# 1203_054.net
KiCad netlist of a schematic drawn in EAGLE
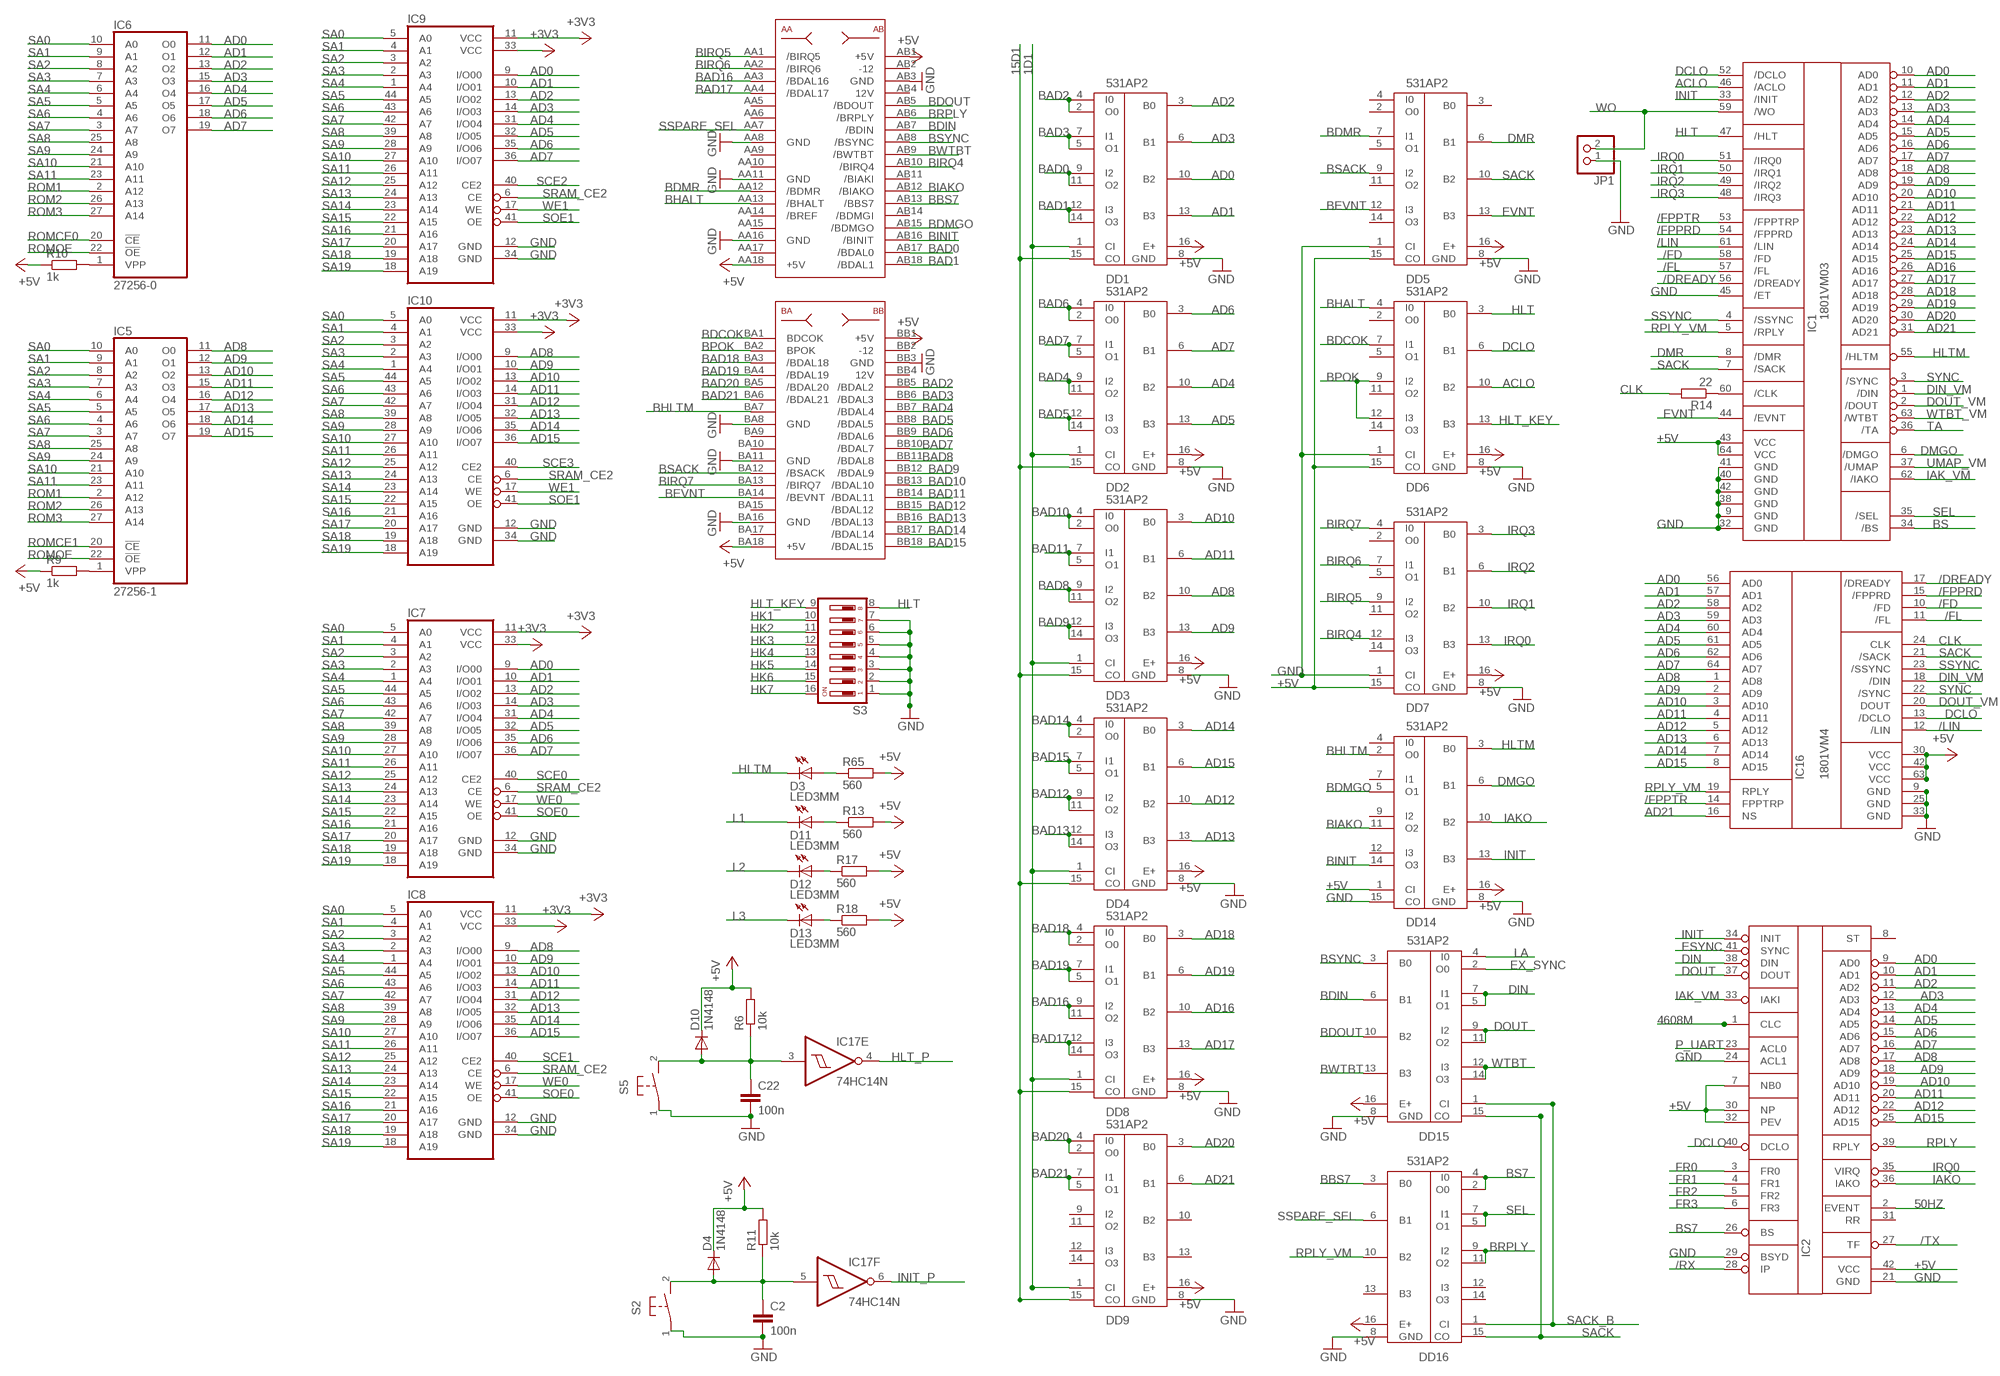
[diagram p0: schematic, sheet 1, part 1 of 2]
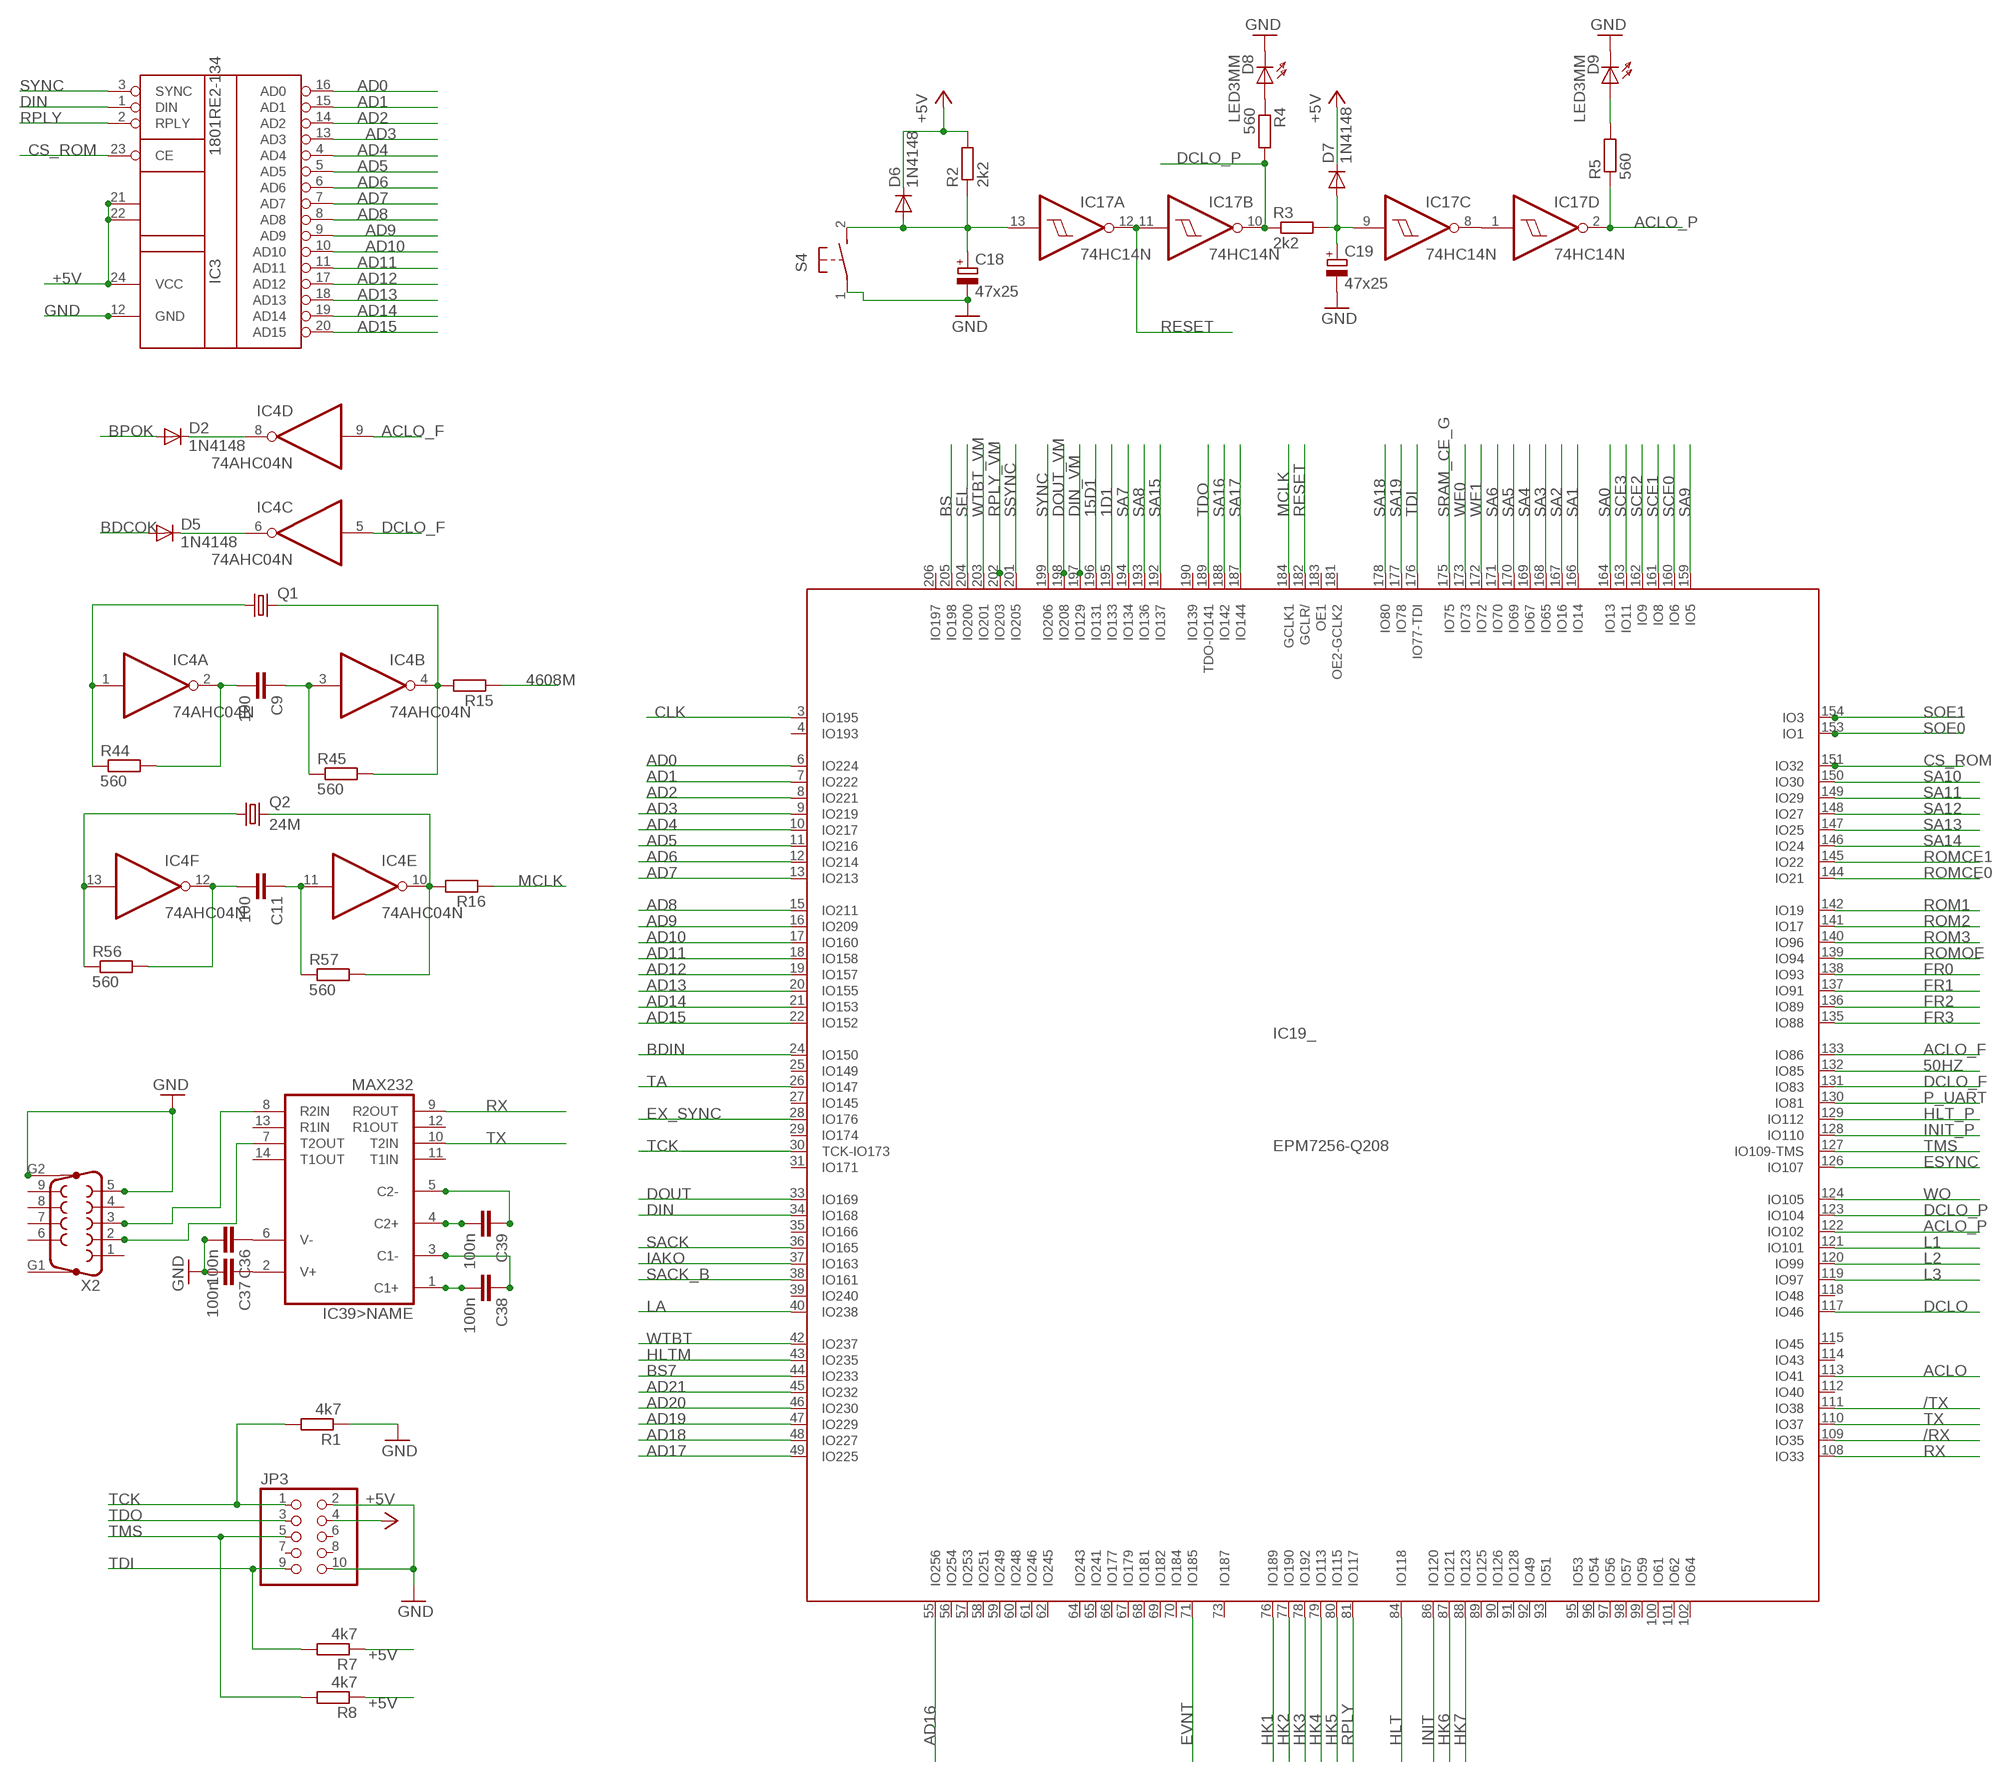
[diagram p1: schematic, sheet 1, part 2 of 2]
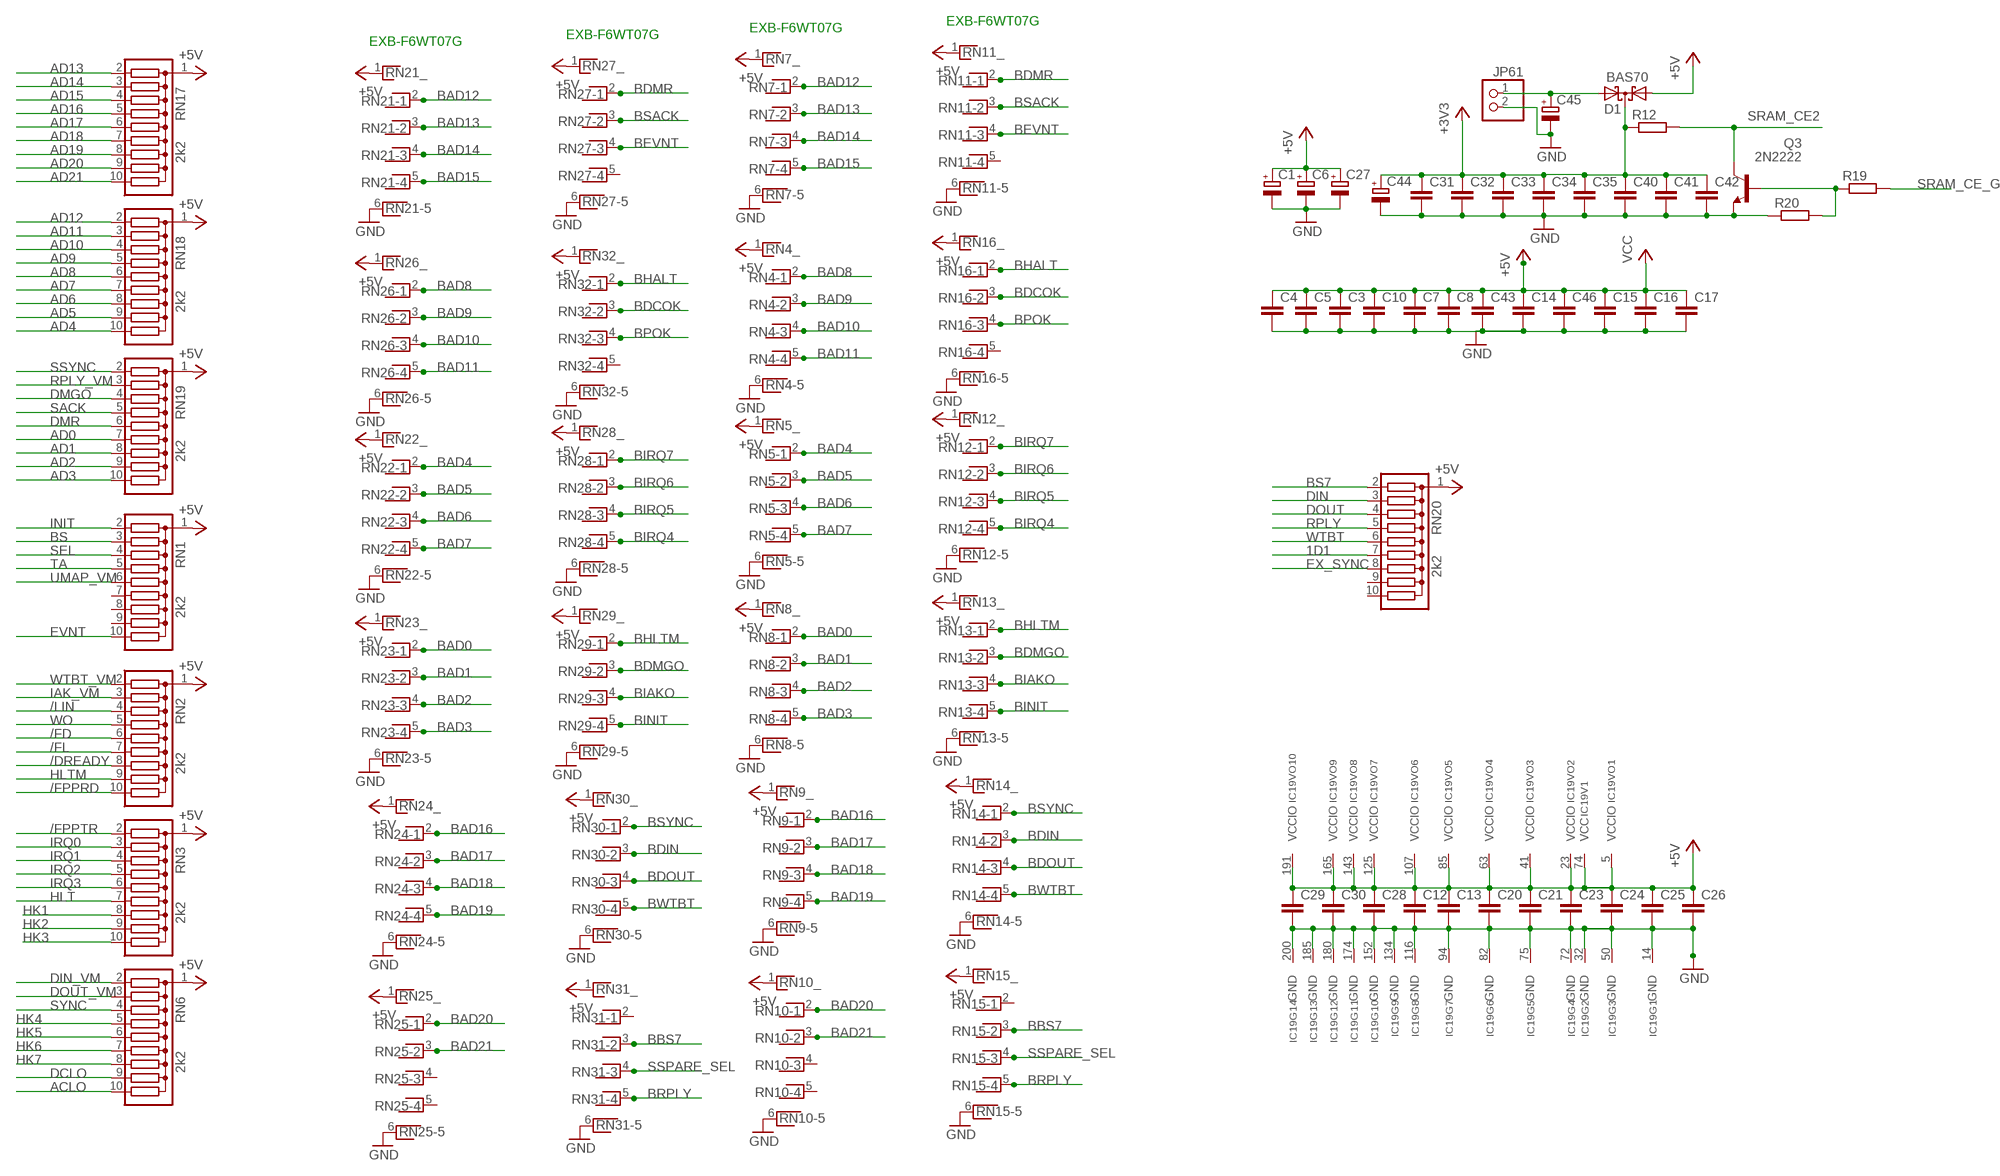
[diagram p2: schematic, sheet 2]

(export (version "E")
  (design (tool "Eeschema 10.0.6"))
  (components
    (comp (ref "C1")
      (value "CPOL-EUCT6032")
      (footprint "eagle-import:CT6032")
      (libsource (lib "eagle-import") (part "CPOL-EUCT6032"))
    )
    (comp (ref "C3")
      (value "C-EU050-024X044")
      (footprint "eagle-import:C050-024X044")
      (libsource (lib "eagle-import") (part "C-EU050-024X044"))
    )
    (comp (ref "C4")
      (value "C-EU050-024X044")
      (footprint "eagle-import:C050-024X044")
      (libsource (lib "eagle-import") (part "C-EU050-024X044"))
    )
    (comp (ref "C5")
      (value "C-EU050-024X044")
      (footprint "eagle-import:C050-024X044")
      (libsource (lib "eagle-import") (part "C-EU050-024X044"))
    )
    (comp (ref "C6")
      (value "CPOL-EUCT6032")
      (footprint "eagle-import:CT6032")
      (libsource (lib "eagle-import") (part "CPOL-EUCT6032"))
    )
    (comp (ref "C7")
      (value "C-EU050-024X044")
      (footprint "eagle-import:C050-024X044")
      (libsource (lib "eagle-import") (part "C-EU050-024X044"))
    )
    (comp (ref "C8")
      (value "C-EU050-024X044")
      (footprint "eagle-import:C050-024X044")
      (libsource (lib "eagle-import") (part "C-EU050-024X044"))
    )
    (comp (ref "C10")
      (value "C-EU050-024X044")
      (footprint "eagle-import:C050-024X044")
      (libsource (lib "eagle-import") (part "C-EU050-024X044"))
    )
    (comp (ref "C12")
      (value "C-EUC0805")
      (footprint "eagle-import:C0805")
      (libsource (lib "eagle-import") (part "C-EUC0805"))
    )
    (comp (ref "C13")
      (value "C-EUC0805")
      (footprint "eagle-import:C0805")
      (libsource (lib "eagle-import") (part "C-EUC0805"))
    )
    (comp (ref "C14")
      (value "C-EU050-024X044")
      (footprint "eagle-import:C050-024X044")
      (libsource (lib "eagle-import") (part "C-EU050-024X044"))
    )
    (comp (ref "C15")
      (value "C-EU050-024X044")
      (footprint "eagle-import:C050-024X044")
      (libsource (lib "eagle-import") (part "C-EU050-024X044"))
    )
    (comp (ref "C16")
      (value "C-EU050-024X044")
      (footprint "eagle-import:C050-024X044")
      (libsource (lib "eagle-import") (part "C-EU050-024X044"))
    )
    (comp (ref "C17")
      (value "C-EU050-024X044")
      (footprint "eagle-import:C050-024X044")
      (libsource (lib "eagle-import") (part "C-EU050-024X044"))
    )
    (comp (ref "C20")
      (value "C-EUC0805")
      (footprint "eagle-import:C0805")
      (libsource (lib "eagle-import") (part "C-EUC0805"))
    )
    (comp (ref "C21")
      (value "C-EUC0805")
      (footprint "eagle-import:C0805")
      (libsource (lib "eagle-import") (part "C-EUC0805"))
    )
    (comp (ref "C23")
      (value "C-EU050-024X044")
      (footprint "eagle-import:C050-024X044")
      (libsource (lib "eagle-import") (part "C-EU050-024X044"))
    )
    (comp (ref "C24")
      (value "C-EU050-024X044")
      (footprint "eagle-import:C050-024X044")
      (libsource (lib "eagle-import") (part "C-EU050-024X044"))
    )
    (comp (ref "C25")
      (value "C-EU050-024X044")
      (footprint "eagle-import:C050-024X044")
      (libsource (lib "eagle-import") (part "C-EU050-024X044"))
    )
    (comp (ref "C26")
      (value "C-EU050-024X044")
      (footprint "eagle-import:C050-024X044")
      (libsource (lib "eagle-import") (part "C-EU050-024X044"))
    )
    (comp (ref "C27")
      (value "CPOL-EUCT6032")
      (footprint "eagle-import:CT6032")
      (libsource (lib "eagle-import") (part "CPOL-EUCT6032"))
    )
    (comp (ref "C28")
      (value "C-EU050-024X044")
      (footprint "eagle-import:C050-024X044")
      (libsource (lib "eagle-import") (part "C-EU050-024X044"))
    )
    (comp (ref "C29")
      (value "C-EU050-024X044")
      (footprint "eagle-import:C050-024X044")
      (libsource (lib "eagle-import") (part "C-EU050-024X044"))
    )
    (comp (ref "C30")
      (value "C-EU050-024X044")
      (footprint "eagle-import:C050-024X044")
      (libsource (lib "eagle-import") (part "C-EU050-024X044"))
    )
    (comp (ref "C31")
      (value "C-EUC0603")
      (footprint "eagle-import:C0603")
      (libsource (lib "eagle-import") (part "C-EUC0603"))
    )
    (comp (ref "C32")
      (value "C-EUC0603")
      (footprint "eagle-import:C0603")
      (libsource (lib "eagle-import") (part "C-EUC0603"))
    )
    (comp (ref "C33")
      (value "C-EUC0603")
      (footprint "eagle-import:C0603")
      (libsource (lib "eagle-import") (part "C-EUC0603"))
    )
    (comp (ref "C34")
      (value "C-EUC0603")
      (footprint "eagle-import:C0603")
      (libsource (lib "eagle-import") (part "C-EUC0603"))
    )
    (comp (ref "C35")
      (value "C-EUC0603")
      (footprint "eagle-import:C0603")
      (libsource (lib "eagle-import") (part "C-EUC0603"))
    )
    (comp (ref "C40")
      (value "C-EUC0603")
      (footprint "eagle-import:C0603")
      (libsource (lib "eagle-import") (part "C-EUC0603"))
    )
    (comp (ref "C41")
      (value "C-EUC0603")
      (footprint "eagle-import:C0603")
      (libsource (lib "eagle-import") (part "C-EUC0603"))
    )
    (comp (ref "C42")
      (value "C-EUC0603")
      (footprint "eagle-import:C0603")
      (libsource (lib "eagle-import") (part "C-EUC0603"))
    )
    (comp (ref "C43")
      (value "C-EU050-024X044")
      (footprint "eagle-import:C050-024X044")
      (libsource (lib "eagle-import") (part "C-EU050-024X044"))
    )
    (comp (ref "C44")
      (value "CPOL-EUCT7343")
      (footprint "eagle-import:CT7343")
      (libsource (lib "eagle-import") (part "CPOL-EUCT7343"))
    )
    (comp (ref "C45")
      (value "CPOL-EUCT7343")
      (footprint "eagle-import:CT7343")
      (libsource (lib "eagle-import") (part "CPOL-EUCT7343"))
    )
    (comp (ref "C46")
      (value "C-EU050-024X044")
      (footprint "eagle-import:C050-024X044")
      (libsource (lib "eagle-import") (part "C-EU050-024X044"))
    )
    (comp (ref "D1")
      (value "BAS70")
      (footprint "eagle-import:SOT23")
      (libsource (lib "eagle-import") (part "BAS70-05"))
    )
    (comp (ref "IC19")
      (value "EPM7256-Q208")
      (footprint "eagle-import:RQFP208")
      (fields (field (name "MPN") "EPM7256AEQC208-10N"))
      (libsource (lib "eagle-import") (part "EPM7256-Q208"))
    )
    (comp (ref "JP61")
      (value "PINHD-1X2")
      (footprint "eagle-import:1X02")
      (libsource (lib "eagle-import") (part "PINHD-1X2"))
    )
    (comp (ref "Q3")
      (value "2N2222")
      (footprint "eagle-import:TO18")
      (libsource (lib "eagle-import") (part "2N2222"))
    )
    (comp (ref "R12")
      (value "R-EU_M0805")
      (footprint "eagle-import:M0805")
      (libsource (lib "eagle-import") (part "R-EU_M0805"))
    )
    (comp (ref "R19")
      (value "R-EU_M0805")
      (footprint "eagle-import:M0805")
      (libsource (lib "eagle-import") (part "R-EU_M0805"))
    )
    (comp (ref "R20")
      (value "R-EU_M0805")
      (footprint "eagle-import:M0805")
      (libsource (lib "eagle-import") (part "R-EU_M0805"))
    )
    (comp (ref "RN1")
      (value "2k2")
      (footprint "eagle-import:SIL10")
      (libsource (lib "eagle-import") (part "G09R"))
    )
    (comp (ref "RN2")
      (value "2k2")
      (footprint "eagle-import:SIL10")
      (libsource (lib "eagle-import") (part "G09R"))
    )
    (comp (ref "RN3")
      (value "2k2")
      (footprint "eagle-import:SIL10")
      (libsource (lib "eagle-import") (part "G09R"))
    )
    (comp (ref "RN4")
      (value "RNX5")
      (footprint "eagle-import:RN-6")
      (libsource (lib "eagle-import") (part "RNX5"))
    )
    (comp (ref "RN5")
      (value "RNX5")
      (footprint "eagle-import:RN-6")
      (libsource (lib "eagle-import") (part "RNX5"))
    )
    (comp (ref "RN6")
      (value "2k2")
      (footprint "eagle-import:SIL10")
      (libsource (lib "eagle-import") (part "G09R"))
    )
    (comp (ref "RN7")
      (value "RNX5")
      (footprint "eagle-import:RN-6")
      (libsource (lib "eagle-import") (part "RNX5"))
    )
    (comp (ref "RN8")
      (value "RNX5")
      (footprint "eagle-import:RN-6")
      (libsource (lib "eagle-import") (part "RNX5"))
    )
    (comp (ref "RN9")
      (value "RNX5")
      (footprint "eagle-import:RN-6")
      (libsource (lib "eagle-import") (part "RNX5"))
    )
    (comp (ref "RN10")
      (value "RNX5")
      (footprint "eagle-import:RN-6")
      (libsource (lib "eagle-import") (part "RNX5"))
    )
    (comp (ref "RN11")
      (value "RNX5")
      (footprint "eagle-import:RN-6")
      (libsource (lib "eagle-import") (part "RNX5"))
    )
    (comp (ref "RN12")
      (value "RNX5")
      (footprint "eagle-import:RN-6")
      (libsource (lib "eagle-import") (part "RNX5"))
    )
    (comp (ref "RN13")
      (value "RNX5")
      (footprint "eagle-import:RN-6")
      (libsource (lib "eagle-import") (part "RNX5"))
    )
    (comp (ref "RN14")
      (value "RNX5")
      (footprint "eagle-import:RN-6")
      (libsource (lib "eagle-import") (part "RNX5"))
    )
    (comp (ref "RN15")
      (value "RNX5")
      (footprint "eagle-import:RN-6")
      (libsource (lib "eagle-import") (part "RNX5"))
    )
    (comp (ref "RN16")
      (value "RNX5")
      (footprint "eagle-import:RN-6")
      (libsource (lib "eagle-import") (part "RNX5"))
    )
    (comp (ref "RN17")
      (value "2k2")
      (footprint "eagle-import:SIL10")
      (libsource (lib "eagle-import") (part "G09R"))
    )
    (comp (ref "RN18")
      (value "2k2")
      (footprint "eagle-import:SIL10")
      (libsource (lib "eagle-import") (part "G09R"))
    )
    (comp (ref "RN19")
      (value "2k2")
      (footprint "eagle-import:SIL10")
      (libsource (lib "eagle-import") (part "G09R"))
    )
    (comp (ref "RN20")
      (value "2k2")
      (footprint "eagle-import:SIL10")
      (libsource (lib "eagle-import") (part "G09R"))
    )
    (comp (ref "RN21")
      (value "RNX5")
      (footprint "eagle-import:RN-6")
      (libsource (lib "eagle-import") (part "RNX5"))
    )
    (comp (ref "RN22")
      (value "RNX5")
      (footprint "eagle-import:RN-6")
      (libsource (lib "eagle-import") (part "RNX5"))
    )
    (comp (ref "RN23")
      (value "RNX5")
      (footprint "eagle-import:RN-6")
      (libsource (lib "eagle-import") (part "RNX5"))
    )
    (comp (ref "RN24")
      (value "RNX5")
      (footprint "eagle-import:RN-6")
      (libsource (lib "eagle-import") (part "RNX5"))
    )
    (comp (ref "RN25")
      (value "RNX5")
      (footprint "eagle-import:RN-6")
      (libsource (lib "eagle-import") (part "RNX5"))
    )
    (comp (ref "RN26")
      (value "RNX5")
      (footprint "eagle-import:RN-6")
      (libsource (lib "eagle-import") (part "RNX5"))
    )
    (comp (ref "RN27")
      (value "RNX5")
      (footprint "eagle-import:RN-6")
      (libsource (lib "eagle-import") (part "RNX5"))
    )
    (comp (ref "RN28")
      (value "RNX5")
      (footprint "eagle-import:RN-6")
      (libsource (lib "eagle-import") (part "RNX5"))
    )
    (comp (ref "RN29")
      (value "RNX5")
      (footprint "eagle-import:RN-6")
      (libsource (lib "eagle-import") (part "RNX5"))
    )
    (comp (ref "RN30")
      (value "RNX5")
      (footprint "eagle-import:RN-6")
      (libsource (lib "eagle-import") (part "RNX5"))
    )
    (comp (ref "RN31")
      (value "RNX5")
      (footprint "eagle-import:RN-6")
      (libsource (lib "eagle-import") (part "RNX5"))
    )
    (comp (ref "RN32")
      (value "RNX5")
      (footprint "eagle-import:RN-6")
      (libsource (lib "eagle-import") (part "RNX5"))
    )
    (comp (ref "C2")
      (value "100n")
      (footprint "eagle-import:C050-024X044")
      (libsource (lib "eagle-import") (part "C-EU050-024X044"))
    )
    (comp (ref "C9")
      (value "100")
      (footprint "eagle-import:C025-024X044")
      (libsource (lib "eagle-import") (part "C-EU025-024X044"))
    )
    (comp (ref "C11")
      (value "100")
      (footprint "eagle-import:C025-024X044")
      (libsource (lib "eagle-import") (part "C-EU025-024X044"))
    )
    (comp (ref "C18")
      (value "47x25")
      (footprint "eagle-import:E2,5-5")
      (libsource (lib "eagle-import") (part "CPOL-EUE2.5-5"))
    )
    (comp (ref "C19")
      (value "47x25")
      (footprint "eagle-import:E2,5-5")
      (libsource (lib "eagle-import") (part "CPOL-EUE2.5-5"))
    )
    (comp (ref "C22")
      (value "100n")
      (footprint "eagle-import:C050-024X044")
      (libsource (lib "eagle-import") (part "C-EU050-024X044"))
    )
    (comp (ref "C36")
      (value "100n")
      (footprint "eagle-import:C025-024X044")
      (libsource (lib "eagle-import") (part "C-EU025-024X044"))
    )
    (comp (ref "C37")
      (value "100n")
      (footprint "eagle-import:C025-024X044")
      (libsource (lib "eagle-import") (part "C-EU025-024X044"))
    )
    (comp (ref "C38")
      (value "100n")
      (footprint "eagle-import:C025-024X044")
      (libsource (lib "eagle-import") (part "C-EU025-024X044"))
    )
    (comp (ref "C39")
      (value "100n")
      (footprint "eagle-import:C025-024X044")
      (libsource (lib "eagle-import") (part "C-EU025-024X044"))
    )
    (comp (ref "D2")
      (value "1N4148")
      (footprint "eagle-import:DO35-10")
      (libsource (lib "eagle-import") (part "1N4148"))
    )
    (comp (ref "D3")
      (value "LED3MM")
      (footprint "eagle-import:LED3MM")
      (libsource (lib "eagle-import") (part "LED3MM"))
    )
    (comp (ref "D4")
      (value "1N4148")
      (footprint "eagle-import:DO35-10")
      (libsource (lib "eagle-import") (part "1N4148"))
    )
    (comp (ref "D5")
      (value "1N4148")
      (footprint "eagle-import:DO35-10")
      (libsource (lib "eagle-import") (part "1N4148"))
    )
    (comp (ref "D6")
      (value "1N4148")
      (footprint "eagle-import:DO35-10")
      (libsource (lib "eagle-import") (part "1N4148"))
    )
    (comp (ref "D7")
      (value "1N4148")
      (footprint "eagle-import:DO35-10")
      (libsource (lib "eagle-import") (part "1N4148"))
    )
    (comp (ref "D8")
      (value "LED3MM")
      (footprint "eagle-import:LED3MM")
      (libsource (lib "eagle-import") (part "LED3MM"))
    )
    (comp (ref "D9")
      (value "LED3MM")
      (footprint "eagle-import:LED3MM")
      (libsource (lib "eagle-import") (part "LED3MM"))
    )
    (comp (ref "D10")
      (value "1N4148")
      (footprint "eagle-import:DO35-10")
      (libsource (lib "eagle-import") (part "1N4148"))
    )
    (comp (ref "D11")
      (value "LED3MM")
      (footprint "eagle-import:LED3MM")
      (libsource (lib "eagle-import") (part "LED3MM"))
    )
    (comp (ref "D12")
      (value "LED3MM")
      (footprint "eagle-import:LED3MM")
      (libsource (lib "eagle-import") (part "LED3MM"))
    )
    (comp (ref "D13")
      (value "LED3MM")
      (footprint "eagle-import:LED3MM")
      (libsource (lib "eagle-import") (part "LED3MM"))
    )
    (comp (ref "DD1")
      (value "531AP2")
      (footprint "eagle-import:DIL16")
      (libsource (lib "eagle-import") (part "531AP2"))
    )
    (comp (ref "DD2")
      (value "531AP2")
      (footprint "eagle-import:DIL16")
      (libsource (lib "eagle-import") (part "531AP2"))
    )
    (comp (ref "DD3")
      (value "531AP2")
      (footprint "eagle-import:DIL16")
      (libsource (lib "eagle-import") (part "531AP2"))
    )
    (comp (ref "DD4")
      (value "531AP2")
      (footprint "eagle-import:DIL16")
      (libsource (lib "eagle-import") (part "531AP2"))
    )
    (comp (ref "DD5")
      (value "531AP2")
      (footprint "eagle-import:DIL16")
      (libsource (lib "eagle-import") (part "531AP2"))
    )
    (comp (ref "DD6")
      (value "531AP2")
      (footprint "eagle-import:DIL16")
      (libsource (lib "eagle-import") (part "531AP2"))
    )
    (comp (ref "DD7")
      (value "531AP2")
      (footprint "eagle-import:DIL16")
      (libsource (lib "eagle-import") (part "531AP2"))
    )
    (comp (ref "DD8")
      (value "531AP2")
      (footprint "eagle-import:DIL16")
      (libsource (lib "eagle-import") (part "531AP2"))
    )
    (comp (ref "DD9")
      (value "531AP2")
      (footprint "eagle-import:DIL16")
      (libsource (lib "eagle-import") (part "531AP2"))
    )
    (comp (ref "DD14")
      (value "531AP2")
      (footprint "eagle-import:DIL16")
      (libsource (lib "eagle-import") (part "531AP2"))
    )
    (comp (ref "DD15")
      (value "531AP2")
      (footprint "eagle-import:DIL16")
      (libsource (lib "eagle-import") (part "531AP2"))
    )
    (comp (ref "DD16")
      (value "531AP2")
      (footprint "eagle-import:DIL16")
      (libsource (lib "eagle-import") (part "531AP2"))
    )
    (comp (ref "IC1")
      (value "1801VM03")
      (footprint "eagle-import:DIL64")
      (libsource (lib "eagle-import") (part "1801M03"))
    )
    (comp (ref "IC2")
      (value "1801VP1-065")
      (footprint "eagle-import:1801")
      (libsource (lib "eagle-import") (part "1801VP1-065"))
    )
    (comp (ref "IC3")
      (value "1801RE2-134")
      (footprint "eagle-import:DIL24")
      (libsource (lib "eagle-import") (part "1801RE2"))
    )
    (comp (ref "IC4")
      (value "74AHC04N")
      (footprint "eagle-import:DIL14")
      (libsource (lib "eagle-import") (part "7405NALS"))
    )
    (comp (ref "IC5")
      (value "27256-1")
      (footprint "eagle-import:DIL28")
      (libsource (lib "eagle-import") (part "27256"))
    )
    (comp (ref "IC6")
      (value "27256-0")
      (footprint "eagle-import:DIL28")
      (libsource (lib "eagle-import") (part "27256"))
    )
    (comp (ref "IC7")
      (value "AS6C800855Z")
      (footprint "eagle-import:TSOP44")
      (libsource (lib "eagle-import") (part "AS6C800855Z"))
    )
    (comp (ref "IC8")
      (value "AS6C800855Z")
      (footprint "eagle-import:TSOP44")
      (libsource (lib "eagle-import") (part "AS6C800855Z"))
    )
    (comp (ref "IC9")
      (value "AS6C800855Z")
      (footprint "eagle-import:TSOP44")
      (libsource (lib "eagle-import") (part "AS6C800855Z"))
    )
    (comp (ref "IC10")
      (value "AS6C800855Z")
      (footprint "eagle-import:TSOP44")
      (libsource (lib "eagle-import") (part "AS6C800855Z"))
    )
    (comp (ref "IC16")
      (value "1801VM4")
      (footprint "eagle-import:1801VM4")
      (libsource (lib "eagle-import") (part "1801VM4"))
    )
    (comp (ref "IC17")
      (value "74HC14N")
      (footprint "eagle-import:DIL14")
      (libsource (lib "eagle-import") (part "7414NAC"))
    )
    (comp (ref "IC39")
      (value "MAX232")
      (footprint "eagle-import:DIL16")
      (libsource (lib "eagle-import") (part "MAX232"))
    )
    (comp (ref "JP1")
      (value "PINHD-1X2")
      (footprint "eagle-import:1X02")
      (libsource (lib "eagle-import") (part "PINHD-1X2"))
    )
    (comp (ref "JP3")
      (value "PINHD-2X5")
      (footprint "eagle-import:2X05")
      (libsource (lib "eagle-import") (part "PINHD-2X5"))
    )
    (comp (ref "Q1")
      (value "HC49U70")
      (footprint "eagle-import:HC49U70")
      (libsource (lib "eagle-import") (part "HC49U70"))
    )
    (comp (ref "Q2")
      (value "24M")
      (footprint "eagle-import:HC49U70")
      (libsource (lib "eagle-import") (part "HC49U70"))
    )
    (comp (ref "R1")
      (value "4k7")
      (footprint "eagle-import:M0805")
      (libsource (lib "eagle-import") (part "R-EU_M0805"))
    )
    (comp (ref "R2")
      (value "2k2")
      (footprint "eagle-import:0207_10")
      (libsource (lib "eagle-import") (part "R-EU_0207/10"))
    )
    (comp (ref "R3")
      (value "2k2")
      (footprint "eagle-import:0207_10")
      (libsource (lib "eagle-import") (part "R-EU_0207/10"))
    )
    (comp (ref "R4")
      (value "560")
      (footprint "eagle-import:M0805")
      (libsource (lib "eagle-import") (part "R-EU_M0805"))
    )
    (comp (ref "R5")
      (value "560")
      (footprint "eagle-import:M0805")
      (libsource (lib "eagle-import") (part "R-EU_M0805"))
    )
    (comp (ref "R6")
      (value "10k")
      (footprint "eagle-import:0207_10")
      (libsource (lib "eagle-import") (part "R-EU_0207/10"))
    )
    (comp (ref "R7")
      (value "4k7")
      (footprint "eagle-import:M0805")
      (libsource (lib "eagle-import") (part "R-EU_M0805"))
    )
    (comp (ref "R8")
      (value "4k7")
      (footprint "eagle-import:M0805")
      (libsource (lib "eagle-import") (part "R-EU_M0805"))
    )
    (comp (ref "R9")
      (value "1k")
      (footprint "eagle-import:M0805")
      (libsource (lib "eagle-import") (part "R-EU_M0805"))
    )
    (comp (ref "R10")
      (value "1k")
      (footprint "eagle-import:M0805")
      (libsource (lib "eagle-import") (part "R-EU_M0805"))
    )
    (comp (ref "R11")
      (value "10k")
      (footprint "eagle-import:0207_10")
      (libsource (lib "eagle-import") (part "R-EU_0207/10"))
    )
    (comp (ref "R13")
      (value "560")
      (footprint "eagle-import:M0805")
      (libsource (lib "eagle-import") (part "R-EU_M0805"))
    )
    (comp (ref "R14")
      (value "22")
      (footprint "eagle-import:0204V")
      (libsource (lib "eagle-import") (part "R-EU_0204/2V"))
    )
    (comp (ref "R15")
      (value "R-EU_0204/2V")
      (footprint "eagle-import:0204V")
      (libsource (lib "eagle-import") (part "R-EU_0204/2V"))
    )
    (comp (ref "R16")
      (value "R-EU_0204/2V")
      (footprint "eagle-import:0204V")
      (libsource (lib "eagle-import") (part "R-EU_0204/2V"))
    )
    (comp (ref "R17")
      (value "560")
      (footprint "eagle-import:M0805")
      (libsource (lib "eagle-import") (part "R-EU_M0805"))
    )
    (comp (ref "R18")
      (value "560")
      (footprint "eagle-import:M0805")
      (libsource (lib "eagle-import") (part "R-EU_M0805"))
    )
    (comp (ref "R44")
      (value "560")
      (footprint "eagle-import:0204V")
      (libsource (lib "eagle-import") (part "R-EU_0204/2V"))
    )
    (comp (ref "R45")
      (value "560")
      (footprint "eagle-import:0204V")
      (libsource (lib "eagle-import") (part "R-EU_0204/2V"))
    )
    (comp (ref "R56")
      (value "560")
      (footprint "eagle-import:0204V")
      (libsource (lib "eagle-import") (part "R-EU_0204/2V"))
    )
    (comp (ref "R57")
      (value "560")
      (footprint "eagle-import:0204V")
      (libsource (lib "eagle-import") (part "R-EU_0204/2V"))
    )
    (comp (ref "R65")
      (value "560")
      (footprint "eagle-import:M0805")
      (libsource (lib "eagle-import") (part "R-EU_M0805"))
    )
    (comp (ref "S2")
      (value "31-XX")
      (footprint "eagle-import:B3F-31XX")
      (libsource (lib "eagle-import") (part "31-XX"))
    )
    (comp (ref "S3")
      (value "DP08")
      (footprint "eagle-import:DP-08")
      (libsource (lib "eagle-import") (part "DP08"))
    )
    (comp (ref "S4")
      (value "31-XX")
      (footprint "eagle-import:B3F-31XX")
      (libsource (lib "eagle-import") (part "31-XX"))
    )
    (comp (ref "S5")
      (value "31-XX")
      (footprint "eagle-import:B3F-31XX")
      (libsource (lib "eagle-import") (part "31-XX"))
    )
    (comp (ref "X2")
      (value "F09HP")
      (footprint "eagle-import:F09HP")
      (libsource (lib "eagle-import") (part "F09HP"))
    )
    (comp (ref "XP1")
      (value "CON1")
      (footprint "eagle-import:CON1")
      (libsource (lib "eagle-import") (part "CON1"))
    )
  )
  (nets
    (net (code "1") (name "+3V3") (class "Default")
      (node (ref "C31") (pin "1") (pinfunction "1_1") (pintype "passive"))
      (node (ref "C32") (pin "1") (pinfunction "1_1") (pintype "passive"))
      (node (ref "C33") (pin "1") (pinfunction "1_1") (pintype "passive"))
      (node (ref "C34") (pin "1") (pinfunction "1_1") (pintype "passive"))
      (node (ref "C35") (pin "1") (pinfunction "1_1") (pintype "passive"))
      (node (ref "C40") (pin "1") (pinfunction "1_1") (pintype "passive"))
      (node (ref "C41") (pin "1") (pinfunction "1_1") (pintype "passive"))
      (node (ref "C42") (pin "1") (pinfunction "1_1") (pintype "passive"))
      (node (ref "C44") (pin "+") (pinfunction "+_+") (pintype "passive"))
      (node (ref "D1") (pin "3") (pinfunction "C_3") (pintype "passive"))
      (node (ref "IC10") (pin "11") (pinfunction "VCC_11") (pintype "bidirectional"))
      (node (ref "IC10") (pin "33") (pinfunction "VCC_33") (pintype "bidirectional"))
      (node (ref "IC7") (pin "11") (pinfunction "VCC_11") (pintype "bidirectional"))
      (node (ref "IC7") (pin "33") (pinfunction "VCC_33") (pintype "bidirectional"))
      (node (ref "IC8") (pin "11") (pinfunction "VCC_11") (pintype "bidirectional"))
      (node (ref "IC8") (pin "33") (pinfunction "VCC_33") (pintype "bidirectional"))
      (node (ref "IC9") (pin "11") (pinfunction "VCC_11") (pintype "bidirectional"))
      (node (ref "IC9") (pin "33") (pinfunction "VCC_33") (pintype "bidirectional"))
      (node (ref "R12") (pin "1") (pinfunction "1_1") (pintype "passive"))
    )
    (net (code "2") (name "+5V") (class "Default")
      (node (ref "C1") (pin "+") (pinfunction "+_+") (pintype "passive"))
      (node (ref "C10") (pin "1") (pinfunction "1_1") (pintype "passive"))
      (node (ref "C12") (pin "1") (pinfunction "1_1") (pintype "passive"))
      (node (ref "C13") (pin "1") (pinfunction "1_1") (pintype "passive"))
      (node (ref "C14") (pin "1") (pinfunction "1_1") (pintype "passive"))
      (node (ref "C15") (pin "1") (pinfunction "1_1") (pintype "passive"))
      (node (ref "C16") (pin "1") (pinfunction "1_1") (pintype "passive"))
      (node (ref "C17") (pin "1") (pinfunction "1_1") (pintype "passive"))
      (node (ref "C20") (pin "1") (pinfunction "1_1") (pintype "passive"))
      (node (ref "C21") (pin "1") (pinfunction "1_1") (pintype "passive"))
      (node (ref "C23") (pin "1") (pinfunction "1_1") (pintype "passive"))
      (node (ref "C24") (pin "1") (pinfunction "1_1") (pintype "passive"))
      (node (ref "C25") (pin "1") (pinfunction "1_1") (pintype "passive"))
      (node (ref "C26") (pin "1") (pinfunction "1_1") (pintype "passive"))
      (node (ref "C27") (pin "+") (pinfunction "+_+") (pintype "passive"))
      (node (ref "C28") (pin "1") (pinfunction "1_1") (pintype "passive"))
      (node (ref "C29") (pin "1") (pinfunction "1_1") (pintype "passive"))
      (node (ref "C3") (pin "1") (pinfunction "1_1") (pintype "passive"))
      (node (ref "C30") (pin "1") (pinfunction "1_1") (pintype "passive"))
      (node (ref "C4") (pin "1") (pinfunction "1_1") (pintype "passive"))
      (node (ref "C43") (pin "1") (pinfunction "1_1") (pintype "passive"))
      (node (ref "C46") (pin "1") (pinfunction "1_1") (pintype "passive"))
      (node (ref "C5") (pin "1") (pinfunction "1_1") (pintype "passive"))
      (node (ref "C6") (pin "+") (pinfunction "+_+") (pintype "passive"))
      (node (ref "C7") (pin "1") (pinfunction "1_1") (pintype "passive"))
      (node (ref "C8") (pin "1") (pinfunction "1_1") (pintype "passive"))
      (node (ref "D1") (pin "1") (pinfunction "A1_1") (pintype "passive"))
      (node (ref "D10") (pin "K") (pinfunction "C_K") (pintype "passive"))
      (node (ref "D4") (pin "K") (pinfunction "C_K") (pintype "passive"))
      (node (ref "D6") (pin "K") (pinfunction "C_K") (pintype "passive"))
      (node (ref "D7") (pin "K") (pinfunction "C_K") (pintype "passive"))
      (node (ref "DD1") (pin "16") (pinfunction "E+_16") (pintype "bidirectional"))
      (node (ref "DD14") (pin "1") (pinfunction "CI_1") (pintype "bidirectional"))
      (node (ref "DD14") (pin "16") (pinfunction "E+_16") (pintype "bidirectional"))
      (node (ref "DD15") (pin "16") (pinfunction "E+_16") (pintype "bidirectional"))
      (node (ref "DD16") (pin "16") (pinfunction "E+_16") (pintype "bidirectional"))
      (node (ref "DD2") (pin "16") (pinfunction "E+_16") (pintype "bidirectional"))
      (node (ref "DD3") (pin "16") (pinfunction "E+_16") (pintype "bidirectional"))
      (node (ref "DD4") (pin "16") (pinfunction "E+_16") (pintype "bidirectional"))
      (node (ref "DD5") (pin "15") (pinfunction "CO_15") (pintype "bidirectional"))
      (node (ref "DD5") (pin "16") (pinfunction "E+_16") (pintype "bidirectional"))
      (node (ref "DD6") (pin "15") (pinfunction "CO_15") (pintype "bidirectional"))
      (node (ref "DD6") (pin "16") (pinfunction "E+_16") (pintype "bidirectional"))
      (node (ref "DD7") (pin "15") (pinfunction "CO_15") (pintype "bidirectional"))
      (node (ref "DD7") (pin "16") (pinfunction "E+_16") (pintype "bidirectional"))
      (node (ref "DD8") (pin "16") (pinfunction "E+_16") (pintype "bidirectional"))
      (node (ref "DD9") (pin "16") (pinfunction "E+_16") (pintype "bidirectional"))
      (node (ref "IC1") (pin "43") (pinfunction "VCC_43") (pintype "bidirectional"))
      (node (ref "IC1") (pin "64") (pinfunction "VCC_64") (pintype "bidirectional"))
      (node (ref "IC16") (pin "30") (pinfunction "VCC_30") (pintype "bidirectional"))
      (node (ref "IC16") (pin "42") (pinfunction "VCC_42") (pintype "bidirectional"))
      (node (ref "IC16") (pin "63") (pinfunction "VCC_63") (pintype "bidirectional"))
      (node (ref "IC19") (pin "107") (pinfunction "VCCIO_107") (pintype "power_in"))
      (node (ref "IC19") (pin "125") (pinfunction "VCCIO_125") (pintype "power_in"))
      (node (ref "IC19") (pin "143") (pinfunction "VCCIO_143") (pintype "power_in"))
      (node (ref "IC19") (pin "165") (pinfunction "VCCIO_165") (pintype "power_in"))
      (node (ref "IC19") (pin "191") (pinfunction "VCCIO_191") (pintype "power_in"))
      (node (ref "IC19") (pin "23") (pinfunction "VCCIO_23") (pintype "power_in"))
      (node (ref "IC19") (pin "41") (pinfunction "VCCIO_41") (pintype "power_in"))
      (node (ref "IC19") (pin "5") (pinfunction "VCCIO_5") (pintype "power_in"))
      (node (ref "IC19") (pin "63") (pinfunction "VCCIO_63") (pintype "power_in"))
      (node (ref "IC19") (pin "74") (pinfunction "VCC_74") (pintype "power_in"))
      (node (ref "IC19") (pin "85") (pinfunction "VCCIO_85") (pintype "power_in"))
      (node (ref "IC2") (pin "30") (pinfunction "NP_30") (pintype "bidirectional"))
      (node (ref "IC2") (pin "32") (pinfunction "PEV_32") (pintype "bidirectional"))
      (node (ref "IC2") (pin "42") (pinfunction "VCC_42") (pintype "bidirectional"))
      (node (ref "IC2") (pin "7") (pinfunction "NB0_7") (pintype "bidirectional"))
      (node (ref "IC3") (pin "21") (pinfunction "F0_21") (pintype "bidirectional"))
      (node (ref "IC3") (pin "22") (pinfunction "F1_22") (pintype "bidirectional"))
      (node (ref "IC3") (pin "24") (pinfunction "VCC_24") (pintype "bidirectional"))
      (node (ref "JP3") (pin "4") (pinfunction "4_4") (pintype "passive"))
      (node (ref "R10") (pin "1") (pinfunction "1_1") (pintype "passive"))
      (node (ref "R11") (pin "2") (pinfunction "2_2") (pintype "passive"))
      (node (ref "R13") (pin "2") (pinfunction "2_2") (pintype "passive"))
      (node (ref "R17") (pin "2") (pinfunction "2_2") (pintype "passive"))
      (node (ref "R18") (pin "2") (pinfunction "2_2") (pintype "passive"))
      (node (ref "R2") (pin "2") (pinfunction "2_2") (pintype "passive"))
      (node (ref "R6") (pin "2") (pinfunction "2_2") (pintype "passive"))
      (node (ref "R65") (pin "2") (pinfunction "2_2") (pintype "passive"))
      (node (ref "R7") (pin "1") (pinfunction "1_1") (pintype "passive"))
      (node (ref "R8") (pin "1") (pinfunction "1_1") (pintype "passive"))
      (node (ref "R9") (pin "1") (pinfunction "1_1") (pintype "passive"))
      (node (ref "RN1") (pin "1") (pinfunction "1_1") (pintype "passive"))
      (node (ref "RN10") (pin "1") (pinfunction "1_1") (pintype "passive"))
      (node (ref "RN11") (pin "1") (pinfunction "1_1") (pintype "passive"))
      (node (ref "RN12") (pin "1") (pinfunction "1_1") (pintype "passive"))
      (node (ref "RN13") (pin "1") (pinfunction "1_1") (pintype "passive"))
      (node (ref "RN14") (pin "1") (pinfunction "1_1") (pintype "passive"))
      (node (ref "RN15") (pin "1") (pinfunction "1_1") (pintype "passive"))
      (node (ref "RN16") (pin "1") (pinfunction "1_1") (pintype "passive"))
      (node (ref "RN17") (pin "1") (pinfunction "1_1") (pintype "passive"))
      (node (ref "RN18") (pin "1") (pinfunction "1_1") (pintype "passive"))
      (node (ref "RN19") (pin "1") (pinfunction "1_1") (pintype "passive"))
      (node (ref "RN2") (pin "1") (pinfunction "1_1") (pintype "passive"))
      (node (ref "RN20") (pin "1") (pinfunction "1_1") (pintype "passive"))
      (node (ref "RN21") (pin "1") (pinfunction "1_1") (pintype "passive"))
      (node (ref "RN22") (pin "1") (pinfunction "1_1") (pintype "passive"))
      (node (ref "RN23") (pin "1") (pinfunction "1_1") (pintype "passive"))
      (node (ref "RN24") (pin "1") (pinfunction "1_1") (pintype "passive"))
      (node (ref "RN25") (pin "1") (pinfunction "1_1") (pintype "passive"))
      (node (ref "RN26") (pin "1") (pinfunction "1_1") (pintype "passive"))
      (node (ref "RN27") (pin "1") (pinfunction "1_1") (pintype "passive"))
      (node (ref "RN28") (pin "1") (pinfunction "1_1") (pintype "passive"))
      (node (ref "RN29") (pin "1") (pinfunction "1_1") (pintype "passive"))
      (node (ref "RN3") (pin "1") (pinfunction "1_1") (pintype "passive"))
      (node (ref "RN30") (pin "1") (pinfunction "1_1") (pintype "passive"))
      (node (ref "RN31") (pin "1") (pinfunction "1_1") (pintype "passive"))
      (node (ref "RN32") (pin "1") (pinfunction "1_1") (pintype "passive"))
      (node (ref "RN4") (pin "1") (pinfunction "1_1") (pintype "passive"))
      (node (ref "RN5") (pin "1") (pinfunction "1_1") (pintype "passive"))
      (node (ref "RN6") (pin "1") (pinfunction "1_1") (pintype "passive"))
      (node (ref "RN7") (pin "1") (pinfunction "1_1") (pintype "passive"))
      (node (ref "RN8") (pin "1") (pinfunction "1_1") (pintype "passive"))
      (node (ref "RN9") (pin "1") (pinfunction "1_1") (pintype "passive"))
      (node (ref "XP1") (pin "AA18") (pinfunction "+5V_AA18") (pintype "bidirectional"))
      (node (ref "XP1") (pin "AB1") (pinfunction "+5V_AB1") (pintype "bidirectional"))
      (node (ref "XP1") (pin "BA18") (pinfunction "+5V_BA18") (pintype "bidirectional"))
      (node (ref "XP1") (pin "BB1") (pinfunction "+5V_BB1") (pintype "bidirectional"))
    )
    (net (code "3") (name "1D1") (class "Default")
      (node (ref "DD1") (pin "1") (pinfunction "CI_1") (pintype "bidirectional"))
      (node (ref "DD2") (pin "1") (pinfunction "CI_1") (pintype "bidirectional"))
      (node (ref "DD3") (pin "1") (pinfunction "CI_1") (pintype "bidirectional"))
      (node (ref "DD4") (pin "1") (pinfunction "CI_1") (pintype "bidirectional"))
      (node (ref "DD8") (pin "1") (pinfunction "CI_1") (pintype "bidirectional"))
      (node (ref "DD9") (pin "1") (pinfunction "CI_1") (pintype "bidirectional"))
      (node (ref "IC19") (pin "195") (pinfunction "IO133_195") (pintype "bidirectional"))
      (node (ref "RN20") (pin "7") (pinfunction "7_7") (pintype "passive"))
    )
    (net (code "4") (name "15D1") (class "Default")
      (node (ref "DD1") (pin "15") (pinfunction "CO_15") (pintype "bidirectional"))
      (node (ref "DD2") (pin "15") (pinfunction "CO_15") (pintype "bidirectional"))
      (node (ref "DD3") (pin "15") (pinfunction "CO_15") (pintype "bidirectional"))
      (node (ref "DD4") (pin "15") (pinfunction "CO_15") (pintype "bidirectional"))
      (node (ref "DD8") (pin "15") (pinfunction "CO_15") (pintype "bidirectional"))
      (node (ref "DD9") (pin "15") (pinfunction "CO_15") (pintype "bidirectional"))
      (node (ref "IC19") (pin "196") (pinfunction "IO131_196") (pintype "bidirectional"))
    )
    (net (code "5") (name "50HZ") (class "Default")
      (node (ref "IC19") (pin "132") (pinfunction "IO85_132") (pintype "bidirectional"))
      (node (ref "IC2") (pin "2") (pinfunction "EVENT_2") (pintype "bidirectional"))
    )
    (net (code "6") (name "4608M") (class "Default")
      (node (ref "IC2") (pin "1") (pinfunction "CLC_1") (pintype "bidirectional"))
      (node (ref "R15") (pin "1") (pinfunction "1_1") (pintype "passive"))
    )
    (net (code "7") (name "ACLO") (class "Default")
      (node (ref "DD6") (pin "10") (pinfunction "B2_10") (pintype "bidirectional"))
      (node (ref "IC1") (pin "46") (pinfunction "/ACLO_46") (pintype "bidirectional"))
      (node (ref "IC19") (pin "113") (pinfunction "IO41_113") (pintype "bidirectional"))
      (node (ref "RN6") (pin "10") (pinfunction "10_10") (pintype "passive"))
    )
    (net (code "8") (name "ACLO_F") (class "Default")
      (node (ref "IC19") (pin "133") (pinfunction "IO86_133") (pintype "bidirectional"))
      (node (ref "IC4") (pin "9") (pinfunction "I_9") (pintype "input"))
    )
    (net (code "9") (name "ACLO_P") (class "Default")
      (node (ref "IC17") (pin "2") (pinfunction "O_2") (pintype "output"))
      (node (ref "IC19") (pin "122") (pinfunction "IO102_122") (pintype "bidirectional"))
      (node (ref "R5") (pin "1") (pinfunction "1_1") (pintype "passive"))
    )
    (net (code "10") (name "AD0") (class "Default")
      (node (ref "DD1") (pin "10") (pinfunction "B2_10") (pintype "bidirectional"))
      (node (ref "IC1") (pin "10") (pinfunction "AD0_10") (pintype "bidirectional"))
      (node (ref "IC16") (pin "56") (pinfunction "AD0_56") (pintype "bidirectional"))
      (node (ref "IC19") (pin "6") (pinfunction "IO224_6") (pintype "bidirectional"))
      (node (ref "IC2") (pin "9") (pinfunction "AD0_9") (pintype "bidirectional"))
      (node (ref "IC3") (pin "16") (pinfunction "AD0_16") (pintype "bidirectional"))
      (node (ref "IC6") (pin "11") (pinfunction "O0_11") (pintype "tri_state"))
      (node (ref "IC7") (pin "9") (pinfunction "I/O00_9") (pintype "bidirectional"))
      (node (ref "IC9") (pin "9") (pinfunction "I/O00_9") (pintype "bidirectional"))
      (node (ref "RN19") (pin "7") (pinfunction "7_7") (pintype "passive"))
    )
    (net (code "11") (name "AD1") (class "Default")
      (node (ref "DD1") (pin "13") (pinfunction "B3_13") (pintype "bidirectional"))
      (node (ref "IC1") (pin "11") (pinfunction "AD1_11") (pintype "bidirectional"))
      (node (ref "IC16") (pin "57") (pinfunction "AD1_57") (pintype "bidirectional"))
      (node (ref "IC19") (pin "7") (pinfunction "IO222_7") (pintype "bidirectional"))
      (node (ref "IC2") (pin "10") (pinfunction "AD1_10") (pintype "bidirectional"))
      (node (ref "IC3") (pin "15") (pinfunction "AD1_15") (pintype "bidirectional"))
      (node (ref "IC6") (pin "12") (pinfunction "O1_12") (pintype "tri_state"))
      (node (ref "IC7") (pin "10") (pinfunction "I/O01_10") (pintype "bidirectional"))
      (node (ref "IC9") (pin "10") (pinfunction "I/O01_10") (pintype "bidirectional"))
      (node (ref "RN19") (pin "8") (pinfunction "8_8") (pintype "passive"))
    )
    (net (code "12") (name "AD2") (class "Default")
      (node (ref "DD1") (pin "3") (pinfunction "B0_3") (pintype "bidirectional"))
      (node (ref "IC1") (pin "12") (pinfunction "AD2_12") (pintype "bidirectional"))
      (node (ref "IC16") (pin "58") (pinfunction "AD2_58") (pintype "bidirectional"))
      (node (ref "IC19") (pin "8") (pinfunction "IO221_8") (pintype "bidirectional"))
      (node (ref "IC2") (pin "11") (pinfunction "AD2_11") (pintype "bidirectional"))
      (node (ref "IC3") (pin "14") (pinfunction "AD2_14") (pintype "bidirectional"))
      (node (ref "IC6") (pin "13") (pinfunction "O2_13") (pintype "tri_state"))
      (node (ref "IC7") (pin "13") (pinfunction "I/O02_13") (pintype "bidirectional"))
      (node (ref "IC9") (pin "13") (pinfunction "I/O02_13") (pintype "bidirectional"))
      (node (ref "RN19") (pin "9") (pinfunction "9_9") (pintype "passive"))
    )
    (net (code "13") (name "AD3") (class "Default")
      (node (ref "DD1") (pin "6") (pinfunction "B1_6") (pintype "bidirectional"))
      (node (ref "IC1") (pin "13") (pinfunction "AD3_13") (pintype "bidirectional"))
      (node (ref "IC16") (pin "59") (pinfunction "AD3_59") (pintype "bidirectional"))
      (node (ref "IC19") (pin "9") (pinfunction "IO219_9") (pintype "bidirectional"))
      (node (ref "IC2") (pin "12") (pinfunction "AD3_12") (pintype "bidirectional"))
      (node (ref "IC3") (pin "13") (pinfunction "AD3_13") (pintype "bidirectional"))
      (node (ref "IC6") (pin "15") (pinfunction "O3_15") (pintype "tri_state"))
      (node (ref "IC7") (pin "14") (pinfunction "I/O03_14") (pintype "bidirectional"))
      (node (ref "IC9") (pin "14") (pinfunction "I/O03_14") (pintype "bidirectional"))
      (node (ref "RN19") (pin "10") (pinfunction "10_10") (pintype "passive"))
    )
    (net (code "14") (name "AD4") (class "Default")
      (node (ref "DD2") (pin "10") (pinfunction "B2_10") (pintype "bidirectional"))
      (node (ref "IC1") (pin "14") (pinfunction "AD4_14") (pintype "bidirectional"))
      (node (ref "IC16") (pin "60") (pinfunction "AD4_60") (pintype "bidirectional"))
      (node (ref "IC19") (pin "10") (pinfunction "IO217_10") (pintype "bidirectional"))
      (node (ref "IC2") (pin "13") (pinfunction "AD4_13") (pintype "bidirectional"))
      (node (ref "IC3") (pin "4") (pinfunction "AD4_4") (pintype "bidirectional"))
      (node (ref "IC6") (pin "16") (pinfunction "O4_16") (pintype "tri_state"))
      (node (ref "IC7") (pin "31") (pinfunction "I/O04_31") (pintype "bidirectional"))
      (node (ref "IC9") (pin "31") (pinfunction "I/O04_31") (pintype "bidirectional"))
      (node (ref "RN18") (pin "10") (pinfunction "10_10") (pintype "passive"))
    )
    (net (code "15") (name "AD5") (class "Default")
      (node (ref "DD2") (pin "13") (pinfunction "B3_13") (pintype "bidirectional"))
      (node (ref "IC1") (pin "15") (pinfunction "AD5_15") (pintype "bidirectional"))
      (node (ref "IC16") (pin "61") (pinfunction "AD5_61") (pintype "bidirectional"))
      (node (ref "IC19") (pin "11") (pinfunction "IO216_11") (pintype "bidirectional"))
      (node (ref "IC2") (pin "14") (pinfunction "AD5_14") (pintype "bidirectional"))
      (node (ref "IC3") (pin "5") (pinfunction "AD5_5") (pintype "bidirectional"))
      (node (ref "IC6") (pin "17") (pinfunction "O5_17") (pintype "tri_state"))
      (node (ref "IC7") (pin "32") (pinfunction "I/O05_32") (pintype "bidirectional"))
      (node (ref "IC9") (pin "32") (pinfunction "I/O05_32") (pintype "bidirectional"))
      (node (ref "RN18") (pin "9") (pinfunction "9_9") (pintype "passive"))
    )
    (net (code "16") (name "AD6") (class "Default")
      (node (ref "DD2") (pin "3") (pinfunction "B0_3") (pintype "bidirectional"))
      (node (ref "IC1") (pin "16") (pinfunction "AD6_16") (pintype "bidirectional"))
      (node (ref "IC16") (pin "62") (pinfunction "AD6_62") (pintype "bidirectional"))
      (node (ref "IC19") (pin "12") (pinfunction "IO214_12") (pintype "bidirectional"))
      (node (ref "IC2") (pin "15") (pinfunction "AD6_15") (pintype "bidirectional"))
      (node (ref "IC3") (pin "6") (pinfunction "AD6_6") (pintype "bidirectional"))
      (node (ref "IC6") (pin "18") (pinfunction "O6_18") (pintype "tri_state"))
      (node (ref "IC7") (pin "35") (pinfunction "I/O06_35") (pintype "bidirectional"))
      (node (ref "IC9") (pin "35") (pinfunction "I/O06_35") (pintype "bidirectional"))
      (node (ref "RN18") (pin "8") (pinfunction "8_8") (pintype "passive"))
    )
    (net (code "17") (name "AD7") (class "Default")
      (node (ref "DD2") (pin "6") (pinfunction "B1_6") (pintype "bidirectional"))
      (node (ref "IC1") (pin "17") (pinfunction "AD7_17") (pintype "bidirectional"))
      (node (ref "IC16") (pin "64") (pinfunction "AD7_64") (pintype "bidirectional"))
      (node (ref "IC19") (pin "13") (pinfunction "IO213_13") (pintype "bidirectional"))
      (node (ref "IC2") (pin "16") (pinfunction "AD7_16") (pintype "bidirectional"))
      (node (ref "IC3") (pin "7") (pinfunction "AD7_7") (pintype "bidirectional"))
      (node (ref "IC6") (pin "19") (pinfunction "O7_19") (pintype "tri_state"))
      (node (ref "IC7") (pin "36") (pinfunction "I/O07_36") (pintype "bidirectional"))
      (node (ref "IC9") (pin "36") (pinfunction "I/O07_36") (pintype "bidirectional"))
      (node (ref "RN18") (pin "7") (pinfunction "7_7") (pintype "passive"))
    )
    (net (code "18") (name "AD8") (class "Default")
      (node (ref "DD3") (pin "10") (pinfunction "B2_10") (pintype "bidirectional"))
      (node (ref "IC1") (pin "18") (pinfunction "AD8_18") (pintype "bidirectional"))
      (node (ref "IC10") (pin "9") (pinfunction "I/O00_9") (pintype "bidirectional"))
      (node (ref "IC16") (pin "1") (pinfunction "AD8_1") (pintype "bidirectional"))
      (node (ref "IC19") (pin "15") (pinfunction "IO211_15") (pintype "bidirectional"))
      (node (ref "IC2") (pin "17") (pinfunction "AD8_17") (pintype "bidirectional"))
      (node (ref "IC3") (pin "8") (pinfunction "AD8_8") (pintype "bidirectional"))
      (node (ref "IC5") (pin "11") (pinfunction "O0_11") (pintype "tri_state"))
      (node (ref "IC8") (pin "9") (pinfunction "I/O00_9") (pintype "bidirectional"))
      (node (ref "RN18") (pin "6") (pinfunction "6_6") (pintype "passive"))
    )
    (net (code "19") (name "AD9") (class "Default")
      (node (ref "DD3") (pin "13") (pinfunction "B3_13") (pintype "bidirectional"))
      (node (ref "IC1") (pin "19") (pinfunction "AD9_19") (pintype "bidirectional"))
      (node (ref "IC10") (pin "10") (pinfunction "I/O01_10") (pintype "bidirectional"))
      (node (ref "IC16") (pin "2") (pinfunction "AD9_2") (pintype "bidirectional"))
      (node (ref "IC19") (pin "16") (pinfunction "IO209_16") (pintype "bidirectional"))
      (node (ref "IC2") (pin "18") (pinfunction "AD9_18") (pintype "bidirectional"))
      (node (ref "IC3") (pin "9") (pinfunction "AD9_9") (pintype "bidirectional"))
      (node (ref "IC5") (pin "12") (pinfunction "O1_12") (pintype "tri_state"))
      (node (ref "IC8") (pin "10") (pinfunction "I/O01_10") (pintype "bidirectional"))
      (node (ref "RN18") (pin "5") (pinfunction "5_5") (pintype "passive"))
    )
    (net (code "20") (name "AD10") (class "Default")
      (node (ref "DD3") (pin "3") (pinfunction "B0_3") (pintype "bidirectional"))
      (node (ref "IC1") (pin "20") (pinfunction "AD10_20") (pintype "bidirectional"))
      (node (ref "IC10") (pin "13") (pinfunction "I/O02_13") (pintype "bidirectional"))
      (node (ref "IC16") (pin "3") (pinfunction "AD10_3") (pintype "bidirectional"))
      (node (ref "IC19") (pin "17") (pinfunction "IO160_17") (pintype "bidirectional"))
      (node (ref "IC2") (pin "19") (pinfunction "AD10_19") (pintype "bidirectional"))
      (node (ref "IC3") (pin "10") (pinfunction "AD10_10") (pintype "bidirectional"))
      (node (ref "IC5") (pin "13") (pinfunction "O2_13") (pintype "tri_state"))
      (node (ref "IC8") (pin "13") (pinfunction "I/O02_13") (pintype "bidirectional"))
      (node (ref "RN18") (pin "4") (pinfunction "4_4") (pintype "passive"))
    )
    (net (code "21") (name "AD11") (class "Default")
      (node (ref "DD3") (pin "6") (pinfunction "B1_6") (pintype "bidirectional"))
      (node (ref "IC1") (pin "21") (pinfunction "AD11_21") (pintype "bidirectional"))
      (node (ref "IC10") (pin "14") (pinfunction "I/O03_14") (pintype "bidirectional"))
      (node (ref "IC16") (pin "4") (pinfunction "AD11_4") (pintype "bidirectional"))
      (node (ref "IC19") (pin "18") (pinfunction "IO158_18") (pintype "bidirectional"))
      (node (ref "IC2") (pin "20") (pinfunction "AD11_20") (pintype "bidirectional"))
      (node (ref "IC3") (pin "11") (pinfunction "AD11_11") (pintype "bidirectional"))
      (node (ref "IC5") (pin "15") (pinfunction "O3_15") (pintype "tri_state"))
      (node (ref "IC8") (pin "14") (pinfunction "I/O03_14") (pintype "bidirectional"))
      (node (ref "RN18") (pin "3") (pinfunction "3_3") (pintype "passive"))
    )
    (net (code "22") (name "AD12") (class "Default")
      (node (ref "DD4") (pin "10") (pinfunction "B2_10") (pintype "bidirectional"))
      (node (ref "IC1") (pin "22") (pinfunction "AD12_22") (pintype "bidirectional"))
      (node (ref "IC10") (pin "31") (pinfunction "I/O04_31") (pintype "bidirectional"))
      (node (ref "IC16") (pin "5") (pinfunction "AD12_5") (pintype "bidirectional"))
      (node (ref "IC19") (pin "19") (pinfunction "IO157_19") (pintype "bidirectional"))
      (node (ref "IC2") (pin "22") (pinfunction "AD12_22") (pintype "bidirectional"))
      (node (ref "IC3") (pin "17") (pinfunction "AD12_17") (pintype "bidirectional"))
      (node (ref "IC5") (pin "16") (pinfunction "O4_16") (pintype "tri_state"))
      (node (ref "IC8") (pin "31") (pinfunction "I/O04_31") (pintype "bidirectional"))
      (node (ref "RN18") (pin "2") (pinfunction "2_2") (pintype "passive"))
    )
    (net (code "23") (name "AD13") (class "Default")
      (node (ref "DD4") (pin "13") (pinfunction "B3_13") (pintype "bidirectional"))
      (node (ref "IC1") (pin "23") (pinfunction "AD13_23") (pintype "bidirectional"))
      (node (ref "IC10") (pin "32") (pinfunction "I/O05_32") (pintype "bidirectional"))
      (node (ref "IC16") (pin "6") (pinfunction "AD13_6") (pintype "bidirectional"))
      (node (ref "IC19") (pin "20") (pinfunction "IO155_20") (pintype "bidirectional"))
      (node (ref "IC3") (pin "18") (pinfunction "AD13_18") (pintype "bidirectional"))
      (node (ref "IC5") (pin "17") (pinfunction "O5_17") (pintype "tri_state"))
      (node (ref "IC8") (pin "32") (pinfunction "I/O05_32") (pintype "bidirectional"))
      (node (ref "RN17") (pin "2") (pinfunction "2_2") (pintype "passive"))
    )
    (net (code "24") (name "AD14") (class "Default")
      (node (ref "DD4") (pin "3") (pinfunction "B0_3") (pintype "bidirectional"))
      (node (ref "IC1") (pin "24") (pinfunction "AD14_24") (pintype "bidirectional"))
      (node (ref "IC10") (pin "35") (pinfunction "I/O06_35") (pintype "bidirectional"))
      (node (ref "IC16") (pin "7") (pinfunction "AD14_7") (pintype "bidirectional"))
      (node (ref "IC19") (pin "21") (pinfunction "IO153_21") (pintype "bidirectional"))
      (node (ref "IC3") (pin "19") (pinfunction "AD14_19") (pintype "bidirectional"))
      (node (ref "IC5") (pin "18") (pinfunction "O6_18") (pintype "tri_state"))
      (node (ref "IC8") (pin "35") (pinfunction "I/O06_35") (pintype "bidirectional"))
      (node (ref "RN17") (pin "3") (pinfunction "3_3") (pintype "passive"))
    )
    (net (code "25") (name "AD15") (class "Default")
      (node (ref "DD4") (pin "6") (pinfunction "B1_6") (pintype "bidirectional"))
      (node (ref "IC1") (pin "25") (pinfunction "AD15_25") (pintype "bidirectional"))
      (node (ref "IC10") (pin "36") (pinfunction "I/O07_36") (pintype "bidirectional"))
      (node (ref "IC16") (pin "8") (pinfunction "AD15_8") (pintype "bidirectional"))
      (node (ref "IC19") (pin "22") (pinfunction "IO152_22") (pintype "bidirectional"))
      (node (ref "IC2") (pin "25") (pinfunction "AD15_25") (pintype "bidirectional"))
      (node (ref "IC3") (pin "20") (pinfunction "AD15_20") (pintype "bidirectional"))
      (node (ref "IC5") (pin "19") (pinfunction "O7_19") (pintype "tri_state"))
      (node (ref "IC8") (pin "36") (pinfunction "I/O07_36") (pintype "bidirectional"))
      (node (ref "RN17") (pin "4") (pinfunction "4_4") (pintype "passive"))
    )
    (net (code "26") (name "AD16") (class "Default")
      (node (ref "DD8") (pin "10") (pinfunction "B2_10") (pintype "bidirectional"))
      (node (ref "IC1") (pin "26") (pinfunction "AD16_26") (pintype "bidirectional"))
      (node (ref "IC19") (pin "55") (pinfunction "IO256_55") (pintype "bidirectional"))
      (node (ref "RN17") (pin "5") (pinfunction "5_5") (pintype "passive"))
    )
    (net (code "27") (name "AD17") (class "Default")
      (node (ref "DD8") (pin "13") (pinfunction "B3_13") (pintype "bidirectional"))
      (node (ref "IC1") (pin "27") (pinfunction "AD17_27") (pintype "bidirectional"))
      (node (ref "IC19") (pin "49") (pinfunction "IO225_49") (pintype "bidirectional"))
      (node (ref "RN17") (pin "6") (pinfunction "6_6") (pintype "passive"))
    )
    (net (code "28") (name "AD18") (class "Default")
      (node (ref "DD8") (pin "3") (pinfunction "B0_3") (pintype "bidirectional"))
      (node (ref "IC1") (pin "28") (pinfunction "AD18_28") (pintype "bidirectional"))
      (node (ref "IC19") (pin "48") (pinfunction "IO227_48") (pintype "bidirectional"))
      (node (ref "RN17") (pin "7") (pinfunction "7_7") (pintype "passive"))
    )
    (net (code "29") (name "AD19") (class "Default")
      (node (ref "DD8") (pin "6") (pinfunction "B1_6") (pintype "bidirectional"))
      (node (ref "IC1") (pin "29") (pinfunction "AD19_29") (pintype "bidirectional"))
      (node (ref "IC19") (pin "47") (pinfunction "IO229_47") (pintype "bidirectional"))
      (node (ref "RN17") (pin "8") (pinfunction "8_8") (pintype "passive"))
    )
    (net (code "30") (name "AD20") (class "Default")
      (node (ref "DD9") (pin "3") (pinfunction "B0_3") (pintype "bidirectional"))
      (node (ref "IC1") (pin "30") (pinfunction "AD20_30") (pintype "bidirectional"))
      (node (ref "IC19") (pin "46") (pinfunction "IO230_46") (pintype "bidirectional"))
      (node (ref "RN17") (pin "9") (pinfunction "9_9") (pintype "passive"))
    )
    (net (code "31") (name "AD21") (class "Default")
      (node (ref "DD9") (pin "6") (pinfunction "B1_6") (pintype "bidirectional"))
      (node (ref "IC1") (pin "31") (pinfunction "AD21_31") (pintype "bidirectional"))
      (node (ref "IC16") (pin "16") (pinfunction "NS_16") (pintype "bidirectional"))
      (node (ref "IC19") (pin "45") (pinfunction "IO232_45") (pintype "bidirectional"))
      (node (ref "RN17") (pin "10") (pinfunction "10_10") (pintype "passive"))
    )
    (net (code "32") (name "BAD0") (class "Default")
      (node (ref "DD1") (pin "11") (pinfunction "O2_11") (pintype "bidirectional"))
      (node (ref "DD1") (pin "9") (pinfunction "I2_9") (pintype "bidirectional"))
      (node (ref "RN23") (pin "2") (pinfunction "1_2") (pintype "passive"))
      (node (ref "RN8") (pin "2") (pinfunction "1_2") (pintype "passive"))
      (node (ref "XP1") (pin "AB17") (pinfunction "/BDAL0_AB17") (pintype "bidirectional"))
    )
    (net (code "33") (name "BAD1") (class "Default")
      (node (ref "DD1") (pin "12") (pinfunction "I3_12") (pintype "bidirectional"))
      (node (ref "DD1") (pin "14") (pinfunction "O3_14") (pintype "bidirectional"))
      (node (ref "RN23") (pin "3") (pinfunction "1_3") (pintype "passive"))
      (node (ref "RN8") (pin "3") (pinfunction "1_3") (pintype "passive"))
      (node (ref "XP1") (pin "AB18") (pinfunction "/BDAL1_AB18") (pintype "bidirectional"))
    )
    (net (code "34") (name "BAD2") (class "Default")
      (node (ref "DD1") (pin "2") (pinfunction "O0_2") (pintype "bidirectional"))
      (node (ref "DD1") (pin "4") (pinfunction "I0_4") (pintype "bidirectional"))
      (node (ref "RN23") (pin "4") (pinfunction "1_4") (pintype "passive"))
      (node (ref "RN8") (pin "4") (pinfunction "1_4") (pintype "passive"))
      (node (ref "XP1") (pin "BB5") (pinfunction "/BDAL2_BB5") (pintype "bidirectional"))
    )
    (net (code "35") (name "BAD3") (class "Default")
      (node (ref "DD1") (pin "5") (pinfunction "O1_5") (pintype "bidirectional"))
      (node (ref "DD1") (pin "7") (pinfunction "I1_7") (pintype "bidirectional"))
      (node (ref "RN23") (pin "5") (pinfunction "1_5") (pintype "passive"))
      (node (ref "RN8") (pin "5") (pinfunction "1_5") (pintype "passive"))
      (node (ref "XP1") (pin "BB6") (pinfunction "/BDAL3_BB6") (pintype "bidirectional"))
    )
    (net (code "36") (name "BAD4") (class "Default")
      (node (ref "DD2") (pin "11") (pinfunction "O2_11") (pintype "bidirectional"))
      (node (ref "DD2") (pin "9") (pinfunction "I2_9") (pintype "bidirectional"))
      (node (ref "RN22") (pin "2") (pinfunction "1_2") (pintype "passive"))
      (node (ref "RN5") (pin "2") (pinfunction "1_2") (pintype "passive"))
      (node (ref "XP1") (pin "BB7") (pinfunction "/BDAL4_BB7") (pintype "bidirectional"))
    )
    (net (code "37") (name "BAD5") (class "Default")
      (node (ref "DD2") (pin "12") (pinfunction "I3_12") (pintype "bidirectional"))
      (node (ref "DD2") (pin "14") (pinfunction "O3_14") (pintype "bidirectional"))
      (node (ref "RN22") (pin "3") (pinfunction "1_3") (pintype "passive"))
      (node (ref "RN5") (pin "3") (pinfunction "1_3") (pintype "passive"))
      (node (ref "XP1") (pin "BB8") (pinfunction "/BDAL5_BB8") (pintype "bidirectional"))
    )
    (net (code "38") (name "BAD6") (class "Default")
      (node (ref "DD2") (pin "2") (pinfunction "O0_2") (pintype "bidirectional"))
      (node (ref "DD2") (pin "4") (pinfunction "I0_4") (pintype "bidirectional"))
      (node (ref "RN22") (pin "4") (pinfunction "1_4") (pintype "passive"))
      (node (ref "RN5") (pin "4") (pinfunction "1_4") (pintype "passive"))
      (node (ref "XP1") (pin "BB9") (pinfunction "/BDAL6_BB9") (pintype "bidirectional"))
    )
    (net (code "39") (name "BAD7") (class "Default")
      (node (ref "DD2") (pin "5") (pinfunction "O1_5") (pintype "bidirectional"))
      (node (ref "DD2") (pin "7") (pinfunction "I1_7") (pintype "bidirectional"))
      (node (ref "RN22") (pin "5") (pinfunction "1_5") (pintype "passive"))
      (node (ref "RN5") (pin "5") (pinfunction "1_5") (pintype "passive"))
      (node (ref "XP1") (pin "BB10") (pinfunction "/BDAL7_BB10") (pintype "bidirectional"))
    )
    (net (code "40") (name "BAD8") (class "Default")
      (node (ref "DD3") (pin "11") (pinfunction "O2_11") (pintype "bidirectional"))
      (node (ref "DD3") (pin "9") (pinfunction "I2_9") (pintype "bidirectional"))
      (node (ref "RN26") (pin "2") (pinfunction "1_2") (pintype "passive"))
      (node (ref "RN4") (pin "2") (pinfunction "1_2") (pintype "passive"))
      (node (ref "XP1") (pin "BB11") (pinfunction "/BDAL8_BB11") (pintype "bidirectional"))
    )
    (net (code "41") (name "BAD9") (class "Default")
      (node (ref "DD3") (pin "12") (pinfunction "I3_12") (pintype "bidirectional"))
      (node (ref "DD3") (pin "14") (pinfunction "O3_14") (pintype "bidirectional"))
      (node (ref "RN26") (pin "3") (pinfunction "1_3") (pintype "passive"))
      (node (ref "RN4") (pin "3") (pinfunction "1_3") (pintype "passive"))
      (node (ref "XP1") (pin "BB12") (pinfunction "/BDAL9_BB12") (pintype "bidirectional"))
    )
    (net (code "42") (name "BAD10") (class "Default")
      (node (ref "DD3") (pin "2") (pinfunction "O0_2") (pintype "bidirectional"))
      (node (ref "DD3") (pin "4") (pinfunction "I0_4") (pintype "bidirectional"))
      (node (ref "RN26") (pin "4") (pinfunction "1_4") (pintype "passive"))
      (node (ref "RN4") (pin "4") (pinfunction "1_4") (pintype "passive"))
      (node (ref "XP1") (pin "BB13") (pinfunction "/BDAL10_BB13") (pintype "bidirectional"))
    )
    (net (code "43") (name "BAD11") (class "Default")
      (node (ref "DD3") (pin "5") (pinfunction "O1_5") (pintype "bidirectional"))
      (node (ref "DD3") (pin "7") (pinfunction "I1_7") (pintype "bidirectional"))
      (node (ref "RN26") (pin "5") (pinfunction "1_5") (pintype "passive"))
      (node (ref "RN4") (pin "5") (pinfunction "1_5") (pintype "passive"))
      (node (ref "XP1") (pin "BB14") (pinfunction "/BDAL11_BB14") (pintype "bidirectional"))
    )
    (net (code "44") (name "BAD12") (class "Default")
      (node (ref "DD4") (pin "11") (pinfunction "O2_11") (pintype "bidirectional"))
      (node (ref "DD4") (pin "9") (pinfunction "I2_9") (pintype "bidirectional"))
      (node (ref "RN21") (pin "2") (pinfunction "1_2") (pintype "passive"))
      (node (ref "RN7") (pin "2") (pinfunction "1_2") (pintype "passive"))
      (node (ref "XP1") (pin "BB15") (pinfunction "/BDAL12_BB15") (pintype "bidirectional"))
    )
    (net (code "45") (name "BAD13") (class "Default")
      (node (ref "DD4") (pin "12") (pinfunction "I3_12") (pintype "bidirectional"))
      (node (ref "DD4") (pin "14") (pinfunction "O3_14") (pintype "bidirectional"))
      (node (ref "RN21") (pin "3") (pinfunction "1_3") (pintype "passive"))
      (node (ref "RN7") (pin "3") (pinfunction "1_3") (pintype "passive"))
      (node (ref "XP1") (pin "BB16") (pinfunction "/BDAL13_BB16") (pintype "bidirectional"))
    )
    (net (code "46") (name "BAD14") (class "Default")
      (node (ref "DD4") (pin "2") (pinfunction "O0_2") (pintype "bidirectional"))
      (node (ref "DD4") (pin "4") (pinfunction "I0_4") (pintype "bidirectional"))
      (node (ref "RN21") (pin "4") (pinfunction "1_4") (pintype "passive"))
      (node (ref "RN7") (pin "4") (pinfunction "1_4") (pintype "passive"))
      (node (ref "XP1") (pin "BB17") (pinfunction "/BDAL14_BB17") (pintype "bidirectional"))
    )
    (net (code "47") (name "BAD15") (class "Default")
      (node (ref "DD4") (pin "5") (pinfunction "O1_5") (pintype "bidirectional"))
      (node (ref "DD4") (pin "7") (pinfunction "I1_7") (pintype "bidirectional"))
      (node (ref "RN21") (pin "5") (pinfunction "1_5") (pintype "passive"))
      (node (ref "RN7") (pin "5") (pinfunction "1_5") (pintype "passive"))
      (node (ref "XP1") (pin "BB18") (pinfunction "/BDAL15_BB18") (pintype "bidirectional"))
    )
    (net (code "48") (name "BAD16") (class "Default")
      (node (ref "DD8") (pin "11") (pinfunction "O2_11") (pintype "bidirectional"))
      (node (ref "DD8") (pin "9") (pinfunction "I2_9") (pintype "bidirectional"))
      (node (ref "RN24") (pin "2") (pinfunction "1_2") (pintype "passive"))
      (node (ref "RN9") (pin "2") (pinfunction "1_2") (pintype "passive"))
      (node (ref "XP1") (pin "AA3") (pinfunction "/BDAL16_AA3") (pintype "bidirectional"))
    )
    (net (code "49") (name "BAD17") (class "Default")
      (node (ref "DD8") (pin "12") (pinfunction "I3_12") (pintype "bidirectional"))
      (node (ref "DD8") (pin "14") (pinfunction "O3_14") (pintype "bidirectional"))
      (node (ref "RN24") (pin "3") (pinfunction "1_3") (pintype "passive"))
      (node (ref "RN9") (pin "3") (pinfunction "1_3") (pintype "passive"))
      (node (ref "XP1") (pin "AA4") (pinfunction "/BDAL17_AA4") (pintype "bidirectional"))
    )
    (net (code "50") (name "BAD18") (class "Default")
      (node (ref "DD8") (pin "2") (pinfunction "O0_2") (pintype "bidirectional"))
      (node (ref "DD8") (pin "4") (pinfunction "I0_4") (pintype "bidirectional"))
      (node (ref "RN24") (pin "4") (pinfunction "1_4") (pintype "passive"))
      (node (ref "RN9") (pin "4") (pinfunction "1_4") (pintype "passive"))
      (node (ref "XP1") (pin "BA3") (pinfunction "/BDAL18_BA3") (pintype "bidirectional"))
    )
    (net (code "51") (name "BAD19") (class "Default")
      (node (ref "DD8") (pin "5") (pinfunction "O1_5") (pintype "bidirectional"))
      (node (ref "DD8") (pin "7") (pinfunction "I1_7") (pintype "bidirectional"))
      (node (ref "RN24") (pin "5") (pinfunction "1_5") (pintype "passive"))
      (node (ref "RN9") (pin "5") (pinfunction "1_5") (pintype "passive"))
      (node (ref "XP1") (pin "BA4") (pinfunction "/BDAL19_BA4") (pintype "bidirectional"))
    )
    (net (code "52") (name "BAD20") (class "Default")
      (node (ref "DD9") (pin "2") (pinfunction "O0_2") (pintype "bidirectional"))
      (node (ref "DD9") (pin "4") (pinfunction "I0_4") (pintype "bidirectional"))
      (node (ref "RN10") (pin "2") (pinfunction "1_2") (pintype "passive"))
      (node (ref "RN25") (pin "2") (pinfunction "1_2") (pintype "passive"))
      (node (ref "XP1") (pin "BA5") (pinfunction "/BDAL20_BA5") (pintype "bidirectional"))
    )
    (net (code "53") (name "BAD21") (class "Default")
      (node (ref "DD9") (pin "5") (pinfunction "O1_5") (pintype "bidirectional"))
      (node (ref "DD9") (pin "7") (pinfunction "I1_7") (pintype "bidirectional"))
      (node (ref "RN10") (pin "3") (pinfunction "1_3") (pintype "passive"))
      (node (ref "RN25") (pin "3") (pinfunction "1_3") (pintype "passive"))
      (node (ref "XP1") (pin "BA6") (pinfunction "/BDAL21_BA6") (pintype "bidirectional"))
    )
    (net (code "54") (name "BBS7") (class "Default")
      (node (ref "DD16") (pin "3") (pinfunction "B0_3") (pintype "bidirectional"))
      (node (ref "RN15") (pin "3") (pinfunction "1_3") (pintype "passive"))
      (node (ref "RN31") (pin "3") (pinfunction "1_3") (pintype "passive"))
      (node (ref "XP1") (pin "AB13") (pinfunction "/BBS7_AB13") (pintype "bidirectional"))
    )
    (net (code "55") (name "BDCOK") (class "Default")
      (node (ref "D5") (pin "A") (pinfunction "A_A") (pintype "passive"))
      (node (ref "DD6") (pin "7") (pinfunction "I1_7") (pintype "bidirectional"))
      (node (ref "RN16") (pin "3") (pinfunction "1_3") (pintype "passive"))
      (node (ref "RN32") (pin "3") (pinfunction "1_3") (pintype "passive"))
      (node (ref "XP1") (pin "BA1") (pinfunction "BDCOK_BA1") (pintype "bidirectional"))
    )
    (net (code "56") (name "BDIN") (class "Default")
      (node (ref "DD15") (pin "6") (pinfunction "B1_6") (pintype "bidirectional"))
      (node (ref "IC19") (pin "24") (pinfunction "IO150_24") (pintype "bidirectional"))
      (node (ref "RN14") (pin "3") (pinfunction "1_3") (pintype "passive"))
      (node (ref "RN30") (pin "3") (pinfunction "1_3") (pintype "passive"))
      (node (ref "XP1") (pin "AB7") (pinfunction "/BDIN_AB7") (pintype "bidirectional"))
    )
    (net (code "57") (name "BDMGO") (class "Default")
      (node (ref "DD14") (pin "5") (pinfunction "O1_5") (pintype "bidirectional"))
      (node (ref "RN13") (pin "3") (pinfunction "1_3") (pintype "passive"))
      (node (ref "RN29") (pin "3") (pinfunction "1_3") (pintype "passive"))
      (node (ref "XP1") (pin "AB15") (pinfunction "/BDMGO_AB15") (pintype "bidirectional"))
    )
    (net (code "58") (name "BDMR") (class "Default")
      (node (ref "DD5") (pin "7") (pinfunction "I1_7") (pintype "bidirectional"))
      (node (ref "RN11") (pin "2") (pinfunction "1_2") (pintype "passive"))
      (node (ref "RN27") (pin "2") (pinfunction "1_2") (pintype "passive"))
      (node (ref "XP1") (pin "AA12") (pinfunction "/BDMR_AA12") (pintype "bidirectional"))
    )
    (net (code "59") (name "BDOUT") (class "Default")
      (node (ref "DD15") (pin "10") (pinfunction "B2_10") (pintype "bidirectional"))
      (node (ref "RN14") (pin "4") (pinfunction "1_4") (pintype "passive"))
      (node (ref "RN30") (pin "4") (pinfunction "1_4") (pintype "passive"))
      (node (ref "XP1") (pin "AB5") (pinfunction "/BDOUT_AB5") (pintype "bidirectional"))
    )
    (net (code "60") (name "BEVNT") (class "Default")
      (node (ref "DD5") (pin "12") (pinfunction "I3_12") (pintype "bidirectional"))
      (node (ref "RN11") (pin "4") (pinfunction "1_4") (pintype "passive"))
      (node (ref "RN27") (pin "4") (pinfunction "1_4") (pintype "passive"))
      (node (ref "XP1") (pin "BA14") (pinfunction "/BEVNT_BA14") (pintype "bidirectional"))
    )
    (net (code "61") (name "BHALT") (class "Default")
      (node (ref "DD6") (pin "4") (pinfunction "I0_4") (pintype "bidirectional"))
      (node (ref "RN16") (pin "2") (pinfunction "1_2") (pintype "passive"))
      (node (ref "RN32") (pin "2") (pinfunction "1_2") (pintype "passive"))
      (node (ref "XP1") (pin "AA13") (pinfunction "/BHALT_AA13") (pintype "bidirectional"))
    )
    (net (code "62") (name "BHLTM") (class "Default")
      (node (ref "DD14") (pin "2") (pinfunction "O0_2") (pintype "bidirectional"))
      (node (ref "RN13") (pin "2") (pinfunction "1_2") (pintype "passive"))
      (node (ref "RN29") (pin "2") (pinfunction "1_2") (pintype "passive"))
      (node (ref "XP1") (pin "BA7") (pinfunction "P$7_BA7") (pintype "bidirectional"))
    )
    (net (code "63") (name "BIAKO") (class "Default")
      (node (ref "DD14") (pin "11") (pinfunction "O2_11") (pintype "bidirectional"))
      (node (ref "RN13") (pin "4") (pinfunction "1_4") (pintype "passive"))
      (node (ref "RN29") (pin "4") (pinfunction "1_4") (pintype "passive"))
      (node (ref "XP1") (pin "AB12") (pinfunction "/BIAKO_AB12") (pintype "bidirectional"))
    )
    (net (code "64") (name "BINIT") (class "Default")
      (node (ref "DD14") (pin "14") (pinfunction "O3_14") (pintype "bidirectional"))
      (node (ref "RN13") (pin "5") (pinfunction "1_5") (pintype "passive"))
      (node (ref "RN29") (pin "5") (pinfunction "1_5") (pintype "passive"))
      (node (ref "XP1") (pin "AB16") (pinfunction "/BINIT_AB16") (pintype "bidirectional"))
    )
    (net (code "65") (name "BIRQ4") (class "Default")
      (node (ref "DD7") (pin "12") (pinfunction "I3_12") (pintype "bidirectional"))
      (node (ref "RN12") (pin "5") (pinfunction "1_5") (pintype "passive"))
      (node (ref "RN28") (pin "5") (pinfunction "1_5") (pintype "passive"))
      (node (ref "XP1") (pin "AB10") (pinfunction "/BIRQ4_AB10") (pintype "bidirectional"))
    )
    (net (code "66") (name "BIRQ5") (class "Default")
      (node (ref "DD7") (pin "9") (pinfunction "I2_9") (pintype "bidirectional"))
      (node (ref "RN12") (pin "4") (pinfunction "1_4") (pintype "passive"))
      (node (ref "RN28") (pin "4") (pinfunction "1_4") (pintype "passive"))
      (node (ref "XP1") (pin "AA1") (pinfunction "/BIRQ5_AA1") (pintype "bidirectional"))
    )
    (net (code "67") (name "BIRQ6") (class "Default")
      (node (ref "DD7") (pin "7") (pinfunction "I1_7") (pintype "bidirectional"))
      (node (ref "RN12") (pin "3") (pinfunction "1_3") (pintype "passive"))
      (node (ref "RN28") (pin "3") (pinfunction "1_3") (pintype "passive"))
      (node (ref "XP1") (pin "AA2") (pinfunction "/BIRQ6_AA2") (pintype "bidirectional"))
    )
    (net (code "68") (name "BIRQ7") (class "Default")
      (node (ref "DD7") (pin "4") (pinfunction "I0_4") (pintype "bidirectional"))
      (node (ref "RN12") (pin "2") (pinfunction "1_2") (pintype "passive"))
      (node (ref "RN28") (pin "2") (pinfunction "1_2") (pintype "passive"))
      (node (ref "XP1") (pin "BA13") (pinfunction "/BIRQ7_BA13") (pintype "bidirectional"))
    )
    (net (code "69") (name "BPOK") (class "Default")
      (node (ref "D2") (pin "A") (pinfunction "A_A") (pintype "passive"))
      (node (ref "DD6") (pin "12") (pinfunction "I3_12") (pintype "bidirectional"))
      (node (ref "DD6") (pin "9") (pinfunction "I2_9") (pintype "bidirectional"))
      (node (ref "RN16") (pin "4") (pinfunction "1_4") (pintype "passive"))
      (node (ref "RN32") (pin "4") (pinfunction "1_4") (pintype "passive"))
      (node (ref "XP1") (pin "BA2") (pinfunction "BPOK_BA2") (pintype "bidirectional"))
    )
    (net (code "70") (name "BRPLY") (class "Default")
      (node (ref "DD16") (pin "11") (pinfunction "O2_11") (pintype "bidirectional"))
      (node (ref "DD16") (pin "9") (pinfunction "I2_9") (pintype "bidirectional"))
      (node (ref "RN15") (pin "5") (pinfunction "1_5") (pintype "passive"))
      (node (ref "RN31") (pin "5") (pinfunction "1_5") (pintype "passive"))
      (node (ref "XP1") (pin "AB6") (pinfunction "/BRPLY_AB6") (pintype "bidirectional"))
    )
    (net (code "71") (name "BS") (class "Default")
      (node (ref "IC1") (pin "34") (pinfunction "/BS_34") (pintype "bidirectional"))
      (node (ref "IC19") (pin "205") (pinfunction "IO198_205") (pintype "bidirectional"))
      (node (ref "RN1") (pin "3") (pinfunction "3_3") (pintype "passive"))
    )
    (net (code "72") (name "BS7") (class "Default")
      (node (ref "DD16") (pin "2") (pinfunction "O0_2") (pintype "bidirectional"))
      (node (ref "DD16") (pin "4") (pinfunction "I0_4") (pintype "bidirectional"))
      (node (ref "IC19") (pin "44") (pinfunction "IO233_44") (pintype "bidirectional"))
      (node (ref "IC2") (pin "26") (pinfunction "BS_26") (pintype "bidirectional"))
      (node (ref "RN20") (pin "2") (pinfunction "2_2") (pintype "passive"))
    )
    (net (code "73") (name "BSACK") (class "Default")
      (node (ref "DD5") (pin "9") (pinfunction "I2_9") (pintype "bidirectional"))
      (node (ref "RN11") (pin "3") (pinfunction "1_3") (pintype "passive"))
      (node (ref "RN27") (pin "3") (pinfunction "1_3") (pintype "passive"))
      (node (ref "XP1") (pin "BA12") (pinfunction "/BSACK_BA12") (pintype "bidirectional"))
    )
    (net (code "74") (name "BSYNC") (class "Default")
      (node (ref "DD15") (pin "3") (pinfunction "B0_3") (pintype "bidirectional"))
      (node (ref "RN14") (pin "2") (pinfunction "1_2") (pintype "passive"))
      (node (ref "RN30") (pin "2") (pinfunction "1_2") (pintype "passive"))
      (node (ref "XP1") (pin "AB8") (pinfunction "/BSYNC_AB8") (pintype "bidirectional"))
    )
    (net (code "75") (name "BWTBT") (class "Default")
      (node (ref "DD15") (pin "13") (pinfunction "B3_13") (pintype "bidirectional"))
      (node (ref "RN14") (pin "5") (pinfunction "1_5") (pintype "passive"))
      (node (ref "RN30") (pin "5") (pinfunction "1_5") (pintype "passive"))
      (node (ref "XP1") (pin "AB9") (pinfunction "/BWTBT_AB9") (pintype "bidirectional"))
    )
    (net (code "76") (name "CLK") (class "Default")
      (node (ref "IC16") (pin "24") (pinfunction "CLK_24") (pintype "bidirectional"))
      (node (ref "IC19") (pin "3") (pinfunction "IO195_3") (pintype "bidirectional"))
      (node (ref "R14") (pin "2") (pinfunction "2_2") (pintype "passive"))
    )
    (net (code "77") (name "CS_ROM") (class "Default")
      (node (ref "IC19") (pin "151") (pinfunction "IO32_151") (pintype "bidirectional"))
      (node (ref "IC3") (pin "23") (pinfunction "CE_23") (pintype "bidirectional"))
    )
    (net (code "78") (name "DCLO") (class "Default")
      (node (ref "DD6") (pin "6") (pinfunction "B1_6") (pintype "bidirectional"))
      (node (ref "IC1") (pin "52") (pinfunction "/DCLO_52") (pintype "bidirectional"))
      (node (ref "IC16") (pin "13") (pinfunction "/DCLO_13") (pintype "bidirectional"))
      (node (ref "IC19") (pin "117") (pinfunction "IO46_117") (pintype "bidirectional"))
      (node (ref "IC2") (pin "40") (pinfunction "DCLO_40") (pintype "bidirectional"))
      (node (ref "RN6") (pin "9") (pinfunction "9_9") (pintype "passive"))
    )
    (net (code "79") (name "DCLO_F") (class "Default")
      (node (ref "IC19") (pin "131") (pinfunction "IO83_131") (pintype "bidirectional"))
      (node (ref "IC4") (pin "5") (pinfunction "I_5") (pintype "input"))
    )
    (net (code "80") (name "DCLO_P") (class "Default")
      (node (ref "IC17") (pin "10") (pinfunction "O_10") (pintype "output"))
      (node (ref "IC19") (pin "123") (pinfunction "IO104_123") (pintype "bidirectional"))
      (node (ref "R3") (pin "1") (pinfunction "1_1") (pintype "passive"))
      (node (ref "R4") (pin "2") (pinfunction "2_2") (pintype "passive"))
    )
    (net (code "81") (name "DIN") (class "Default")
      (node (ref "DD15") (pin "5") (pinfunction "O1_5") (pintype "bidirectional"))
      (node (ref "DD15") (pin "7") (pinfunction "I1_7") (pintype "bidirectional"))
      (node (ref "IC19") (pin "34") (pinfunction "IO168_34") (pintype "bidirectional"))
      (node (ref "IC2") (pin "38") (pinfunction "DIN_38") (pintype "bidirectional"))
      (node (ref "IC3") (pin "1") (pinfunction "DIN_1") (pintype "bidirectional"))
      (node (ref "RN20") (pin "3") (pinfunction "3_3") (pintype "passive"))
    )
    (net (code "82") (name "DIN_VM") (class "Default")
      (node (ref "IC1") (pin "1") (pinfunction "/DIN_1") (pintype "bidirectional"))
      (node (ref "IC16") (pin "18") (pinfunction "/DIN_18") (pintype "bidirectional"))
      (node (ref "IC19") (pin "197") (pinfunction "IO129_197") (pintype "bidirectional"))
      (node (ref "RN6") (pin "2") (pinfunction "2_2") (pintype "passive"))
    )
    (net (code "83") (name "DMGO") (class "Default")
      (node (ref "DD14") (pin "6") (pinfunction "B1_6") (pintype "bidirectional"))
      (node (ref "IC1") (pin "6") (pinfunction "/DMGO_6") (pintype "bidirectional"))
      (node (ref "RN19") (pin "4") (pinfunction "4_4") (pintype "passive"))
    )
    (net (code "84") (name "DMR") (class "Default")
      (node (ref "DD5") (pin "6") (pinfunction "B1_6") (pintype "bidirectional"))
      (node (ref "IC1") (pin "8") (pinfunction "/DMR_8") (pintype "bidirectional"))
      (node (ref "RN19") (pin "6") (pinfunction "6_6") (pintype "passive"))
    )
    (net (code "85") (name "DOUT") (class "Default")
      (node (ref "DD15") (pin "11") (pinfunction "O2_11") (pintype "bidirectional"))
      (node (ref "DD15") (pin "9") (pinfunction "I2_9") (pintype "bidirectional"))
      (node (ref "IC19") (pin "33") (pinfunction "IO169_33") (pintype "bidirectional"))
      (node (ref "IC2") (pin "37") (pinfunction "DOUT_37") (pintype "bidirectional"))
      (node (ref "RN20") (pin "4") (pinfunction "4_4") (pintype "passive"))
    )
    (net (code "86") (name "DOUT_VM") (class "Default")
      (node (ref "IC1") (pin "2") (pinfunction "/DOUT_2") (pintype "bidirectional"))
      (node (ref "IC16") (pin "20") (pinfunction "DOUT_20") (pintype "bidirectional"))
      (node (ref "IC19") (pin "198") (pinfunction "IO208_198") (pintype "bidirectional"))
      (node (ref "RN6") (pin "3") (pinfunction "3_3") (pintype "passive"))
    )
    (net (code "87") (name "ESYNC") (class "Default")
      (node (ref "IC19") (pin "126") (pinfunction "IO107_126") (pintype "bidirectional"))
      (node (ref "IC2") (pin "41") (pinfunction "SYNC_41") (pintype "bidirectional"))
    )
    (net (code "88") (name "EVNT") (class "Default")
      (node (ref "DD5") (pin "13") (pinfunction "B3_13") (pintype "bidirectional"))
      (node (ref "IC1") (pin "44") (pinfunction "/EVNT_44") (pintype "bidirectional"))
      (node (ref "IC19") (pin "71") (pinfunction "IO185_71") (pintype "bidirectional"))
      (node (ref "RN1") (pin "10") (pinfunction "10_10") (pintype "passive"))
    )
    (net (code "89") (name "EX_SYNC") (class "Default")
      (node (ref "DD15") (pin "2") (pinfunction "O0_2") (pintype "bidirectional"))
      (node (ref "IC19") (pin "28") (pinfunction "IO176_28") (pintype "bidirectional"))
      (node (ref "RN20") (pin "8") (pinfunction "8_8") (pintype "passive"))
    )
    (net (code "90") (name "FR0") (class "Default")
      (node (ref "IC19") (pin "138") (pinfunction "IO93_138") (pintype "bidirectional"))
      (node (ref "IC2") (pin "3") (pinfunction "FR0_3") (pintype "bidirectional"))
    )
    (net (code "91") (name "FR1") (class "Default")
      (node (ref "IC19") (pin "137") (pinfunction "IO91_137") (pintype "bidirectional"))
      (node (ref "IC2") (pin "4") (pinfunction "FR1_4") (pintype "bidirectional"))
    )
    (net (code "92") (name "FR2") (class "Default")
      (node (ref "IC19") (pin "136") (pinfunction "IO89_136") (pintype "bidirectional"))
      (node (ref "IC2") (pin "5") (pinfunction "FR2_5") (pintype "bidirectional"))
    )
    (net (code "93") (name "FR3") (class "Default")
      (node (ref "IC19") (pin "135") (pinfunction "IO88_135") (pintype "bidirectional"))
      (node (ref "IC2") (pin "6") (pinfunction "FR3_6") (pintype "bidirectional"))
    )
    (net (code "94") (name "GND") (class "Default")
      (node (ref "C1") (pin "-") (pinfunction "-_-") (pintype "passive"))
      (node (ref "C10") (pin "2") (pinfunction "2_2") (pintype "passive"))
      (node (ref "C12") (pin "2") (pinfunction "2_2") (pintype "passive"))
      (node (ref "C13") (pin "2") (pinfunction "2_2") (pintype "passive"))
      (node (ref "C14") (pin "2") (pinfunction "2_2") (pintype "passive"))
      (node (ref "C15") (pin "2") (pinfunction "2_2") (pintype "passive"))
      (node (ref "C16") (pin "2") (pinfunction "2_2") (pintype "passive"))
      (node (ref "C17") (pin "2") (pinfunction "2_2") (pintype "passive"))
      (node (ref "C18") (pin "-") (pinfunction "-_-") (pintype "passive"))
      (node (ref "C19") (pin "-") (pinfunction "-_-") (pintype "passive"))
      (node (ref "C2") (pin "2") (pinfunction "2_2") (pintype "passive"))
      (node (ref "C20") (pin "2") (pinfunction "2_2") (pintype "passive"))
      (node (ref "C21") (pin "2") (pinfunction "2_2") (pintype "passive"))
      (node (ref "C22") (pin "2") (pinfunction "2_2") (pintype "passive"))
      (node (ref "C23") (pin "2") (pinfunction "2_2") (pintype "passive"))
      (node (ref "C24") (pin "2") (pinfunction "2_2") (pintype "passive"))
      (node (ref "C25") (pin "2") (pinfunction "2_2") (pintype "passive"))
      (node (ref "C26") (pin "2") (pinfunction "2_2") (pintype "passive"))
      (node (ref "C27") (pin "-") (pinfunction "-_-") (pintype "passive"))
      (node (ref "C28") (pin "2") (pinfunction "2_2") (pintype "passive"))
      (node (ref "C29") (pin "2") (pinfunction "2_2") (pintype "passive"))
      (node (ref "C3") (pin "2") (pinfunction "2_2") (pintype "passive"))
      (node (ref "C30") (pin "2") (pinfunction "2_2") (pintype "passive"))
      (node (ref "C31") (pin "2") (pinfunction "2_2") (pintype "passive"))
      (node (ref "C32") (pin "2") (pinfunction "2_2") (pintype "passive"))
      (node (ref "C33") (pin "2") (pinfunction "2_2") (pintype "passive"))
      (node (ref "C34") (pin "2") (pinfunction "2_2") (pintype "passive"))
      (node (ref "C35") (pin "2") (pinfunction "2_2") (pintype "passive"))
      (node (ref "C36") (pin "2") (pinfunction "2_2") (pintype "passive"))
      (node (ref "C37") (pin "2") (pinfunction "2_2") (pintype "passive"))
      (node (ref "C4") (pin "2") (pinfunction "2_2") (pintype "passive"))
      (node (ref "C40") (pin "2") (pinfunction "2_2") (pintype "passive"))
      (node (ref "C41") (pin "2") (pinfunction "2_2") (pintype "passive"))
      (node (ref "C42") (pin "2") (pinfunction "2_2") (pintype "passive"))
      (node (ref "C43") (pin "2") (pinfunction "2_2") (pintype "passive"))
      (node (ref "C44") (pin "-") (pinfunction "-_-") (pintype "passive"))
      (node (ref "C45") (pin "-") (pinfunction "-_-") (pintype "passive"))
      (node (ref "C46") (pin "2") (pinfunction "2_2") (pintype "passive"))
      (node (ref "C5") (pin "2") (pinfunction "2_2") (pintype "passive"))
      (node (ref "C6") (pin "-") (pinfunction "-_-") (pintype "passive"))
      (node (ref "C7") (pin "2") (pinfunction "2_2") (pintype "passive"))
      (node (ref "C8") (pin "2") (pinfunction "2_2") (pintype "passive"))
      (node (ref "D8") (pin "K") (pinfunction "C_K") (pintype "passive"))
      (node (ref "D9") (pin "K") (pinfunction "C_K") (pintype "passive"))
      (node (ref "DD1") (pin "8") (pinfunction "GND_8") (pintype "bidirectional"))
      (node (ref "DD14") (pin "15") (pinfunction "CO_15") (pintype "bidirectional"))
      (node (ref "DD14") (pin "8") (pinfunction "GND_8") (pintype "bidirectional"))
      (node (ref "DD15") (pin "8") (pinfunction "GND_8") (pintype "bidirectional"))
      (node (ref "DD16") (pin "8") (pinfunction "GND_8") (pintype "bidirectional"))
      (node (ref "DD2") (pin "8") (pinfunction "GND_8") (pintype "bidirectional"))
      (node (ref "DD3") (pin "8") (pinfunction "GND_8") (pintype "bidirectional"))
      (node (ref "DD4") (pin "8") (pinfunction "GND_8") (pintype "bidirectional"))
      (node (ref "DD5") (pin "1") (pinfunction "CI_1") (pintype "bidirectional"))
      (node (ref "DD5") (pin "8") (pinfunction "GND_8") (pintype "bidirectional"))
      (node (ref "DD6") (pin "1") (pinfunction "CI_1") (pintype "bidirectional"))
      (node (ref "DD6") (pin "8") (pinfunction "GND_8") (pintype "bidirectional"))
      (node (ref "DD7") (pin "1") (pinfunction "CI_1") (pintype "bidirectional"))
      (node (ref "DD7") (pin "8") (pinfunction "GND_8") (pintype "bidirectional"))
      (node (ref "DD8") (pin "8") (pinfunction "GND_8") (pintype "bidirectional"))
      (node (ref "DD9") (pin "8") (pinfunction "GND_8") (pintype "bidirectional"))
      (node (ref "IC1") (pin "32") (pinfunction "GND_32") (pintype "bidirectional"))
      (node (ref "IC1") (pin "38") (pinfunction "GND_38") (pintype "bidirectional"))
      (node (ref "IC1") (pin "40") (pinfunction "GND_40") (pintype "bidirectional"))
      (node (ref "IC1") (pin "41") (pinfunction "GND_41") (pintype "bidirectional"))
      (node (ref "IC1") (pin "42") (pinfunction "GND_42") (pintype "bidirectional"))
      (node (ref "IC1") (pin "45") (pinfunction "/ET_45") (pintype "bidirectional"))
      (node (ref "IC1") (pin "9") (pinfunction "GND_9") (pintype "bidirectional"))
      (node (ref "IC10") (pin "12") (pinfunction "GND_12") (pintype "power_in"))
      (node (ref "IC10") (pin "34") (pinfunction "GND_34") (pintype "power_in"))
      (node (ref "IC16") (pin "25") (pinfunction "GND_25") (pintype "bidirectional"))
      (node (ref "IC16") (pin "33") (pinfunction "GND_33") (pintype "bidirectional"))
      (node (ref "IC16") (pin "9") (pinfunction "GND_9") (pintype "bidirectional"))
      (node (ref "IC19") (pin "116") (pinfunction "GND_116") (pintype "power_in"))
      (node (ref "IC19") (pin "134") (pinfunction "GND_134") (pintype "power_in"))
      (node (ref "IC19") (pin "14") (pinfunction "GND_14") (pintype "power_in"))
      (node (ref "IC19") (pin "152") (pinfunction "GND_152") (pintype "power_in"))
      (node (ref "IC19") (pin "174") (pinfunction "GND_174") (pintype "power_in"))
      (node (ref "IC19") (pin "180") (pinfunction "GND_180") (pintype "power_in"))
      (node (ref "IC19") (pin "185") (pinfunction "GND_185") (pintype "power_in"))
      (node (ref "IC19") (pin "200") (pinfunction "GND_200") (pintype "power_in"))
      (node (ref "IC19") (pin "32") (pinfunction "GND_32") (pintype "power_in"))
      (node (ref "IC19") (pin "50") (pinfunction "GND_50") (pintype "power_in"))
      (node (ref "IC19") (pin "72") (pinfunction "GND_72") (pintype "power_in"))
      (node (ref "IC19") (pin "75") (pinfunction "GND_75") (pintype "power_in"))
      (node (ref "IC19") (pin "82") (pinfunction "GND_82") (pintype "power_in"))
      (node (ref "IC19") (pin "94") (pinfunction "GND_94") (pintype "power_in"))
      (node (ref "IC2") (pin "21") (pinfunction "GND_21") (pintype "bidirectional"))
      (node (ref "IC2") (pin "24") (pinfunction "ACL1_24") (pintype "bidirectional"))
      (node (ref "IC2") (pin "29") (pinfunction "BSYD_29") (pintype "bidirectional"))
      (node (ref "IC3") (pin "12") (pinfunction "GND_12") (pintype "bidirectional"))
      (node (ref "IC7") (pin "12") (pinfunction "GND_12") (pintype "power_in"))
      (node (ref "IC7") (pin "34") (pinfunction "GND_34") (pintype "power_in"))
      (node (ref "IC8") (pin "12") (pinfunction "GND_12") (pintype "power_in"))
      (node (ref "IC8") (pin "34") (pinfunction "GND_34") (pintype "power_in"))
      (node (ref "IC9") (pin "12") (pinfunction "GND_12") (pintype "power_in"))
      (node (ref "IC9") (pin "34") (pinfunction "GND_34") (pintype "power_in"))
      (node (ref "JP1") (pin "1") (pinfunction "1_1") (pintype "passive"))
      (node (ref "JP3") (pin "10") (pinfunction "10_10") (pintype "passive"))
      (node (ref "JP3") (pin "2") (pinfunction "2_2") (pintype "passive"))
      (node (ref "JP61") (pin "2") (pinfunction "2_2") (pintype "passive"))
      (node (ref "Q3") (pin "1") (pinfunction "E_1") (pintype "passive"))
      (node (ref "R1") (pin "1") (pinfunction "1_1") (pintype "passive"))
      (node (ref "R20") (pin "1") (pinfunction "1_1") (pintype "passive"))
      (node (ref "RN10") (pin "6") (pinfunction "1_6") (pintype "passive"))
      (node (ref "RN11") (pin "6") (pinfunction "1_6") (pintype "passive"))
      (node (ref "RN12") (pin "6") (pinfunction "1_6") (pintype "passive"))
      (node (ref "RN13") (pin "6") (pinfunction "1_6") (pintype "passive"))
      (node (ref "RN14") (pin "6") (pinfunction "1_6") (pintype "passive"))
      (node (ref "RN15") (pin "6") (pinfunction "1_6") (pintype "passive"))
      (node (ref "RN16") (pin "6") (pinfunction "1_6") (pintype "passive"))
      (node (ref "RN21") (pin "6") (pinfunction "1_6") (pintype "passive"))
      (node (ref "RN22") (pin "6") (pinfunction "1_6") (pintype "passive"))
      (node (ref "RN23") (pin "6") (pinfunction "1_6") (pintype "passive"))
      (node (ref "RN24") (pin "6") (pinfunction "1_6") (pintype "passive"))
      (node (ref "RN25") (pin "6") (pinfunction "1_6") (pintype "passive"))
      (node (ref "RN26") (pin "6") (pinfunction "1_6") (pintype "passive"))
      (node (ref "RN27") (pin "6") (pinfunction "1_6") (pintype "passive"))
      (node (ref "RN28") (pin "6") (pinfunction "1_6") (pintype "passive"))
      (node (ref "RN29") (pin "6") (pinfunction "1_6") (pintype "passive"))
      (node (ref "RN30") (pin "6") (pinfunction "1_6") (pintype "passive"))
      (node (ref "RN31") (pin "6") (pinfunction "1_6") (pintype "passive"))
      (node (ref "RN32") (pin "6") (pinfunction "1_6") (pintype "passive"))
      (node (ref "RN4") (pin "6") (pinfunction "1_6") (pintype "passive"))
      (node (ref "RN5") (pin "6") (pinfunction "1_6") (pintype "passive"))
      (node (ref "RN7") (pin "6") (pinfunction "1_6") (pintype "passive"))
      (node (ref "RN8") (pin "6") (pinfunction "1_6") (pintype "passive"))
      (node (ref "RN9") (pin "6") (pinfunction "1_6") (pintype "passive"))
      (node (ref "S2") (pin "1") (pinfunction "1_1") (pintype "passive"))
      (node (ref "S3") (pin "1") (pinfunction "1_1") (pintype "passive"))
      (node (ref "S3") (pin "2") (pinfunction "2_2") (pintype "passive"))
      (node (ref "S3") (pin "3") (pinfunction "3_3") (pintype "passive"))
      (node (ref "S3") (pin "4") (pinfunction "4_4") (pintype "passive"))
      (node (ref "S3") (pin "5") (pinfunction "5_5") (pintype "passive"))
      (node (ref "S3") (pin "6") (pinfunction "6_6") (pintype "passive"))
      (node (ref "S3") (pin "7") (pinfunction "7_7") (pintype "passive"))
      (node (ref "S4") (pin "1") (pinfunction "1_1") (pintype "passive"))
      (node (ref "S5") (pin "1") (pinfunction "1_1") (pintype "passive"))
      (node (ref "X2") (pin "5") (pinfunction "5_5") (pintype "passive"))
      (node (ref "X2") (pin "G2") (pinfunction "G2_G2") (pintype "passive"))
      (node (ref "XP1") (pin "AA11") (pinfunction "GND_AA11") (pintype "bidirectional"))
      (node (ref "XP1") (pin "AA16") (pinfunction "GND_AA16") (pintype "bidirectional"))
      (node (ref "XP1") (pin "AA8") (pinfunction "GND_AA8") (pintype "bidirectional"))
      (node (ref "XP1") (pin "AB3") (pinfunction "GND_AB3") (pintype "bidirectional"))
      (node (ref "XP1") (pin "BA11") (pinfunction "GND_BA11") (pintype "bidirectional"))
      (node (ref "XP1") (pin "BA16") (pinfunction "GND_BA16") (pintype "bidirectional"))
      (node (ref "XP1") (pin "BA8") (pinfunction "GND_BA8") (pintype "bidirectional"))
      (node (ref "XP1") (pin "BB3") (pinfunction "GND_BB3") (pintype "bidirectional"))
    )
    (net (code "95") (name "HK1") (class "Default")
      (node (ref "IC19") (pin "76") (pinfunction "IO189_76") (pintype "bidirectional"))
      (node (ref "RN3") (pin "8") (pinfunction "8_8") (pintype "passive"))
      (node (ref "S3") (pin "10") (pinfunction "10_10") (pintype "passive"))
    )
    (net (code "96") (name "HK2") (class "Default")
      (node (ref "IC19") (pin "77") (pinfunction "IO190_77") (pintype "bidirectional"))
      (node (ref "RN3") (pin "9") (pinfunction "9_9") (pintype "passive"))
      (node (ref "S3") (pin "11") (pinfunction "11_11") (pintype "passive"))
    )
    (net (code "97") (name "HK3") (class "Default")
      (node (ref "IC19") (pin "78") (pinfunction "IO192_78") (pintype "bidirectional"))
      (node (ref "RN3") (pin "10") (pinfunction "10_10") (pintype "passive"))
      (node (ref "S3") (pin "12") (pinfunction "12_12") (pintype "passive"))
    )
    (net (code "98") (name "HK4") (class "Default")
      (node (ref "IC19") (pin "79") (pinfunction "IO113_79") (pintype "bidirectional"))
      (node (ref "RN6") (pin "5") (pinfunction "5_5") (pintype "passive"))
      (node (ref "S3") (pin "13") (pinfunction "13_13") (pintype "passive"))
    )
    (net (code "99") (name "HK5") (class "Default")
      (node (ref "IC19") (pin "80") (pinfunction "IO115_80") (pintype "bidirectional"))
      (node (ref "RN6") (pin "6") (pinfunction "6_6") (pintype "passive"))
      (node (ref "S3") (pin "14") (pinfunction "14_14") (pintype "passive"))
    )
    (net (code "100") (name "HK6") (class "Default")
      (node (ref "IC19") (pin "87") (pinfunction "IO121_87") (pintype "bidirectional"))
      (node (ref "RN6") (pin "7") (pinfunction "7_7") (pintype "passive"))
      (node (ref "S3") (pin "15") (pinfunction "15_15") (pintype "passive"))
    )
    (net (code "101") (name "HK7") (class "Default")
      (node (ref "IC19") (pin "88") (pinfunction "IO123_88") (pintype "bidirectional"))
      (node (ref "RN6") (pin "8") (pinfunction "8_8") (pintype "passive"))
      (node (ref "S3") (pin "16") (pinfunction "16_16") (pintype "passive"))
    )
    (net (code "102") (name "HLT") (class "Default")
      (node (ref "DD6") (pin "3") (pinfunction "B0_3") (pintype "bidirectional"))
      (node (ref "IC1") (pin "47") (pinfunction "/HLT_47") (pintype "bidirectional"))
      (node (ref "IC19") (pin "84") (pinfunction "IO118_84") (pintype "bidirectional"))
      (node (ref "RN3") (pin "7") (pinfunction "7_7") (pintype "passive"))
      (node (ref "S3") (pin "8") (pinfunction "8_8") (pintype "passive"))
    )
    (net (code "103") (name "HLTM") (class "Default")
      (node (ref "D3") (pin "K") (pinfunction "C_K") (pintype "passive"))
      (node (ref "DD14") (pin "3") (pinfunction "B0_3") (pintype "bidirectional"))
      (node (ref "IC1") (pin "55") (pinfunction "/HLTM_55") (pintype "bidirectional"))
      (node (ref "IC19") (pin "43") (pinfunction "IO235_43") (pintype "bidirectional"))
      (node (ref "RN2") (pin "9") (pinfunction "9_9") (pintype "passive"))
    )
    (net (code "104") (name "HLT_KEY") (class "Default")
      (node (ref "DD6") (pin "13") (pinfunction "B3_13") (pintype "bidirectional"))
      (node (ref "S3") (pin "9") (pinfunction "9_9") (pintype "passive"))
    )
    (net (code "105") (name "HLT_P") (class "Default")
      (node (ref "IC17") (pin "4") (pinfunction "O_4") (pintype "output"))
      (node (ref "IC19") (pin "129") (pinfunction "IO112_129") (pintype "bidirectional"))
    )
    (net (code "106") (name "IAKO") (class "Default")
      (node (ref "DD14") (pin "10") (pinfunction "B2_10") (pintype "bidirectional"))
      (node (ref "IC19") (pin "37") (pinfunction "IO163_37") (pintype "bidirectional"))
      (node (ref "IC2") (pin "36") (pinfunction "IAKO_36") (pintype "bidirectional"))
    )
    (net (code "107") (name "IAK_VM") (class "Default")
      (node (ref "IC1") (pin "62") (pinfunction "/IAKO_62") (pintype "bidirectional"))
      (node (ref "IC2") (pin "33") (pinfunction "IAKI_33") (pintype "bidirectional"))
      (node (ref "RN2") (pin "3") (pinfunction "3_3") (pintype "passive"))
    )
    (net (code "108") (name "INIT") (class "Default")
      (node (ref "DD14") (pin "13") (pinfunction "B3_13") (pintype "bidirectional"))
      (node (ref "IC1") (pin "33") (pinfunction "/INIT_33") (pintype "bidirectional"))
      (node (ref "IC19") (pin "86") (pinfunction "IO120_86") (pintype "bidirectional"))
      (node (ref "IC2") (pin "34") (pinfunction "INIT_34") (pintype "bidirectional"))
      (node (ref "RN1") (pin "2") (pinfunction "2_2") (pintype "passive"))
    )
    (net (code "109") (name "INIT_P") (class "Default")
      (node (ref "IC17") (pin "6") (pinfunction "O_6") (pintype "output"))
      (node (ref "IC19") (pin "128") (pinfunction "IO110_128") (pintype "bidirectional"))
    )
    (net (code "110") (name "IRQ0") (class "Default")
      (node (ref "DD7") (pin "13") (pinfunction "B3_13") (pintype "bidirectional"))
      (node (ref "IC1") (pin "51") (pinfunction "/IRQ0_51") (pintype "bidirectional"))
      (node (ref "IC2") (pin "35") (pinfunction "VIRQ_35") (pintype "bidirectional"))
      (node (ref "RN3") (pin "3") (pinfunction "3_3") (pintype "passive"))
    )
    (net (code "111") (name "IRQ1") (class "Default")
      (node (ref "DD7") (pin "10") (pinfunction "B2_10") (pintype "bidirectional"))
      (node (ref "IC1") (pin "50") (pinfunction "/IRQ1_50") (pintype "bidirectional"))
      (node (ref "RN3") (pin "4") (pinfunction "4_4") (pintype "passive"))
    )
    (net (code "112") (name "IRQ2") (class "Default")
      (node (ref "DD7") (pin "6") (pinfunction "B1_6") (pintype "bidirectional"))
      (node (ref "IC1") (pin "49") (pinfunction "/IRQ2_49") (pintype "bidirectional"))
      (node (ref "RN3") (pin "5") (pinfunction "5_5") (pintype "passive"))
    )
    (net (code "113") (name "IRQ3") (class "Default")
      (node (ref "DD7") (pin "3") (pinfunction "B0_3") (pintype "bidirectional"))
      (node (ref "IC1") (pin "48") (pinfunction "/IRQ3_48") (pintype "bidirectional"))
      (node (ref "RN3") (pin "6") (pinfunction "6_6") (pintype "passive"))
    )
    (net (code "114") (name "L1") (class "Default")
      (node (ref "D11") (pin "K") (pinfunction "C_K") (pintype "passive"))
      (node (ref "IC19") (pin "121") (pinfunction "IO101_121") (pintype "bidirectional"))
    )
    (net (code "115") (name "L2") (class "Default")
      (node (ref "D12") (pin "K") (pinfunction "C_K") (pintype "passive"))
      (node (ref "IC19") (pin "120") (pinfunction "IO99_120") (pintype "bidirectional"))
    )
    (net (code "116") (name "L3") (class "Default")
      (node (ref "D13") (pin "K") (pinfunction "C_K") (pintype "passive"))
      (node (ref "IC19") (pin "119") (pinfunction "IO97_119") (pintype "bidirectional"))
    )
    (net (code "117") (name "LA") (class "Default")
      (node (ref "DD15") (pin "4") (pinfunction "I0_4") (pintype "bidirectional"))
      (node (ref "IC19") (pin "40") (pinfunction "IO238_40") (pintype "bidirectional"))
    )
    (net (code "118") (name "MCLK") (class "Default")
      (node (ref "IC19") (pin "184") (pinfunction "GCLK1_184") (pintype "input"))
      (node (ref "R16") (pin "1") (pinfunction "1_1") (pintype "passive"))
    )
    (net (code "119") (name "Net-(D1-A2)") (class "Default")
      (node (ref "C45") (pin "+") (pinfunction "+_+") (pintype "passive"))
      (node (ref "D1") (pin "2") (pinfunction "A2_2") (pintype "passive"))
      (node (ref "JP61") (pin "1") (pinfunction "1_1") (pintype "passive"))
    )
    (net (code "120") (name "Net-(D2-C)") (class "Default")
      (node (ref "D2") (pin "K") (pinfunction "C_K") (pintype "passive"))
      (node (ref "IC4") (pin "8") (pinfunction "O_8") (pintype "open_collector"))
    )
    (net (code "121") (name "Net-(D3-PadA)") (class "Default")
      (node (ref "D3") (pin "A") (pinfunction "A_A") (pintype "passive"))
      (node (ref "R65") (pin "1") (pinfunction "1_1") (pintype "passive"))
    )
    (net (code "122") (name "Net-(D5-C)") (class "Default")
      (node (ref "D5") (pin "K") (pinfunction "C_K") (pintype "passive"))
      (node (ref "IC4") (pin "6") (pinfunction "O_6") (pintype "open_collector"))
    )
    (net (code "123") (name "Net-(D8-PadA)") (class "Default")
      (node (ref "D8") (pin "A") (pinfunction "A_A") (pintype "passive"))
      (node (ref "R4") (pin "1") (pinfunction "1_1") (pintype "passive"))
    )
    (net (code "124") (name "Net-(D9-PadA)") (class "Default")
      (node (ref "D9") (pin "A") (pinfunction "A_A") (pintype "passive"))
      (node (ref "R5") (pin "2") (pinfunction "2_2") (pintype "passive"))
    )
    (net (code "125") (name "Net-(D11-PadA)") (class "Default")
      (node (ref "D11") (pin "A") (pinfunction "A_A") (pintype "passive"))
      (node (ref "R13") (pin "1") (pinfunction "1_1") (pintype "passive"))
    )
    (net (code "126") (name "Net-(D12-PadA)") (class "Default")
      (node (ref "D12") (pin "A") (pinfunction "A_A") (pintype "passive"))
      (node (ref "R17") (pin "1") (pinfunction "1_1") (pintype "passive"))
    )
    (net (code "127") (name "Net-(D13-PadA)") (class "Default")
      (node (ref "D13") (pin "A") (pinfunction "A_A") (pintype "passive"))
      (node (ref "R18") (pin "1") (pinfunction "1_1") (pintype "passive"))
    )
    (net (code "128") (name "Net-(IC1-{slash}CLK)") (class "Default")
      (node (ref "IC1") (pin "60") (pinfunction "/CLK_60") (pintype "bidirectional"))
      (node (ref "R14") (pin "1") (pinfunction "1_1") (pintype "passive"))
    )
    (net (code "129") (name "Net-(IC4A-I)") (class "Default")
      (node (ref "IC4") (pin "1") (pinfunction "I_1") (pintype "input"))
      (node (ref "Q1") (pin "1") (pinfunction "1_1") (pintype "passive"))
      (node (ref "R44") (pin "1") (pinfunction "1_1") (pintype "passive"))
    )
    (net (code "130") (name "Net-(IC4A-O)") (class "Default")
      (node (ref "C9") (pin "2") (pinfunction "2_2") (pintype "passive"))
      (node (ref "IC4") (pin "2") (pinfunction "O_2") (pintype "open_collector"))
      (node (ref "R44") (pin "2") (pinfunction "2_2") (pintype "passive"))
    )
    (net (code "131") (name "Net-(IC4B-I)") (class "Default")
      (node (ref "C9") (pin "1") (pinfunction "1_1") (pintype "passive"))
      (node (ref "IC4") (pin "3") (pinfunction "I_3") (pintype "input"))
      (node (ref "R45") (pin "1") (pinfunction "1_1") (pintype "passive"))
    )
    (net (code "132") (name "Net-(IC4B-O)") (class "Default")
      (node (ref "IC4") (pin "4") (pinfunction "O_4") (pintype "open_collector"))
      (node (ref "Q1") (pin "2") (pinfunction "2_2") (pintype "passive"))
      (node (ref "R15") (pin "2") (pinfunction "2_2") (pintype "passive"))
      (node (ref "R45") (pin "2") (pinfunction "2_2") (pintype "passive"))
    )
    (net (code "133") (name "Net-(IC4E-I)") (class "Default")
      (node (ref "C11") (pin "1") (pinfunction "1_1") (pintype "passive"))
      (node (ref "IC4") (pin "11") (pinfunction "I_11") (pintype "input"))
      (node (ref "R57") (pin "1") (pinfunction "1_1") (pintype "passive"))
    )
    (net (code "134") (name "Net-(IC4E-O)") (class "Default")
      (node (ref "IC4") (pin "10") (pinfunction "O_10") (pintype "open_collector"))
      (node (ref "Q2") (pin "2") (pinfunction "2_2") (pintype "passive"))
      (node (ref "R16") (pin "2") (pinfunction "2_2") (pintype "passive"))
      (node (ref "R57") (pin "2") (pinfunction "2_2") (pintype "passive"))
    )
    (net (code "135") (name "Net-(IC4F-I)") (class "Default")
      (node (ref "IC4") (pin "13") (pinfunction "I_13") (pintype "input"))
      (node (ref "Q2") (pin "1") (pinfunction "1_1") (pintype "passive"))
      (node (ref "R56") (pin "1") (pinfunction "1_1") (pintype "passive"))
    )
    (net (code "136") (name "Net-(IC4F-O)") (class "Default")
      (node (ref "C11") (pin "2") (pinfunction "2_2") (pintype "passive"))
      (node (ref "IC4") (pin "12") (pinfunction "O_12") (pintype "open_collector"))
      (node (ref "R56") (pin "2") (pinfunction "2_2") (pintype "passive"))
    )
    (net (code "137") (name "Net-(IC5A-VPP)") (class "Default")
      (node (ref "IC5") (pin "1") (pinfunction "VPP_1") (pintype "input"))
      (node (ref "R9") (pin "2") (pinfunction "2_2") (pintype "passive"))
    )
    (net (code "138") (name "Net-(IC6A-VPP)") (class "Default")
      (node (ref "IC6") (pin "1") (pinfunction "VPP_1") (pintype "input"))
      (node (ref "R10") (pin "2") (pinfunction "2_2") (pintype "passive"))
    )
    (net (code "139") (name "Net-(IC17A-I)") (class "Default")
      (node (ref "C18") (pin "+") (pinfunction "+_+") (pintype "passive"))
      (node (ref "D6") (pin "A") (pinfunction "A_A") (pintype "passive"))
      (node (ref "IC17") (pin "13") (pinfunction "I_13") (pintype "input"))
      (node (ref "R2") (pin "1") (pinfunction "1_1") (pintype "passive"))
      (node (ref "S4") (pin "2") (pinfunction "2_2") (pintype "passive"))
    )
    (net (code "140") (name "Net-(IC17C-I)") (class "Default")
      (node (ref "C19") (pin "+") (pinfunction "+_+") (pintype "passive"))
      (node (ref "D7") (pin "A") (pinfunction "A_A") (pintype "passive"))
      (node (ref "IC17") (pin "9") (pinfunction "I_9") (pintype "input"))
      (node (ref "R3") (pin "2") (pinfunction "2_2") (pintype "passive"))
    )
    (net (code "141") (name "Net-(IC17C-O)") (class "Default")
      (node (ref "IC17") (pin "1") (pinfunction "I_1") (pintype "input"))
      (node (ref "IC17") (pin "8") (pinfunction "O_8") (pintype "output"))
    )
    (net (code "142") (name "Net-(IC17E-I)") (class "Default")
      (node (ref "C22") (pin "1") (pinfunction "1_1") (pintype "passive"))
      (node (ref "D10") (pin "A") (pinfunction "A_A") (pintype "passive"))
      (node (ref "IC17") (pin "3") (pinfunction "I_3") (pintype "input"))
      (node (ref "R6") (pin "1") (pinfunction "1_1") (pintype "passive"))
      (node (ref "S5") (pin "2") (pinfunction "2_2") (pintype "passive"))
    )
    (net (code "143") (name "Net-(IC17F-I)") (class "Default")
      (node (ref "C2") (pin "1") (pinfunction "1_1") (pintype "passive"))
      (node (ref "D4") (pin "A") (pinfunction "A_A") (pintype "passive"))
      (node (ref "IC17") (pin "5") (pinfunction "I_5") (pintype "input"))
      (node (ref "R11") (pin "1") (pinfunction "1_1") (pintype "passive"))
      (node (ref "S2") (pin "2") (pinfunction "2_2") (pintype "passive"))
    )
    (net (code "144") (name "Net-(IC39A-C1+)") (class "Default")
      (node (ref "C38") (pin "2") (pinfunction "2_2") (pintype "passive"))
      (node (ref "IC39") (pin "1") (pinfunction "C1+_1") (pintype "bidirectional"))
    )
    (net (code "145") (name "Net-(IC39A-C1-)") (class "Default")
      (node (ref "C38") (pin "1") (pinfunction "1_1") (pintype "passive"))
      (node (ref "IC39") (pin "3") (pinfunction "C1-_3") (pintype "bidirectional"))
    )
    (net (code "146") (name "Net-(IC39A-C2+)") (class "Default")
      (node (ref "C39") (pin "2") (pinfunction "2_2") (pintype "passive"))
      (node (ref "IC39") (pin "4") (pinfunction "C2+_4") (pintype "bidirectional"))
    )
    (net (code "147") (name "Net-(IC39A-C2-)") (class "Default")
      (node (ref "C39") (pin "1") (pinfunction "1_1") (pintype "passive"))
      (node (ref "IC39") (pin "5") (pinfunction "C2-_5") (pintype "bidirectional"))
    )
    (net (code "148") (name "Net-(IC39A-R2IN)") (class "Default")
      (node (ref "IC39") (pin "8") (pinfunction "R2IN_8") (pintype "input"))
      (node (ref "X2") (pin "3") (pinfunction "3_3") (pintype "passive"))
    )
    (net (code "149") (name "Net-(IC39A-T2OUT)") (class "Default")
      (node (ref "IC39") (pin "7") (pinfunction "T2OUT_7") (pintype "output"))
      (node (ref "X2") (pin "2") (pinfunction "2_2") (pintype "passive"))
    )
    (net (code "150") (name "Net-(IC39A-V+)") (class "Default")
      (node (ref "C37") (pin "1") (pinfunction "1_1") (pintype "passive"))
      (node (ref "IC39") (pin "2") (pinfunction "V+_2") (pintype "bidirectional"))
    )
    (net (code "151") (name "Net-(IC39A-V-)") (class "Default")
      (node (ref "C36") (pin "1") (pinfunction "1_1") (pintype "passive"))
      (node (ref "IC39") (pin "6") (pinfunction "V-_6") (pintype "bidirectional"))
    )
    (net (code "152") (name "Net-(Q3-B)") (class "Default")
      (node (ref "Q3") (pin "2") (pinfunction "B_2") (pintype "passive"))
      (node (ref "R19") (pin "1") (pinfunction "1_1") (pintype "passive"))
      (node (ref "R20") (pin "2") (pinfunction "2_2") (pintype "passive"))
    )
    (net (code "153") (name "P_UART") (class "Default")
      (node (ref "IC19") (pin "130") (pinfunction "IO81_130") (pintype "bidirectional"))
      (node (ref "IC2") (pin "23") (pinfunction "ACL0_23") (pintype "bidirectional"))
    )
    (net (code "154") (name "RESET") (class "Default")
      (node (ref "IC17") (pin "11") (pinfunction "I_11") (pintype "input"))
      (node (ref "IC17") (pin "12") (pinfunction "O_12") (pintype "output"))
      (node (ref "IC19") (pin "182") (pinfunction "GCLR/_182") (pintype "input"))
    )
    (net (code "155") (name "ROM1") (class "Default")
      (node (ref "IC19") (pin "142") (pinfunction "IO19_142") (pintype "bidirectional"))
      (node (ref "IC5") (pin "2") (pinfunction "A12_2") (pintype "input"))
      (node (ref "IC6") (pin "2") (pinfunction "A12_2") (pintype "input"))
    )
    (net (code "156") (name "ROM2") (class "Default")
      (node (ref "IC19") (pin "141") (pinfunction "IO17_141") (pintype "bidirectional"))
      (node (ref "IC5") (pin "26") (pinfunction "A13_26") (pintype "input"))
      (node (ref "IC6") (pin "26") (pinfunction "A13_26") (pintype "input"))
    )
    (net (code "157") (name "ROM3") (class "Default")
      (node (ref "IC19") (pin "140") (pinfunction "IO96_140") (pintype "bidirectional"))
      (node (ref "IC5") (pin "27") (pinfunction "A14_27") (pintype "input"))
      (node (ref "IC6") (pin "27") (pinfunction "A14_27") (pintype "input"))
    )
    (net (code "158") (name "ROMCE0") (class "Default")
      (node (ref "IC19") (pin "144") (pinfunction "IO21_144") (pintype "bidirectional"))
      (node (ref "IC6") (pin "20") (pinfunction "~{CE}_20") (pintype "input"))
    )
    (net (code "159") (name "ROMCE1") (class "Default")
      (node (ref "IC19") (pin "145") (pinfunction "IO22_145") (pintype "bidirectional"))
      (node (ref "IC5") (pin "20") (pinfunction "~{CE}_20") (pintype "input"))
    )
    (net (code "160") (name "ROMOE") (class "Default")
      (node (ref "IC19") (pin "139") (pinfunction "IO94_139") (pintype "bidirectional"))
      (node (ref "IC5") (pin "22") (pinfunction "~{OE}_22") (pintype "input"))
      (node (ref "IC6") (pin "22") (pinfunction "~{OE}_22") (pintype "input"))
    )
    (net (code "161") (name "RPLY") (class "Default")
      (node (ref "IC19") (pin "81") (pinfunction "IO117_81") (pintype "bidirectional"))
      (node (ref "IC2") (pin "39") (pinfunction "RPLY_39") (pintype "bidirectional"))
      (node (ref "IC3") (pin "2") (pinfunction "RPLY_2") (pintype "bidirectional"))
      (node (ref "RN20") (pin "5") (pinfunction "5_5") (pintype "passive"))
    )
    (net (code "162") (name "RPLY_VM") (class "Default")
      (node (ref "DD16") (pin "10") (pinfunction "B2_10") (pintype "bidirectional"))
      (node (ref "IC1") (pin "5") (pinfunction "/RPLY_5") (pintype "bidirectional"))
      (node (ref "IC16") (pin "19") (pinfunction "RPLY_19") (pintype "bidirectional"))
      (node (ref "IC19") (pin "202") (pinfunction "IO203_202") (pintype "bidirectional"))
      (node (ref "RN19") (pin "3") (pinfunction "3_3") (pintype "passive"))
    )
    (net (code "163") (name "RX") (class "Default")
      (node (ref "IC19") (pin "108") (pinfunction "IO33_108") (pintype "bidirectional"))
      (node (ref "IC39") (pin "9") (pinfunction "R2OUT_9") (pintype "output"))
    )
    (net (code "164") (name "SA0") (class "Default")
      (node (ref "IC10") (pin "5") (pinfunction "A0_5") (pintype "input"))
      (node (ref "IC19") (pin "164") (pinfunction "IO13_164") (pintype "bidirectional"))
      (node (ref "IC5") (pin "10") (pinfunction "A0_10") (pintype "input"))
      (node (ref "IC6") (pin "10") (pinfunction "A0_10") (pintype "input"))
      (node (ref "IC7") (pin "5") (pinfunction "A0_5") (pintype "input"))
      (node (ref "IC8") (pin "5") (pinfunction "A0_5") (pintype "input"))
      (node (ref "IC9") (pin "5") (pinfunction "A0_5") (pintype "input"))
    )
    (net (code "165") (name "SA1") (class "Default")
      (node (ref "IC10") (pin "4") (pinfunction "A1_4") (pintype "input"))
      (node (ref "IC19") (pin "166") (pinfunction "IO14_166") (pintype "bidirectional"))
      (node (ref "IC5") (pin "9") (pinfunction "A1_9") (pintype "input"))
      (node (ref "IC6") (pin "9") (pinfunction "A1_9") (pintype "input"))
      (node (ref "IC7") (pin "4") (pinfunction "A1_4") (pintype "input"))
      (node (ref "IC8") (pin "4") (pinfunction "A1_4") (pintype "input"))
      (node (ref "IC9") (pin "4") (pinfunction "A1_4") (pintype "input"))
    )
    (net (code "166") (name "SA2") (class "Default")
      (node (ref "IC10") (pin "3") (pinfunction "A2_3") (pintype "input"))
      (node (ref "IC19") (pin "167") (pinfunction "IO16_167") (pintype "bidirectional"))
      (node (ref "IC5") (pin "8") (pinfunction "A2_8") (pintype "input"))
      (node (ref "IC6") (pin "8") (pinfunction "A2_8") (pintype "input"))
      (node (ref "IC7") (pin "3") (pinfunction "A2_3") (pintype "input"))
      (node (ref "IC8") (pin "3") (pinfunction "A2_3") (pintype "input"))
      (node (ref "IC9") (pin "3") (pinfunction "A2_3") (pintype "input"))
    )
    (net (code "167") (name "SA3") (class "Default")
      (node (ref "IC10") (pin "2") (pinfunction "A3_2") (pintype "input"))
      (node (ref "IC19") (pin "168") (pinfunction "IO65_168") (pintype "bidirectional"))
      (node (ref "IC5") (pin "7") (pinfunction "A3_7") (pintype "input"))
      (node (ref "IC6") (pin "7") (pinfunction "A3_7") (pintype "input"))
      (node (ref "IC7") (pin "2") (pinfunction "A3_2") (pintype "input"))
      (node (ref "IC8") (pin "2") (pinfunction "A3_2") (pintype "input"))
      (node (ref "IC9") (pin "2") (pinfunction "A3_2") (pintype "input"))
    )
    (net (code "168") (name "SA4") (class "Default")
      (node (ref "IC10") (pin "1") (pinfunction "A4_1") (pintype "input"))
      (node (ref "IC19") (pin "169") (pinfunction "IO67_169") (pintype "bidirectional"))
      (node (ref "IC5") (pin "6") (pinfunction "A4_6") (pintype "input"))
      (node (ref "IC6") (pin "6") (pinfunction "A4_6") (pintype "input"))
      (node (ref "IC7") (pin "1") (pinfunction "A4_1") (pintype "input"))
      (node (ref "IC8") (pin "1") (pinfunction "A4_1") (pintype "input"))
      (node (ref "IC9") (pin "1") (pinfunction "A4_1") (pintype "input"))
    )
    (net (code "169") (name "SA5") (class "Default")
      (node (ref "IC10") (pin "44") (pinfunction "A5_44") (pintype "input"))
      (node (ref "IC19") (pin "170") (pinfunction "IO69_170") (pintype "bidirectional"))
      (node (ref "IC5") (pin "5") (pinfunction "A5_5") (pintype "input"))
      (node (ref "IC6") (pin "5") (pinfunction "A5_5") (pintype "input"))
      (node (ref "IC7") (pin "44") (pinfunction "A5_44") (pintype "input"))
      (node (ref "IC8") (pin "44") (pinfunction "A5_44") (pintype "input"))
      (node (ref "IC9") (pin "44") (pinfunction "A5_44") (pintype "input"))
    )
    (net (code "170") (name "SA6") (class "Default")
      (node (ref "IC10") (pin "43") (pinfunction "A6_43") (pintype "input"))
      (node (ref "IC19") (pin "171") (pinfunction "IO70_171") (pintype "bidirectional"))
      (node (ref "IC5") (pin "4") (pinfunction "A6_4") (pintype "input"))
      (node (ref "IC6") (pin "4") (pinfunction "A6_4") (pintype "input"))
      (node (ref "IC7") (pin "43") (pinfunction "A6_43") (pintype "input"))
      (node (ref "IC8") (pin "43") (pinfunction "A6_43") (pintype "input"))
      (node (ref "IC9") (pin "43") (pinfunction "A6_43") (pintype "input"))
    )
    (net (code "171") (name "SA7") (class "Default")
      (node (ref "IC10") (pin "42") (pinfunction "A7_42") (pintype "input"))
      (node (ref "IC19") (pin "194") (pinfunction "IO134_194") (pintype "bidirectional"))
      (node (ref "IC5") (pin "3") (pinfunction "A7_3") (pintype "input"))
      (node (ref "IC6") (pin "3") (pinfunction "A7_3") (pintype "input"))
      (node (ref "IC7") (pin "42") (pinfunction "A7_42") (pintype "input"))
      (node (ref "IC8") (pin "42") (pinfunction "A7_42") (pintype "input"))
      (node (ref "IC9") (pin "42") (pinfunction "A7_42") (pintype "input"))
    )
    (net (code "172") (name "SA8") (class "Default")
      (node (ref "IC10") (pin "39") (pinfunction "A8_39") (pintype "input"))
      (node (ref "IC19") (pin "193") (pinfunction "IO136_193") (pintype "bidirectional"))
      (node (ref "IC5") (pin "25") (pinfunction "A8_25") (pintype "input"))
      (node (ref "IC6") (pin "25") (pinfunction "A8_25") (pintype "input"))
      (node (ref "IC7") (pin "39") (pinfunction "A8_39") (pintype "input"))
      (node (ref "IC8") (pin "39") (pinfunction "A8_39") (pintype "input"))
      (node (ref "IC9") (pin "39") (pinfunction "A8_39") (pintype "input"))
    )
    (net (code "173") (name "SA9") (class "Default")
      (node (ref "IC10") (pin "28") (pinfunction "A9_28") (pintype "input"))
      (node (ref "IC19") (pin "159") (pinfunction "IO5_159") (pintype "bidirectional"))
      (node (ref "IC5") (pin "24") (pinfunction "A9_24") (pintype "input"))
      (node (ref "IC6") (pin "24") (pinfunction "A9_24") (pintype "input"))
      (node (ref "IC7") (pin "28") (pinfunction "A9_28") (pintype "input"))
      (node (ref "IC8") (pin "28") (pinfunction "A9_28") (pintype "input"))
      (node (ref "IC9") (pin "28") (pinfunction "A9_28") (pintype "input"))
    )
    (net (code "174") (name "SA10") (class "Default")
      (node (ref "IC10") (pin "27") (pinfunction "A10_27") (pintype "input"))
      (node (ref "IC19") (pin "150") (pinfunction "IO30_150") (pintype "bidirectional"))
      (node (ref "IC5") (pin "21") (pinfunction "A10_21") (pintype "input"))
      (node (ref "IC6") (pin "21") (pinfunction "A10_21") (pintype "input"))
      (node (ref "IC7") (pin "27") (pinfunction "A10_27") (pintype "input"))
      (node (ref "IC8") (pin "27") (pinfunction "A10_27") (pintype "input"))
      (node (ref "IC9") (pin "27") (pinfunction "A10_27") (pintype "input"))
    )
    (net (code "175") (name "SA11") (class "Default")
      (node (ref "IC10") (pin "26") (pinfunction "A11_26") (pintype "input"))
      (node (ref "IC19") (pin "149") (pinfunction "IO29_149") (pintype "bidirectional"))
      (node (ref "IC5") (pin "23") (pinfunction "A11_23") (pintype "input"))
      (node (ref "IC6") (pin "23") (pinfunction "A11_23") (pintype "input"))
      (node (ref "IC7") (pin "26") (pinfunction "A11_26") (pintype "input"))
      (node (ref "IC8") (pin "26") (pinfunction "A11_26") (pintype "input"))
      (node (ref "IC9") (pin "26") (pinfunction "A11_26") (pintype "input"))
    )
    (net (code "176") (name "SA12") (class "Default")
      (node (ref "IC10") (pin "25") (pinfunction "A12_25") (pintype "input"))
      (node (ref "IC19") (pin "148") (pinfunction "IO27_148") (pintype "bidirectional"))
      (node (ref "IC7") (pin "25") (pinfunction "A12_25") (pintype "input"))
      (node (ref "IC8") (pin "25") (pinfunction "A12_25") (pintype "input"))
      (node (ref "IC9") (pin "25") (pinfunction "A12_25") (pintype "input"))
    )
    (net (code "177") (name "SA13") (class "Default")
      (node (ref "IC10") (pin "24") (pinfunction "A13_24") (pintype "input"))
      (node (ref "IC19") (pin "147") (pinfunction "IO25_147") (pintype "bidirectional"))
      (node (ref "IC7") (pin "24") (pinfunction "A13_24") (pintype "input"))
      (node (ref "IC8") (pin "24") (pinfunction "A13_24") (pintype "input"))
      (node (ref "IC9") (pin "24") (pinfunction "A13_24") (pintype "input"))
    )
    (net (code "178") (name "SA14") (class "Default")
      (node (ref "IC10") (pin "23") (pinfunction "A14_23") (pintype "input"))
      (node (ref "IC19") (pin "146") (pinfunction "IO24_146") (pintype "bidirectional"))
      (node (ref "IC7") (pin "23") (pinfunction "A14_23") (pintype "input"))
      (node (ref "IC8") (pin "23") (pinfunction "A14_23") (pintype "input"))
      (node (ref "IC9") (pin "23") (pinfunction "A14_23") (pintype "input"))
    )
    (net (code "179") (name "SA15") (class "Default")
      (node (ref "IC10") (pin "22") (pinfunction "A15_22") (pintype "input"))
      (node (ref "IC19") (pin "192") (pinfunction "IO137_192") (pintype "bidirectional"))
      (node (ref "IC7") (pin "22") (pinfunction "A15_22") (pintype "input"))
      (node (ref "IC8") (pin "22") (pinfunction "A15_22") (pintype "input"))
      (node (ref "IC9") (pin "22") (pinfunction "A15_22") (pintype "input"))
    )
    (net (code "180") (name "SA16") (class "Default")
      (node (ref "IC10") (pin "21") (pinfunction "A16_21") (pintype "input"))
      (node (ref "IC19") (pin "188") (pinfunction "IO142_188") (pintype "bidirectional"))
      (node (ref "IC7") (pin "21") (pinfunction "A16_21") (pintype "input"))
      (node (ref "IC8") (pin "21") (pinfunction "A16_21") (pintype "input"))
      (node (ref "IC9") (pin "21") (pinfunction "A16_21") (pintype "input"))
    )
    (net (code "181") (name "SA17") (class "Default")
      (node (ref "IC10") (pin "20") (pinfunction "A17_20") (pintype "input"))
      (node (ref "IC19") (pin "187") (pinfunction "IO144_187") (pintype "bidirectional"))
      (node (ref "IC7") (pin "20") (pinfunction "A17_20") (pintype "input"))
      (node (ref "IC8") (pin "20") (pinfunction "A17_20") (pintype "input"))
      (node (ref "IC9") (pin "20") (pinfunction "A17_20") (pintype "input"))
    )
    (net (code "182") (name "SA18") (class "Default")
      (node (ref "IC10") (pin "19") (pinfunction "A18_19") (pintype "input"))
      (node (ref "IC19") (pin "178") (pinfunction "IO80_178") (pintype "bidirectional"))
      (node (ref "IC7") (pin "19") (pinfunction "A18_19") (pintype "input"))
      (node (ref "IC8") (pin "19") (pinfunction "A18_19") (pintype "input"))
      (node (ref "IC9") (pin "19") (pinfunction "A18_19") (pintype "input"))
    )
    (net (code "183") (name "SA19") (class "Default")
      (node (ref "IC10") (pin "18") (pinfunction "A19_18") (pintype "input"))
      (node (ref "IC19") (pin "177") (pinfunction "IO78_177") (pintype "bidirectional"))
      (node (ref "IC7") (pin "18") (pinfunction "A19_18") (pintype "input"))
      (node (ref "IC8") (pin "18") (pinfunction "A19_18") (pintype "input"))
      (node (ref "IC9") (pin "18") (pinfunction "A19_18") (pintype "input"))
    )
    (net (code "184") (name "SACK") (class "Default")
      (node (ref "DD15") (pin "15") (pinfunction "CO_15") (pintype "bidirectional"))
      (node (ref "DD16") (pin "15") (pinfunction "CO_15") (pintype "bidirectional"))
      (node (ref "DD5") (pin "10") (pinfunction "B2_10") (pintype "bidirectional"))
      (node (ref "IC1") (pin "7") (pinfunction "/SACK_7") (pintype "bidirectional"))
      (node (ref "IC16") (pin "21") (pinfunction "/SACK_21") (pintype "bidirectional"))
      (node (ref "IC19") (pin "36") (pinfunction "IO165_36") (pintype "bidirectional"))
      (node (ref "RN19") (pin "5") (pinfunction "5_5") (pintype "passive"))
    )
    (net (code "185") (name "SACK_B") (class "Default")
      (node (ref "DD15") (pin "1") (pinfunction "CI_1") (pintype "bidirectional"))
      (node (ref "DD16") (pin "1") (pinfunction "CI_1") (pintype "bidirectional"))
      (node (ref "IC19") (pin "38") (pinfunction "IO161_38") (pintype "bidirectional"))
    )
    (net (code "186") (name "SCE0") (class "Default")
      (node (ref "IC19") (pin "160") (pinfunction "IO6_160") (pintype "bidirectional"))
      (node (ref "IC7") (pin "40") (pinfunction "CE2_40") (pintype "bidirectional"))
    )
    (net (code "187") (name "SCE1") (class "Default")
      (node (ref "IC19") (pin "161") (pinfunction "IO8_161") (pintype "bidirectional"))
      (node (ref "IC8") (pin "40") (pinfunction "CE2_40") (pintype "bidirectional"))
    )
    (net (code "188") (name "SCE2") (class "Default")
      (node (ref "IC19") (pin "162") (pinfunction "IO9_162") (pintype "bidirectional"))
      (node (ref "IC9") (pin "40") (pinfunction "CE2_40") (pintype "bidirectional"))
    )
    (net (code "189") (name "SCE3") (class "Default")
      (node (ref "IC10") (pin "40") (pinfunction "CE2_40") (pintype "bidirectional"))
      (node (ref "IC19") (pin "163") (pinfunction "IO11_163") (pintype "bidirectional"))
    )
    (net (code "190") (name "SEL") (class "Default")
      (node (ref "DD16") (pin "5") (pinfunction "O1_5") (pintype "bidirectional"))
      (node (ref "DD16") (pin "7") (pinfunction "I1_7") (pintype "bidirectional"))
      (node (ref "IC1") (pin "35") (pinfunction "/SEL_35") (pintype "bidirectional"))
      (node (ref "IC19") (pin "204") (pinfunction "IO200_204") (pintype "bidirectional"))
      (node (ref "RN1") (pin "4") (pinfunction "4_4") (pintype "passive"))
    )
    (net (code "191") (name "SOE0") (class "Default")
      (node (ref "IC19") (pin "153") (pinfunction "IO1_153") (pintype "bidirectional"))
      (node (ref "IC7") (pin "41") (pinfunction "OE_41") (pintype "input"))
      (node (ref "IC8") (pin "41") (pinfunction "OE_41") (pintype "input"))
    )
    (net (code "192") (name "SOE1") (class "Default")
      (node (ref "IC10") (pin "41") (pinfunction "OE_41") (pintype "input"))
      (node (ref "IC19") (pin "154") (pinfunction "IO3_154") (pintype "bidirectional"))
      (node (ref "IC9") (pin "41") (pinfunction "OE_41") (pintype "input"))
    )
    (net (code "193") (name "SRAM_CE2") (class "Default")
      (node (ref "IC10") (pin "6") (pinfunction "CE_6") (pintype "input"))
      (node (ref "IC7") (pin "6") (pinfunction "CE_6") (pintype "input"))
      (node (ref "IC8") (pin "6") (pinfunction "CE_6") (pintype "input"))
      (node (ref "IC9") (pin "6") (pinfunction "CE_6") (pintype "input"))
      (node (ref "Q3") (pin "3") (pinfunction "C_3") (pintype "passive"))
      (node (ref "R12") (pin "2") (pinfunction "2_2") (pintype "passive"))
    )
    (net (code "194") (name "SRAM_CE_G") (class "Default")
      (node (ref "IC19") (pin "175") (pinfunction "IO75_175") (pintype "bidirectional"))
      (node (ref "R19") (pin "2") (pinfunction "2_2") (pintype "passive"))
    )
    (net (code "195") (name "SSPARE_SEL") (class "Default")
      (node (ref "DD16") (pin "6") (pinfunction "B1_6") (pintype "bidirectional"))
      (node (ref "RN15") (pin "4") (pinfunction "1_4") (pintype "passive"))
      (node (ref "RN31") (pin "4") (pinfunction "1_4") (pintype "passive"))
      (node (ref "XP1") (pin "AA7") (pinfunction "P$7_AA7") (pintype "bidirectional"))
    )
    (net (code "196") (name "SSYNC") (class "Default")
      (node (ref "IC1") (pin "4") (pinfunction "/SSYNC_4") (pintype "bidirectional"))
      (node (ref "IC16") (pin "23") (pinfunction "/SSYNC_23") (pintype "bidirectional"))
      (node (ref "IC19") (pin "201") (pinfunction "IO205_201") (pintype "bidirectional"))
      (node (ref "RN19") (pin "2") (pinfunction "2_2") (pintype "passive"))
    )
    (net (code "197") (name "SYNC") (class "Default")
      (node (ref "IC1") (pin "3") (pinfunction "/SYNC_3") (pintype "bidirectional"))
      (node (ref "IC16") (pin "22") (pinfunction "/SYNC_22") (pintype "bidirectional"))
      (node (ref "IC19") (pin "199") (pinfunction "IO206_199") (pintype "bidirectional"))
      (node (ref "IC3") (pin "3") (pinfunction "SYNC_3") (pintype "bidirectional"))
      (node (ref "RN6") (pin "4") (pinfunction "4_4") (pintype "passive"))
    )
    (net (code "198") (name "TA") (class "Default")
      (node (ref "IC1") (pin "36") (pinfunction "/TA_36") (pintype "bidirectional"))
      (node (ref "IC19") (pin "26") (pinfunction "IO147_26") (pintype "bidirectional"))
      (node (ref "RN1") (pin "5") (pinfunction "5_5") (pintype "passive"))
    )
    (net (code "199") (name "TCK") (class "Default")
      (node (ref "IC19") (pin "30") (pinfunction "TCK-IO173_30") (pintype "bidirectional"))
      (node (ref "JP3") (pin "1") (pinfunction "1_1") (pintype "passive"))
      (node (ref "R1") (pin "2") (pinfunction "2_2") (pintype "passive"))
    )
    (net (code "200") (name "TDI") (class "Default")
      (node (ref "IC19") (pin "176") (pinfunction "IO77-TDI_176") (pintype "bidirectional"))
      (node (ref "JP3") (pin "9") (pinfunction "9_9") (pintype "passive"))
      (node (ref "R7") (pin "2") (pinfunction "2_2") (pintype "passive"))
    )
    (net (code "201") (name "TDO") (class "Default")
      (node (ref "IC19") (pin "189") (pinfunction "TDO-IO141_189") (pintype "bidirectional"))
      (node (ref "JP3") (pin "3") (pinfunction "3_3") (pintype "passive"))
    )
    (net (code "202") (name "TMS") (class "Default")
      (node (ref "IC19") (pin "127") (pinfunction "IO109-TMS_127") (pintype "bidirectional"))
      (node (ref "JP3") (pin "5") (pinfunction "5_5") (pintype "passive"))
      (node (ref "R8") (pin "2") (pinfunction "2_2") (pintype "passive"))
    )
    (net (code "203") (name "TX") (class "Default")
      (node (ref "IC19") (pin "110") (pinfunction "IO37_110") (pintype "bidirectional"))
      (node (ref "IC39") (pin "10") (pinfunction "T2IN_10") (pintype "input"))
    )
    (net (code "204") (name "UMAP_VM") (class "Default")
      (node (ref "IC1") (pin "37") (pinfunction "/UMAP_37") (pintype "bidirectional"))
      (node (ref "RN1") (pin "6") (pinfunction "6_6") (pintype "passive"))
    )
    (net (code "205") (name "WE0") (class "Default")
      (node (ref "IC19") (pin "173") (pinfunction "IO73_173") (pintype "bidirectional"))
      (node (ref "IC7") (pin "17") (pinfunction "WE_17") (pintype "input"))
      (node (ref "IC8") (pin "17") (pinfunction "WE_17") (pintype "input"))
    )
    (net (code "206") (name "WE1") (class "Default")
      (node (ref "IC10") (pin "17") (pinfunction "WE_17") (pintype "input"))
      (node (ref "IC19") (pin "172") (pinfunction "IO72_172") (pintype "bidirectional"))
      (node (ref "IC9") (pin "17") (pinfunction "WE_17") (pintype "input"))
    )
    (net (code "207") (name "WO") (class "Default")
      (node (ref "IC1") (pin "59") (pinfunction "/WO_59") (pintype "bidirectional"))
      (node (ref "IC19") (pin "124") (pinfunction "IO105_124") (pintype "bidirectional"))
      (node (ref "JP1") (pin "2") (pinfunction "2_2") (pintype "passive"))
      (node (ref "RN2") (pin "5") (pinfunction "5_5") (pintype "passive"))
    )
    (net (code "208") (name "WTBT") (class "Default")
      (node (ref "DD15") (pin "12") (pinfunction "I3_12") (pintype "bidirectional"))
      (node (ref "DD15") (pin "14") (pinfunction "O3_14") (pintype "bidirectional"))
      (node (ref "IC19") (pin "42") (pinfunction "IO237_42") (pintype "bidirectional"))
      (node (ref "RN20") (pin "6") (pinfunction "6_6") (pintype "passive"))
    )
    (net (code "209") (name "WTBT_VM") (class "Default")
      (node (ref "IC1") (pin "63") (pinfunction "/WTBT_63") (pintype "bidirectional"))
      (node (ref "IC19") (pin "203") (pinfunction "IO201_203") (pintype "bidirectional"))
      (node (ref "RN2") (pin "2") (pinfunction "2_2") (pintype "passive"))
    )
    (net (code "210") (name "unconnected-(DD5-B0-Pad3)") (class "Default")
      (node (ref "DD5") (pin "3") (pinfunction "B0_3") (pintype "bidirectional"))
    )
    (net (code "211") (name "unconnected-(DD5-I0-Pad4)") (class "Default")
      (node (ref "DD5") (pin "4") (pinfunction "I0_4") (pintype "bidirectional"))
    )
    (net (code "212") (name "unconnected-(DD5-O0-Pad2)") (class "Default")
      (node (ref "DD5") (pin "2") (pinfunction "O0_2") (pintype "bidirectional"))
    )
    (net (code "213") (name "unconnected-(DD5-O1-Pad5)") (class "Default")
      (node (ref "DD5") (pin "5") (pinfunction "O1_5") (pintype "bidirectional"))
    )
    (net (code "214") (name "unconnected-(DD5-O2-Pad11)") (class "Default")
      (node (ref "DD5") (pin "11") (pinfunction "O2_11") (pintype "bidirectional"))
    )
    (net (code "215") (name "unconnected-(DD5-O3-Pad14)") (class "Default")
      (node (ref "DD5") (pin "14") (pinfunction "O3_14") (pintype "bidirectional"))
    )
    (net (code "216") (name "unconnected-(DD6-O0-Pad2)") (class "Default")
      (node (ref "DD6") (pin "2") (pinfunction "O0_2") (pintype "bidirectional"))
    )
    (net (code "217") (name "unconnected-(DD6-O1-Pad5)") (class "Default")
      (node (ref "DD6") (pin "5") (pinfunction "O1_5") (pintype "bidirectional"))
    )
    (net (code "218") (name "unconnected-(DD6-O2-Pad11)") (class "Default")
      (node (ref "DD6") (pin "11") (pinfunction "O2_11") (pintype "bidirectional"))
    )
    (net (code "219") (name "unconnected-(DD6-O3-Pad14)") (class "Default")
      (node (ref "DD6") (pin "14") (pinfunction "O3_14") (pintype "bidirectional"))
    )
    (net (code "220") (name "unconnected-(DD7-O0-Pad2)") (class "Default")
      (node (ref "DD7") (pin "2") (pinfunction "O0_2") (pintype "bidirectional"))
    )
    (net (code "221") (name "unconnected-(DD7-O1-Pad5)") (class "Default")
      (node (ref "DD7") (pin "5") (pinfunction "O1_5") (pintype "bidirectional"))
    )
    (net (code "222") (name "unconnected-(DD7-O2-Pad11)") (class "Default")
      (node (ref "DD7") (pin "11") (pinfunction "O2_11") (pintype "bidirectional"))
    )
    (net (code "223") (name "unconnected-(DD7-O3-Pad14)") (class "Default")
      (node (ref "DD7") (pin "14") (pinfunction "O3_14") (pintype "bidirectional"))
    )
    (net (code "224") (name "unconnected-(DD9-B2-Pad10)") (class "Default")
      (node (ref "DD9") (pin "10") (pinfunction "B2_10") (pintype "bidirectional"))
    )
    (net (code "225") (name "unconnected-(DD9-B3-Pad13)") (class "Default")
      (node (ref "DD9") (pin "13") (pinfunction "B3_13") (pintype "bidirectional"))
    )
    (net (code "226") (name "unconnected-(DD9-I2-Pad9)") (class "Default")
      (node (ref "DD9") (pin "9") (pinfunction "I2_9") (pintype "bidirectional"))
    )
    (net (code "227") (name "unconnected-(DD9-I3-Pad12)") (class "Default")
      (node (ref "DD9") (pin "12") (pinfunction "I3_12") (pintype "bidirectional"))
    )
    (net (code "228") (name "unconnected-(DD9-O2-Pad11)") (class "Default")
      (node (ref "DD9") (pin "11") (pinfunction "O2_11") (pintype "bidirectional"))
    )
    (net (code "229") (name "unconnected-(DD9-O3-Pad14)") (class "Default")
      (node (ref "DD9") (pin "14") (pinfunction "O3_14") (pintype "bidirectional"))
    )
    (net (code "230") (name "unconnected-(DD14-I0-Pad4)") (class "Default")
      (node (ref "DD14") (pin "4") (pinfunction "I0_4") (pintype "bidirectional"))
    )
    (net (code "231") (name "unconnected-(DD14-I1-Pad7)") (class "Default")
      (node (ref "DD14") (pin "7") (pinfunction "I1_7") (pintype "bidirectional"))
    )
    (net (code "232") (name "unconnected-(DD14-I2-Pad9)") (class "Default")
      (node (ref "DD14") (pin "9") (pinfunction "I2_9") (pintype "bidirectional"))
    )
    (net (code "233") (name "unconnected-(DD14-I3-Pad12)") (class "Default")
      (node (ref "DD14") (pin "12") (pinfunction "I3_12") (pintype "bidirectional"))
    )
    (net (code "234") (name "unconnected-(DD16-B3-Pad13)") (class "Default")
      (node (ref "DD16") (pin "13") (pinfunction "B3_13") (pintype "bidirectional"))
    )
    (net (code "235") (name "unconnected-(DD16-I3-Pad12)") (class "Default")
      (node (ref "DD16") (pin "12") (pinfunction "I3_12") (pintype "bidirectional"))
    )
    (net (code "236") (name "unconnected-(DD16-O3-Pad14)") (class "Default")
      (node (ref "DD16") (pin "14") (pinfunction "O3_14") (pintype "bidirectional"))
    )
    (net (code "237") (name "unconnected-(IC2-RR-Pad31)") (class "Default")
      (node (ref "IC2") (pin "31") (pinfunction "RR_31") (pintype "bidirectional"))
    )
    (net (code "238") (name "unconnected-(IC2-ST-Pad8)") (class "Default")
      (node (ref "IC2") (pin "8") (pinfunction "ST_8") (pintype "bidirectional"))
    )
    (net (code "239") (name "unconnected-(IC19AS-IO40-Pad112)") (class "Default")
      (node (ref "IC19") (pin "112") (pinfunction "IO40_112") (pintype "bidirectional"))
    )
    (net (code "240") (name "unconnected-(IC19AS-IO43-Pad114)") (class "Default")
      (node (ref "IC19") (pin "114") (pinfunction "IO43_114") (pintype "bidirectional"))
    )
    (net (code "241") (name "unconnected-(IC19AS-IO45-Pad115)") (class "Default")
      (node (ref "IC19") (pin "115") (pinfunction "IO45_115") (pintype "bidirectional"))
    )
    (net (code "242") (name "unconnected-(IC19AS-IO48-Pad118)") (class "Default")
      (node (ref "IC19") (pin "118") (pinfunction "IO48_118") (pintype "bidirectional"))
    )
    (net (code "243") (name "unconnected-(IC19AS-IO49-Pad92)") (class "Default")
      (node (ref "IC19") (pin "92") (pinfunction "IO49_92") (pintype "bidirectional"))
    )
    (net (code "244") (name "unconnected-(IC19AS-IO51-Pad93)") (class "Default")
      (node (ref "IC19") (pin "93") (pinfunction "IO51_93") (pintype "bidirectional"))
    )
    (net (code "245") (name "unconnected-(IC19AS-IO53-Pad95)") (class "Default")
      (node (ref "IC19") (pin "95") (pinfunction "IO53_95") (pintype "bidirectional"))
    )
    (net (code "246") (name "unconnected-(IC19AS-IO54-Pad96)") (class "Default")
      (node (ref "IC19") (pin "96") (pinfunction "IO54_96") (pintype "bidirectional"))
    )
    (net (code "247") (name "unconnected-(IC19AS-IO56-Pad97)") (class "Default")
      (node (ref "IC19") (pin "97") (pinfunction "IO56_97") (pintype "bidirectional"))
    )
    (net (code "248") (name "unconnected-(IC19AS-IO57-Pad98)") (class "Default")
      (node (ref "IC19") (pin "98") (pinfunction "IO57_98") (pintype "bidirectional"))
    )
    (net (code "249") (name "unconnected-(IC19AS-IO59-Pad99)") (class "Default")
      (node (ref "IC19") (pin "99") (pinfunction "IO59_99") (pintype "bidirectional"))
    )
    (net (code "250") (name "unconnected-(IC19AS-IO61-Pad100)") (class "Default")
      (node (ref "IC19") (pin "100") (pinfunction "IO61_100") (pintype "bidirectional"))
    )
    (net (code "251") (name "unconnected-(IC19AS-IO62-Pad101)") (class "Default")
      (node (ref "IC19") (pin "101") (pinfunction "IO62_101") (pintype "bidirectional"))
    )
    (net (code "252") (name "unconnected-(IC19AS-IO64-Pad102)") (class "Default")
      (node (ref "IC19") (pin "102") (pinfunction "IO64_102") (pintype "bidirectional"))
    )
    (net (code "253") (name "unconnected-(IC19AS-IO125-Pad89)") (class "Default")
      (node (ref "IC19") (pin "89") (pinfunction "IO125_89") (pintype "bidirectional"))
    )
    (net (code "254") (name "unconnected-(IC19AS-IO126-Pad90)") (class "Default")
      (node (ref "IC19") (pin "90") (pinfunction "IO126_90") (pintype "bidirectional"))
    )
    (net (code "255") (name "unconnected-(IC19AS-IO128-Pad91)") (class "Default")
      (node (ref "IC19") (pin "91") (pinfunction "IO128_91") (pintype "bidirectional"))
    )
    (net (code "256") (name "unconnected-(IC19AS-IO139-Pad190)") (class "Default")
      (node (ref "IC19") (pin "190") (pinfunction "IO139_190") (pintype "bidirectional"))
    )
    (net (code "257") (name "unconnected-(IC19AS-IO145-Pad27)") (class "Default")
      (node (ref "IC19") (pin "27") (pinfunction "IO145_27") (pintype "bidirectional"))
    )
    (net (code "258") (name "unconnected-(IC19AS-IO149-Pad25)") (class "Default")
      (node (ref "IC19") (pin "25") (pinfunction "IO149_25") (pintype "bidirectional"))
    )
    (net (code "259") (name "unconnected-(IC19AS-IO166-Pad35)") (class "Default")
      (node (ref "IC19") (pin "35") (pinfunction "IO166_35") (pintype "bidirectional"))
    )
    (net (code "260") (name "unconnected-(IC19AS-IO171-Pad31)") (class "Default")
      (node (ref "IC19") (pin "31") (pinfunction "IO171_31") (pintype "bidirectional"))
    )
    (net (code "261") (name "unconnected-(IC19AS-IO174-Pad29)") (class "Default")
      (node (ref "IC19") (pin "29") (pinfunction "IO174_29") (pintype "bidirectional"))
    )
    (net (code "262") (name "unconnected-(IC19AS-IO177-Pad66)") (class "Default")
      (node (ref "IC19") (pin "66") (pinfunction "IO177_66") (pintype "bidirectional"))
    )
    (net (code "263") (name "unconnected-(IC19AS-IO179-Pad67)") (class "Default")
      (node (ref "IC19") (pin "67") (pinfunction "IO179_67") (pintype "bidirectional"))
    )
    (net (code "264") (name "unconnected-(IC19AS-IO181-Pad68)") (class "Default")
      (node (ref "IC19") (pin "68") (pinfunction "IO181_68") (pintype "bidirectional"))
    )
    (net (code "265") (name "unconnected-(IC19AS-IO182-Pad69)") (class "Default")
      (node (ref "IC19") (pin "69") (pinfunction "IO182_69") (pintype "bidirectional"))
    )
    (net (code "266") (name "unconnected-(IC19AS-IO184-Pad70)") (class "Default")
      (node (ref "IC19") (pin "70") (pinfunction "IO184_70") (pintype "bidirectional"))
    )
    (net (code "267") (name "unconnected-(IC19AS-IO187-Pad73)") (class "Default")
      (node (ref "IC19") (pin "73") (pinfunction "IO187_73") (pintype "bidirectional"))
    )
    (net (code "268") (name "unconnected-(IC19AS-IO193-Pad4)") (class "Default")
      (node (ref "IC19") (pin "4") (pinfunction "IO193_4") (pintype "bidirectional"))
    )
    (net (code "269") (name "unconnected-(IC19AS-IO197-Pad206)") (class "Default")
      (node (ref "IC19") (pin "206") (pinfunction "IO197_206") (pintype "bidirectional"))
    )
    (net (code "270") (name "unconnected-(IC19AS-IO240-Pad39)") (class "Default")
      (node (ref "IC19") (pin "39") (pinfunction "IO240_39") (pintype "bidirectional"))
    )
    (net (code "271") (name "unconnected-(IC19AS-IO241-Pad65)") (class "Default")
      (node (ref "IC19") (pin "65") (pinfunction "IO241_65") (pintype "bidirectional"))
    )
    (net (code "272") (name "unconnected-(IC19AS-IO243-Pad64)") (class "Default")
      (node (ref "IC19") (pin "64") (pinfunction "IO243_64") (pintype "bidirectional"))
    )
    (net (code "273") (name "unconnected-(IC19AS-IO245-Pad62)") (class "Default")
      (node (ref "IC19") (pin "62") (pinfunction "IO245_62") (pintype "bidirectional"))
    )
    (net (code "274") (name "unconnected-(IC19AS-IO246-Pad61)") (class "Default")
      (node (ref "IC19") (pin "61") (pinfunction "IO246_61") (pintype "bidirectional"))
    )
    (net (code "275") (name "unconnected-(IC19AS-IO248-Pad60)") (class "Default")
      (node (ref "IC19") (pin "60") (pinfunction "IO248_60") (pintype "bidirectional"))
    )
    (net (code "276") (name "unconnected-(IC19AS-IO249-Pad59)") (class "Default")
      (node (ref "IC19") (pin "59") (pinfunction "IO249_59") (pintype "bidirectional"))
    )
    (net (code "277") (name "unconnected-(IC19AS-IO251-Pad58)") (class "Default")
      (node (ref "IC19") (pin "58") (pinfunction "IO251_58") (pintype "bidirectional"))
    )
    (net (code "278") (name "unconnected-(IC19AS-IO253-Pad57)") (class "Default")
      (node (ref "IC19") (pin "57") (pinfunction "IO253_57") (pintype "bidirectional"))
    )
    (net (code "279") (name "unconnected-(IC19AS-IO254-Pad56)") (class "Default")
      (node (ref "IC19") (pin "56") (pinfunction "IO254_56") (pintype "bidirectional"))
    )
    (net (code "280") (name "unconnected-(IC19AS-OE1-Pad183)") (class "Default")
      (node (ref "IC19") (pin "183") (pinfunction "OE1_183") (pintype "input"))
    )
    (net (code "281") (name "unconnected-(IC19AS-OE2-GCLK2-Pad181)") (class "Default")
      (node (ref "IC19") (pin "181") (pinfunction "OE2-GCLK2_181") (pintype "input"))
    )
    (net (code "282") (name "unconnected-(IC39A-R1IN-Pad13)") (class "Default")
      (node (ref "IC39") (pin "13") (pinfunction "R1IN_13") (pintype "input"))
    )
    (net (code "283") (name "unconnected-(IC39A-R1OUT-Pad12)") (class "Default")
      (node (ref "IC39") (pin "12") (pinfunction "R1OUT_12") (pintype "output"))
    )
    (net (code "284") (name "unconnected-(IC39A-T1IN-Pad11)") (class "Default")
      (node (ref "IC39") (pin "11") (pinfunction "T1IN_11") (pintype "input"))
    )
    (net (code "285") (name "unconnected-(IC39A-T1OUT-Pad14)") (class "Default")
      (node (ref "IC39") (pin "14") (pinfunction "T1OUT_14") (pintype "output"))
    )
    (net (code "286") (name "unconnected-(JP3-Pad6)") (class "Default")
      (node (ref "JP3") (pin "6") (pinfunction "6_6") (pintype "passive"))
    )
    (net (code "287") (name "unconnected-(JP3-Pad7)") (class "Default")
      (node (ref "JP3") (pin "7") (pinfunction "7_7") (pintype "passive"))
    )
    (net (code "288") (name "unconnected-(JP3-Pad8)") (class "Default")
      (node (ref "JP3") (pin "8") (pinfunction "8_8") (pintype "passive"))
    )
    (net (code "289") (name "unconnected-(RN1-Pad7)") (class "Default")
      (node (ref "RN1") (pin "7") (pinfunction "7_7") (pintype "passive"))
    )
    (net (code "290") (name "unconnected-(RN1-Pad8)") (class "Default")
      (node (ref "RN1") (pin "8") (pinfunction "8_8") (pintype "passive"))
    )
    (net (code "291") (name "unconnected-(RN1-Pad9)") (class "Default")
      (node (ref "RN1") (pin "9") (pinfunction "9_9") (pintype "passive"))
    )
    (net (code "292") (name "unconnected-(RN10C-1-Pad4)") (class "Default")
      (node (ref "RN10") (pin "4") (pinfunction "1_4") (pintype "passive"))
    )
    (net (code "293") (name "unconnected-(RN10D-1-Pad5)") (class "Default")
      (node (ref "RN10") (pin "5") (pinfunction "1_5") (pintype "passive"))
    )
    (net (code "294") (name "unconnected-(RN11D-1-Pad5)") (class "Default")
      (node (ref "RN11") (pin "5") (pinfunction "1_5") (pintype "passive"))
    )
    (net (code "295") (name "unconnected-(RN15A-1-Pad2)") (class "Default")
      (node (ref "RN15") (pin "2") (pinfunction "1_2") (pintype "passive"))
    )
    (net (code "296") (name "unconnected-(RN16D-1-Pad5)") (class "Default")
      (node (ref "RN16") (pin "5") (pinfunction "1_5") (pintype "passive"))
    )
    (net (code "297") (name "unconnected-(RN20-Pad9)") (class "Default")
      (node (ref "RN20") (pin "9") (pinfunction "9_9") (pintype "passive"))
    )
    (net (code "298") (name "unconnected-(RN20-Pad10)") (class "Default")
      (node (ref "RN20") (pin "10") (pinfunction "10_10") (pintype "passive"))
    )
    (net (code "299") (name "unconnected-(RN25C-1-Pad4)") (class "Default")
      (node (ref "RN25") (pin "4") (pinfunction "1_4") (pintype "passive"))
    )
    (net (code "300") (name "unconnected-(RN25D-1-Pad5)") (class "Default")
      (node (ref "RN25") (pin "5") (pinfunction "1_5") (pintype "passive"))
    )
    (net (code "301") (name "unconnected-(RN27D-1-Pad5)") (class "Default")
      (node (ref "RN27") (pin "5") (pinfunction "1_5") (pintype "passive"))
    )
    (net (code "302") (name "unconnected-(RN31A-1-Pad2)") (class "Default")
      (node (ref "RN31") (pin "2") (pinfunction "1_2") (pintype "passive"))
    )
    (net (code "303") (name "unconnected-(RN32D-1-Pad5)") (class "Default")
      (node (ref "RN32") (pin "5") (pinfunction "1_5") (pintype "passive"))
    )
    (net (code "304") (name "unconnected-(X2-Pad1)") (class "Default")
      (node (ref "X2") (pin "1") (pinfunction "1_1") (pintype "passive"))
    )
    (net (code "305") (name "unconnected-(X2-Pad4)") (class "Default")
      (node (ref "X2") (pin "4") (pinfunction "4_4") (pintype "passive"))
    )
    (net (code "306") (name "unconnected-(X2-Pad6)") (class "Default")
      (node (ref "X2") (pin "6") (pinfunction "6_6") (pintype "passive"))
    )
    (net (code "307") (name "unconnected-(X2-Pad7)") (class "Default")
      (node (ref "X2") (pin "7") (pinfunction "7_7") (pintype "passive"))
    )
    (net (code "308") (name "unconnected-(X2-Pad8)") (class "Default")
      (node (ref "X2") (pin "8") (pinfunction "8_8") (pintype "passive"))
    )
    (net (code "309") (name "unconnected-(X2-Pad9)") (class "Default")
      (node (ref "X2") (pin "9") (pinfunction "9_9") (pintype "passive"))
    )
    (net (code "310") (name "unconnected-(X2-PadG1)") (class "Default")
      (node (ref "X2") (pin "G1") (pinfunction "G1_G1") (pintype "passive"))
    )
    (net (code "311") (name "unconnected-(XP1A--12-PadAB2)") (class "Default")
      (node (ref "XP1") (pin "AB2") (pinfunction "-12_AB2") (pintype "bidirectional"))
    )
    (net (code "312") (name "unconnected-(XP1A-12V-PadAB4)") (class "Default")
      (node (ref "XP1") (pin "AB4") (pinfunction "12V_AB4") (pintype "bidirectional"))
    )
    (net (code "313") (name "unconnected-(XP1A-P$5-PadAA5)") (class "Default")
      (node (ref "XP1") (pin "AA5") (pinfunction "P$5_AA5") (pintype "bidirectional"))
    )
    (net (code "314") (name "unconnected-(XP1A-P$6-PadAA6)") (class "Default")
      (node (ref "XP1") (pin "AA6") (pinfunction "P$6_AA6") (pintype "bidirectional"))
    )
    (net (code "315") (name "unconnected-(XP1A-P$9-PadAA9)") (class "Default")
      (node (ref "XP1") (pin "AA9") (pinfunction "P$9_AA9") (pintype "bidirectional"))
    )
    (net (code "316") (name "unconnected-(XP1A-P$10-PadAA10)") (class "Default")
      (node (ref "XP1") (pin "AA10") (pinfunction "P$10_AA10") (pintype "bidirectional"))
    )
    (net (code "317") (name "unconnected-(XP1A-P$15-PadAA15)") (class "Default")
      (node (ref "XP1") (pin "AA15") (pinfunction "P$15_AA15") (pintype "bidirectional"))
    )
    (net (code "318") (name "unconnected-(XP1A-P$17-PadAA17)") (class "Default")
      (node (ref "XP1") (pin "AA17") (pinfunction "P$17_AA17") (pintype "bidirectional"))
    )
    (net (code "319") (name "unconnected-(XP1A-{slash}BDMGI-PadAB14)") (class "Default")
      (node (ref "XP1") (pin "AB14") (pinfunction "/BDMGI_AB14") (pintype "bidirectional"))
    )
    (net (code "320") (name "unconnected-(XP1A-{slash}BIAKI-PadAB11)") (class "Default")
      (node (ref "XP1") (pin "AB11") (pinfunction "/BIAKI_AB11") (pintype "bidirectional"))
    )
    (net (code "321") (name "unconnected-(XP1A-{slash}BREF-PadAA14)") (class "Default")
      (node (ref "XP1") (pin "AA14") (pinfunction "/BREF_AA14") (pintype "bidirectional"))
    )
    (net (code "322") (name "unconnected-(XP1B--12-PadBB2)") (class "Default")
      (node (ref "XP1") (pin "BB2") (pinfunction "-12_BB2") (pintype "bidirectional"))
    )
    (net (code "323") (name "unconnected-(XP1B-12V-PadBB4)") (class "Default")
      (node (ref "XP1") (pin "BB4") (pinfunction "12V_BB4") (pintype "bidirectional"))
    )
    (net (code "324") (name "unconnected-(XP1B-P$9-PadBA9)") (class "Default")
      (node (ref "XP1") (pin "BA9") (pinfunction "P$9_BA9") (pintype "bidirectional"))
    )
    (net (code "325") (name "unconnected-(XP1B-P$10-PadBA10)") (class "Default")
      (node (ref "XP1") (pin "BA10") (pinfunction "P$10_BA10") (pintype "bidirectional"))
    )
    (net (code "326") (name "unconnected-(XP1B-P$15-PadBA15)") (class "Default")
      (node (ref "XP1") (pin "BA15") (pinfunction "P$15_BA15") (pintype "bidirectional"))
    )
    (net (code "327") (name "unconnected-(XP1B-P$17-PadBA17)") (class "Default")
      (node (ref "XP1") (pin "BA17") (pinfunction "P$17_BA17") (pintype "bidirectional"))
    )
    (net (code "328") (name "{slash}DREADY") (class "Default")
      (node (ref "IC1") (pin "56") (pinfunction "/DREADY_56") (pintype "bidirectional"))
      (node (ref "IC16") (pin "17") (pinfunction "/DREADY_17") (pintype "bidirectional"))
      (node (ref "RN2") (pin "8") (pinfunction "8_8") (pintype "passive"))
    )
    (net (code "329") (name "{slash}FD") (class "Default")
      (node (ref "IC1") (pin "58") (pinfunction "/FD_58") (pintype "bidirectional"))
      (node (ref "IC16") (pin "10") (pinfunction "/FD_10") (pintype "bidirectional"))
      (node (ref "RN2") (pin "6") (pinfunction "6_6") (pintype "passive"))
    )
    (net (code "330") (name "{slash}FL") (class "Default")
      (node (ref "IC1") (pin "57") (pinfunction "/FL_57") (pintype "bidirectional"))
      (node (ref "IC16") (pin "11") (pinfunction "/FL_11") (pintype "bidirectional"))
      (node (ref "RN2") (pin "7") (pinfunction "7_7") (pintype "passive"))
    )
    (net (code "331") (name "{slash}FPPRD") (class "Default")
      (node (ref "IC1") (pin "54") (pinfunction "/FPPRD_54") (pintype "bidirectional"))
      (node (ref "IC16") (pin "15") (pinfunction "/FPPRD_15") (pintype "bidirectional"))
      (node (ref "RN2") (pin "10") (pinfunction "10_10") (pintype "passive"))
    )
    (net (code "332") (name "{slash}FPPTR") (class "Default")
      (node (ref "IC1") (pin "53") (pinfunction "/FPPTRP_53") (pintype "bidirectional"))
      (node (ref "IC16") (pin "14") (pinfunction "FPPTRP_14") (pintype "bidirectional"))
      (node (ref "RN3") (pin "2") (pinfunction "2_2") (pintype "passive"))
    )
    (net (code "333") (name "{slash}LIN") (class "Default")
      (node (ref "IC1") (pin "61") (pinfunction "/LIN_61") (pintype "bidirectional"))
      (node (ref "IC16") (pin "12") (pinfunction "/LIN_12") (pintype "bidirectional"))
      (node (ref "RN2") (pin "4") (pinfunction "4_4") (pintype "passive"))
    )
    (net (code "334") (name "{slash}RX") (class "Default")
      (node (ref "IC19") (pin "109") (pinfunction "IO35_109") (pintype "bidirectional"))
      (node (ref "IC2") (pin "28") (pinfunction "IP_28") (pintype "bidirectional"))
    )
    (net (code "335") (name "{slash}TX") (class "Default")
      (node (ref "IC19") (pin "111") (pinfunction "IO38_111") (pintype "bidirectional"))
      (node (ref "IC2") (pin "27") (pinfunction "TF_27") (pintype "bidirectional"))
    )
  )
)
